# expansion_board_V0.net
KiCad netlist of a schematic drawn in EAGLE
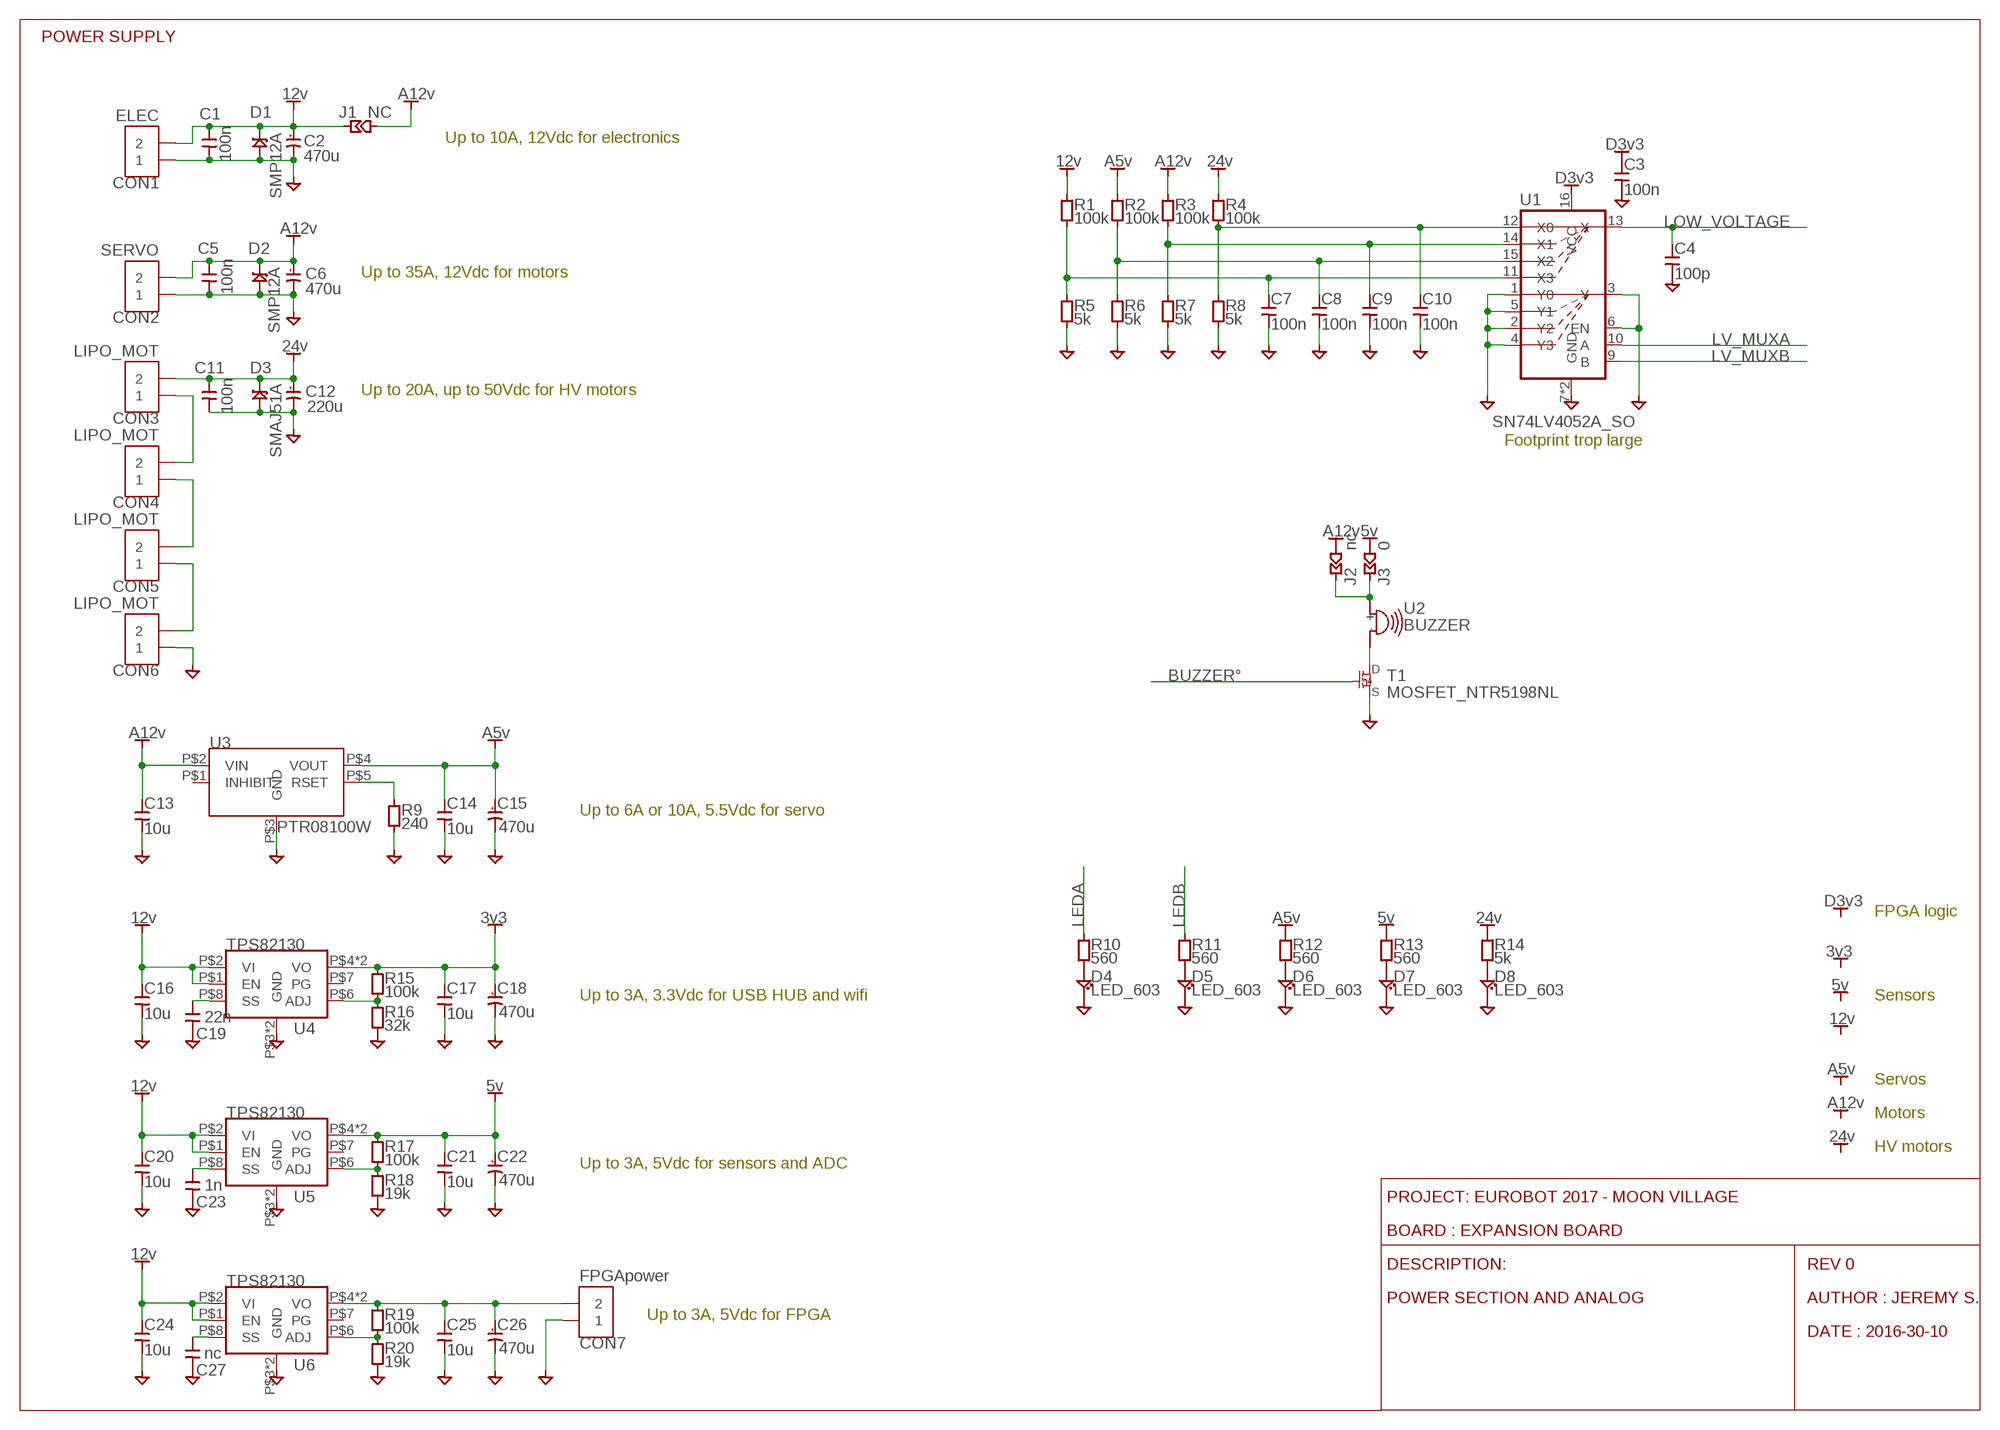
[diagram p0: schematic, sheet 1]
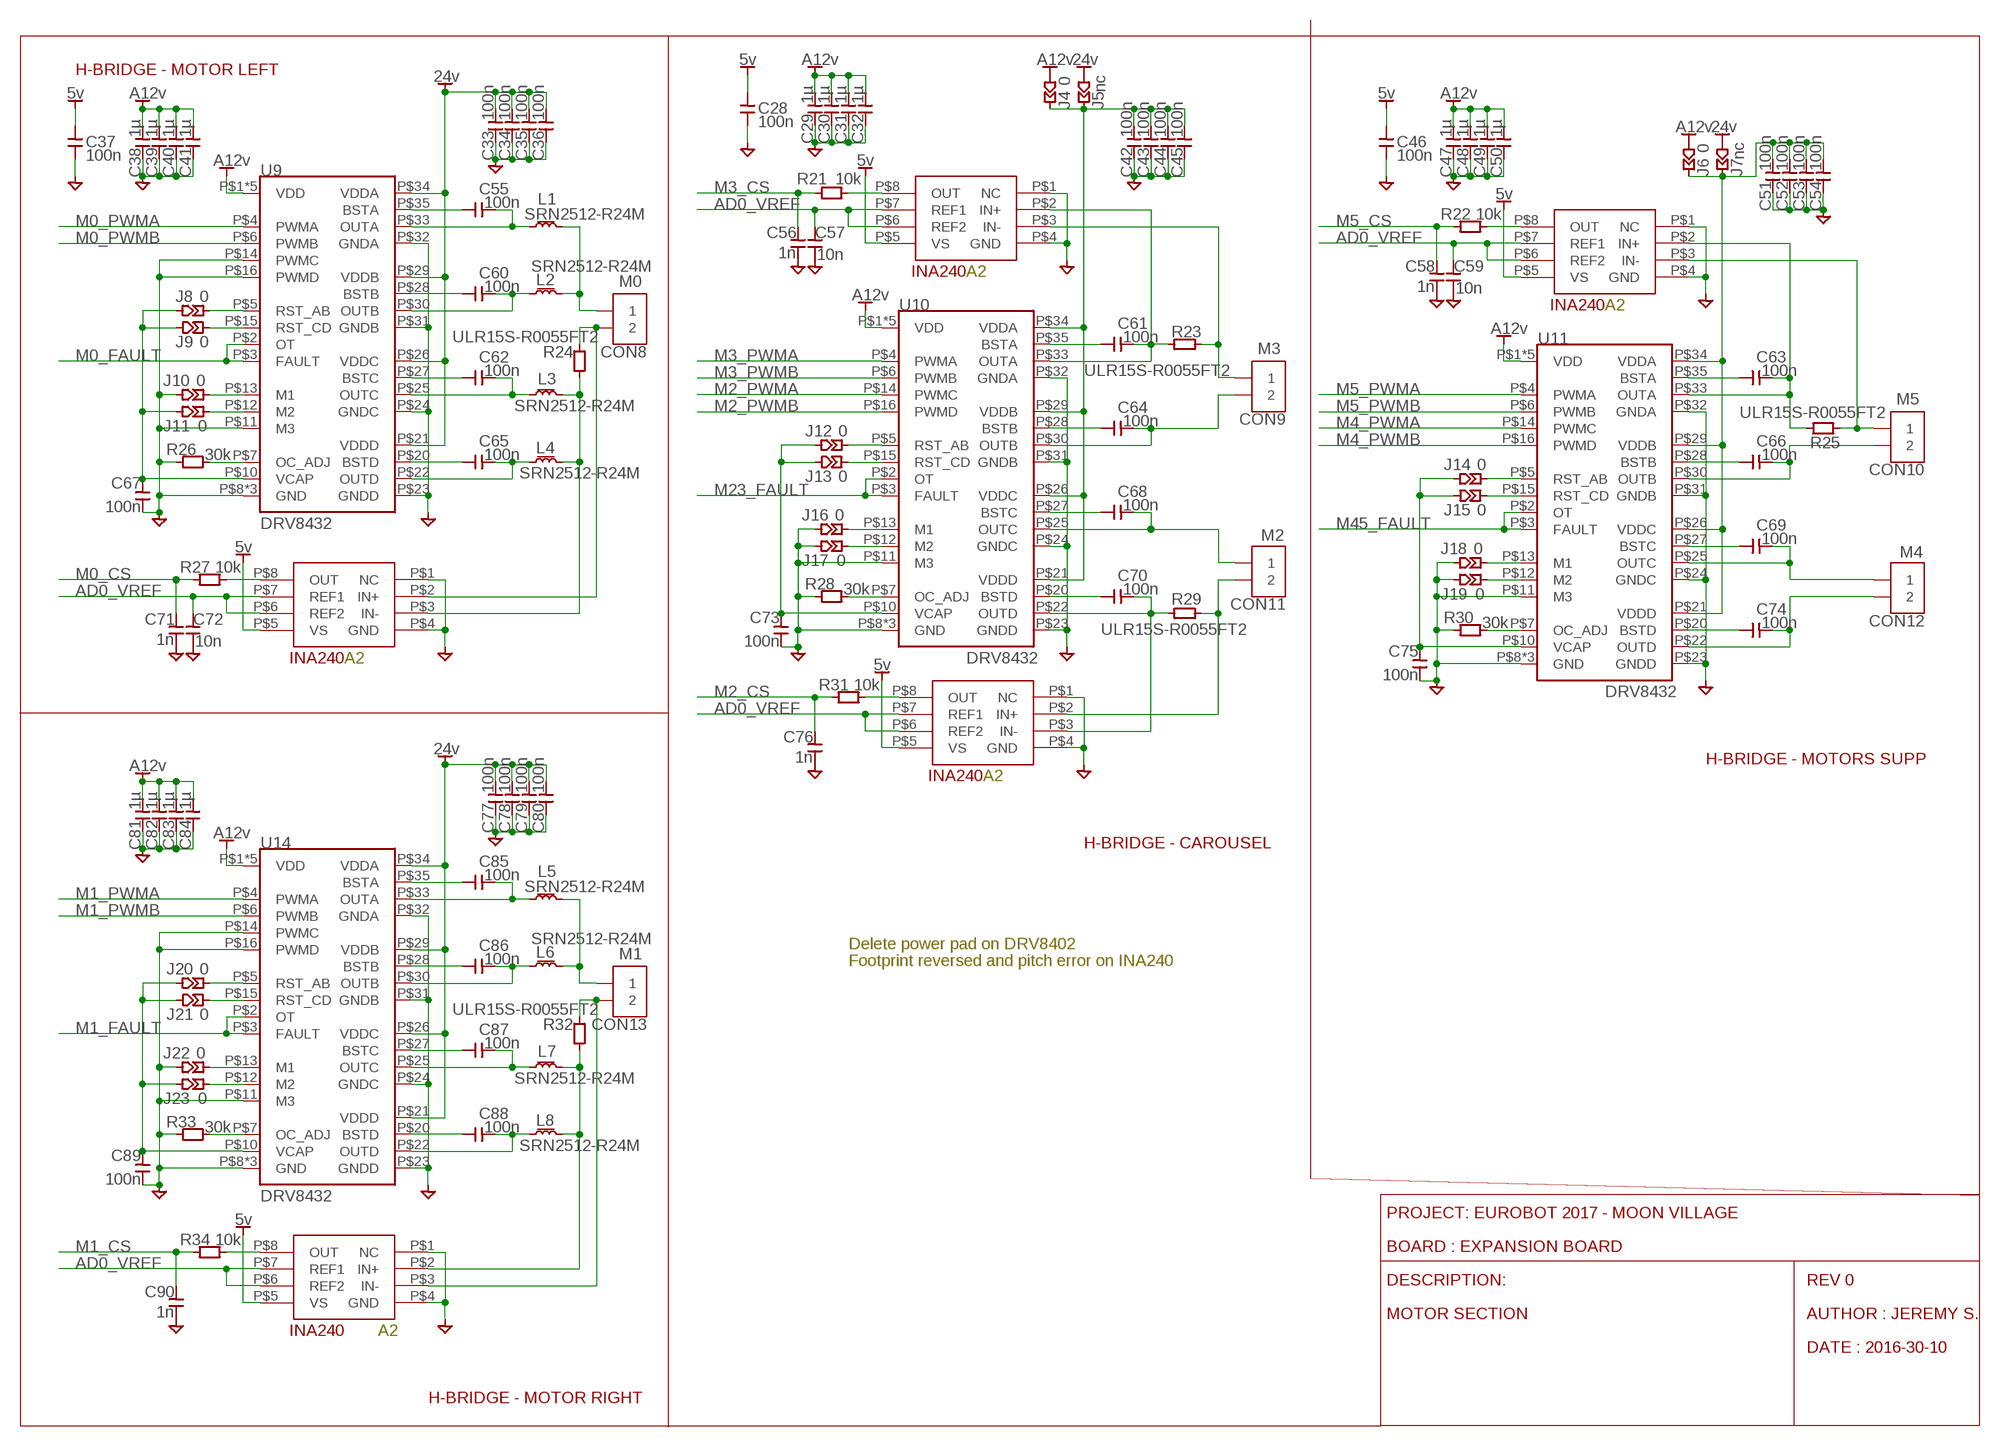
[diagram p1: schematic, sheet 2]
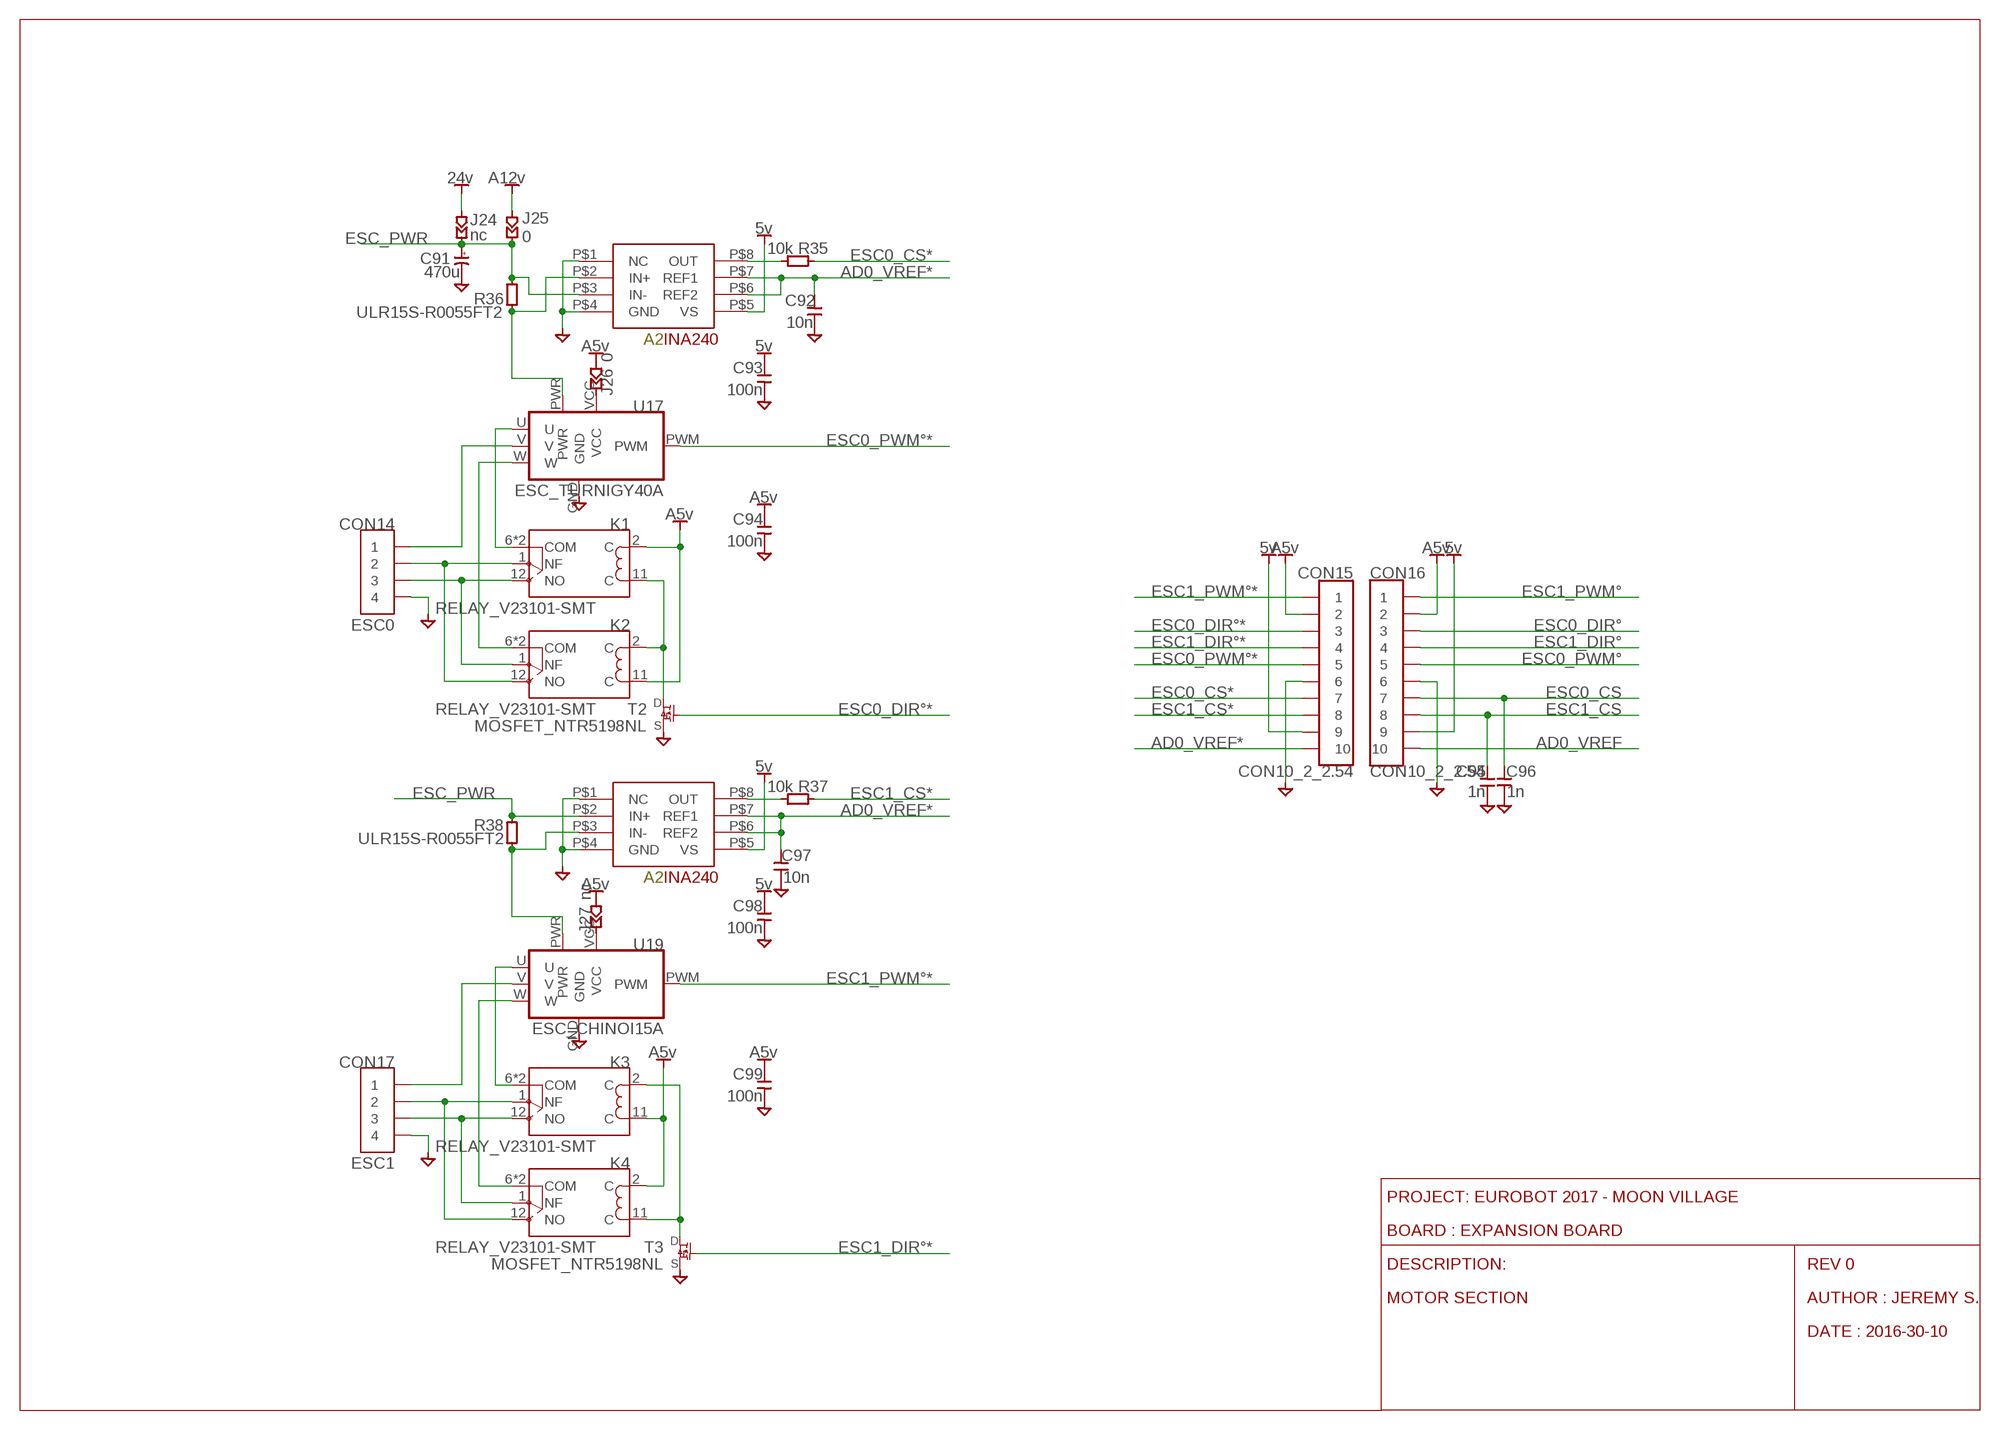
[diagram p2: schematic, sheet 3]
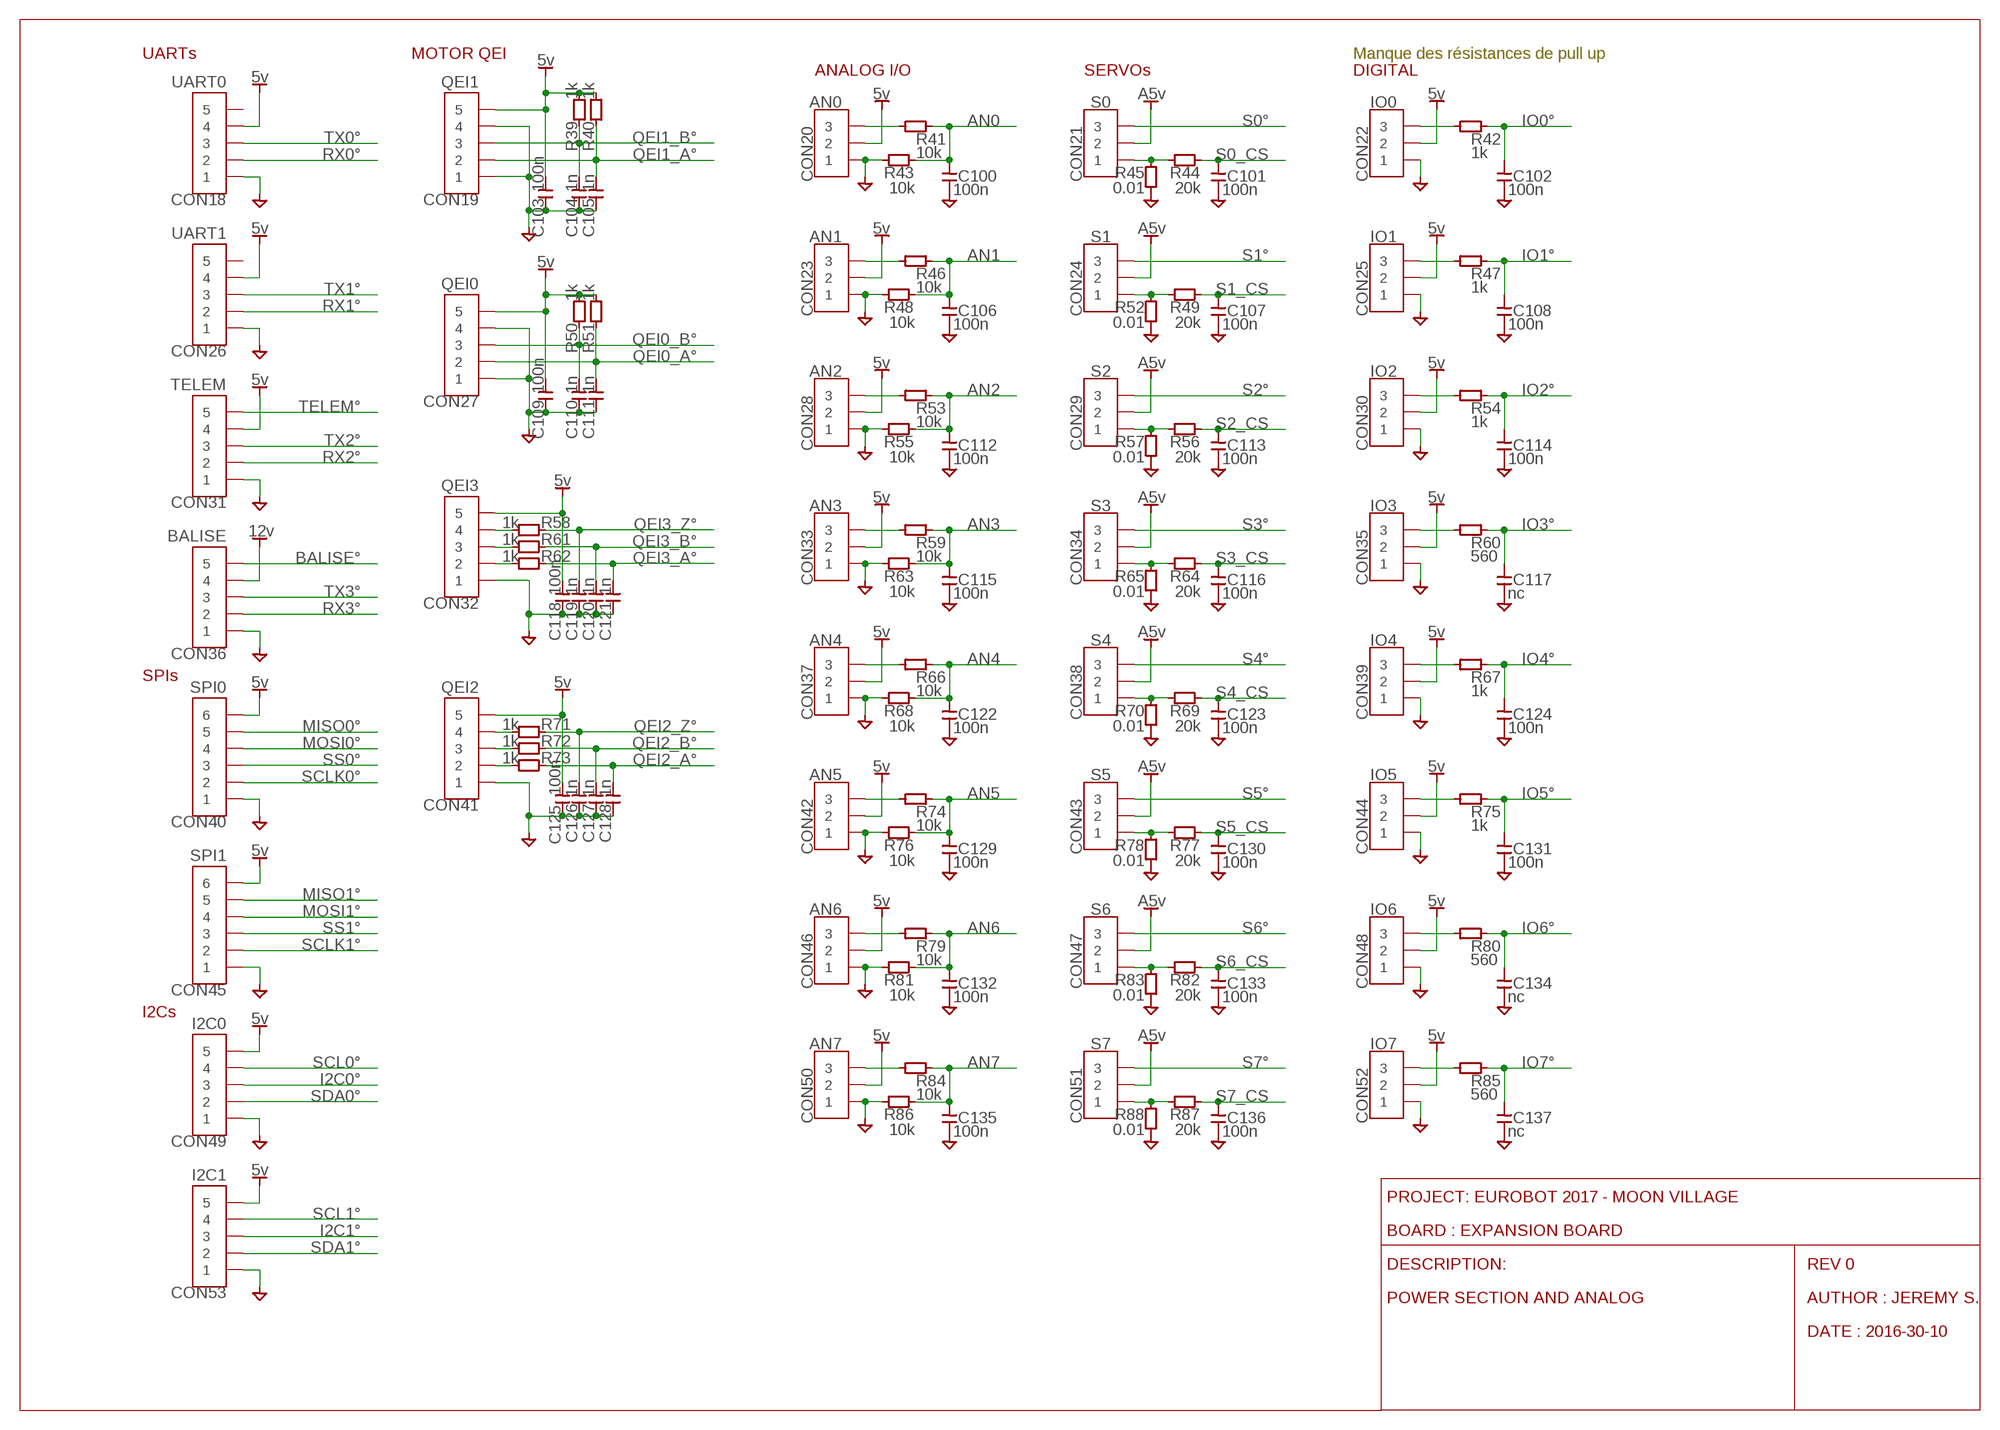
[diagram p3: schematic, sheet 4]
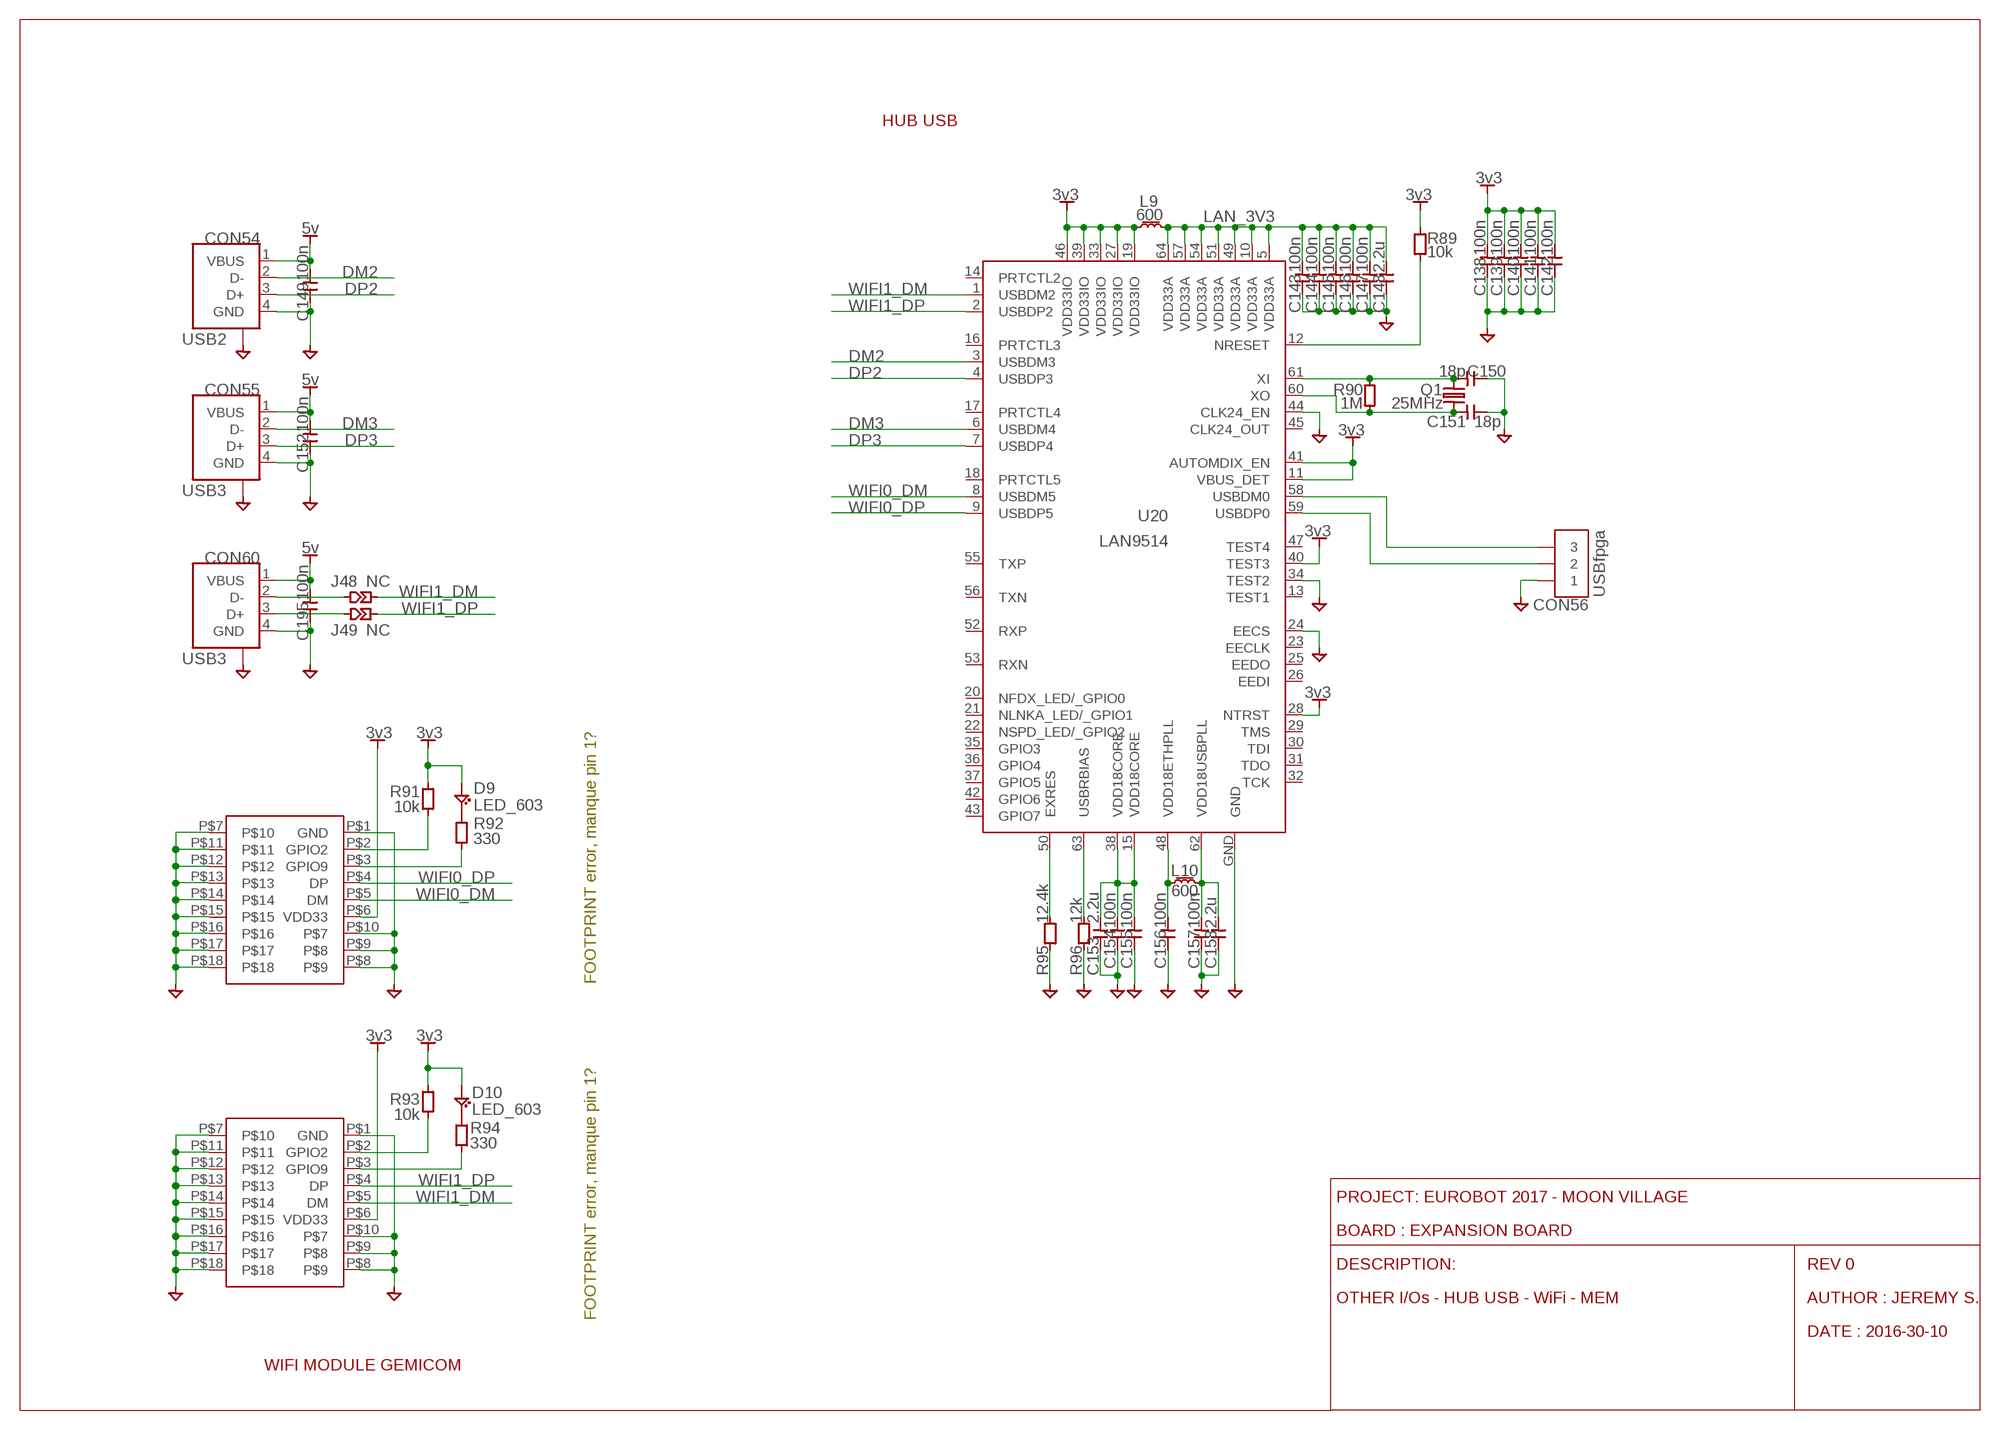
[diagram p4: schematic, sheet 5]
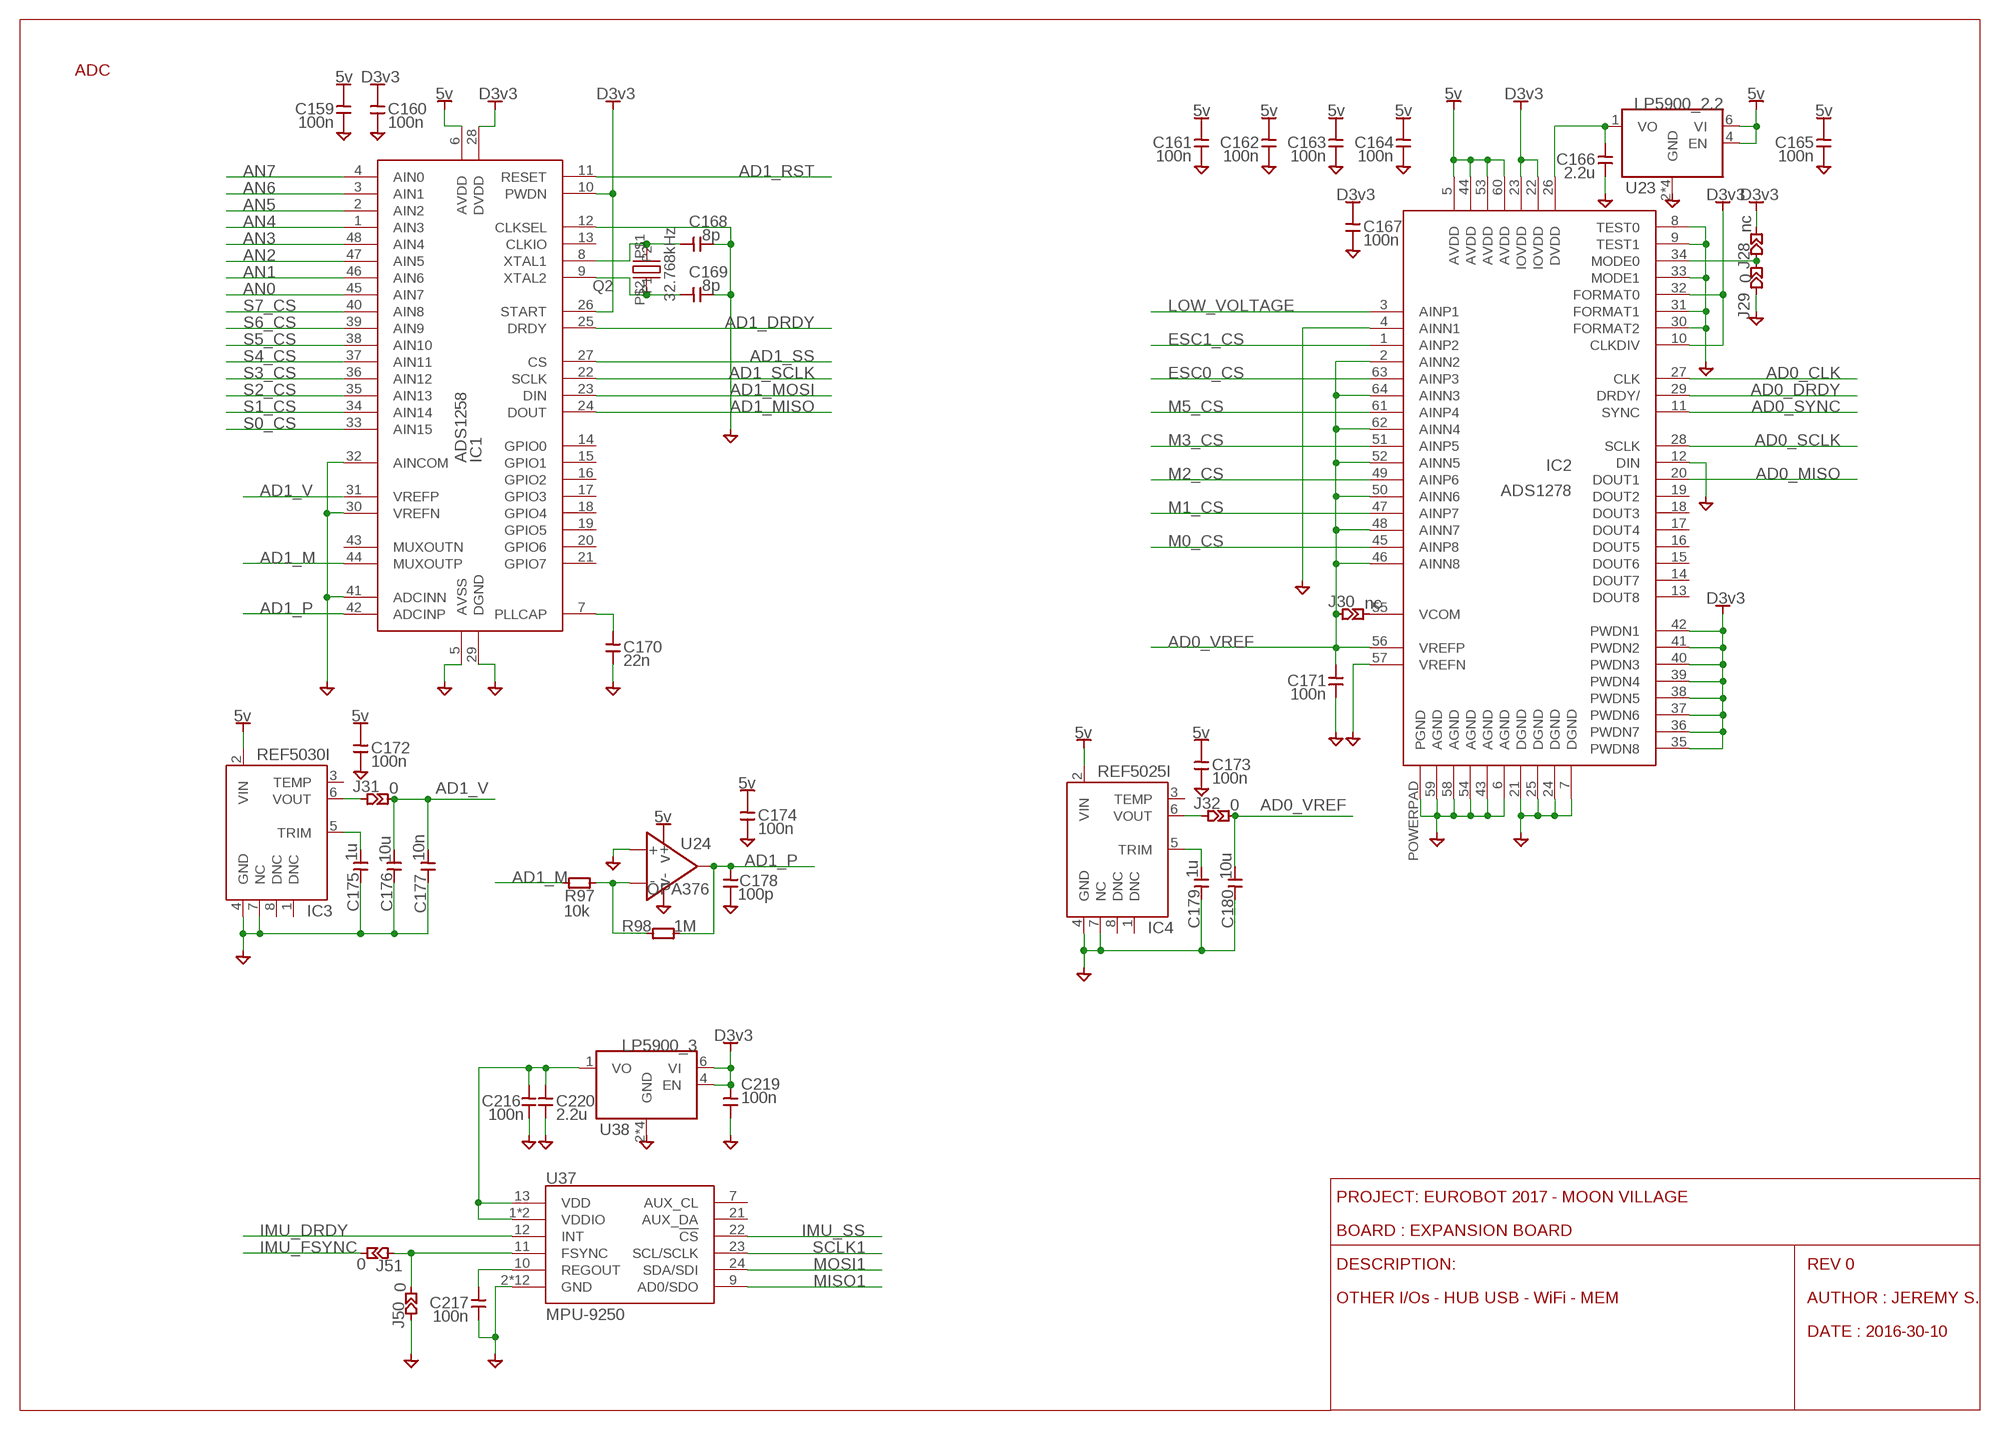
[diagram p5: schematic, sheet 6]
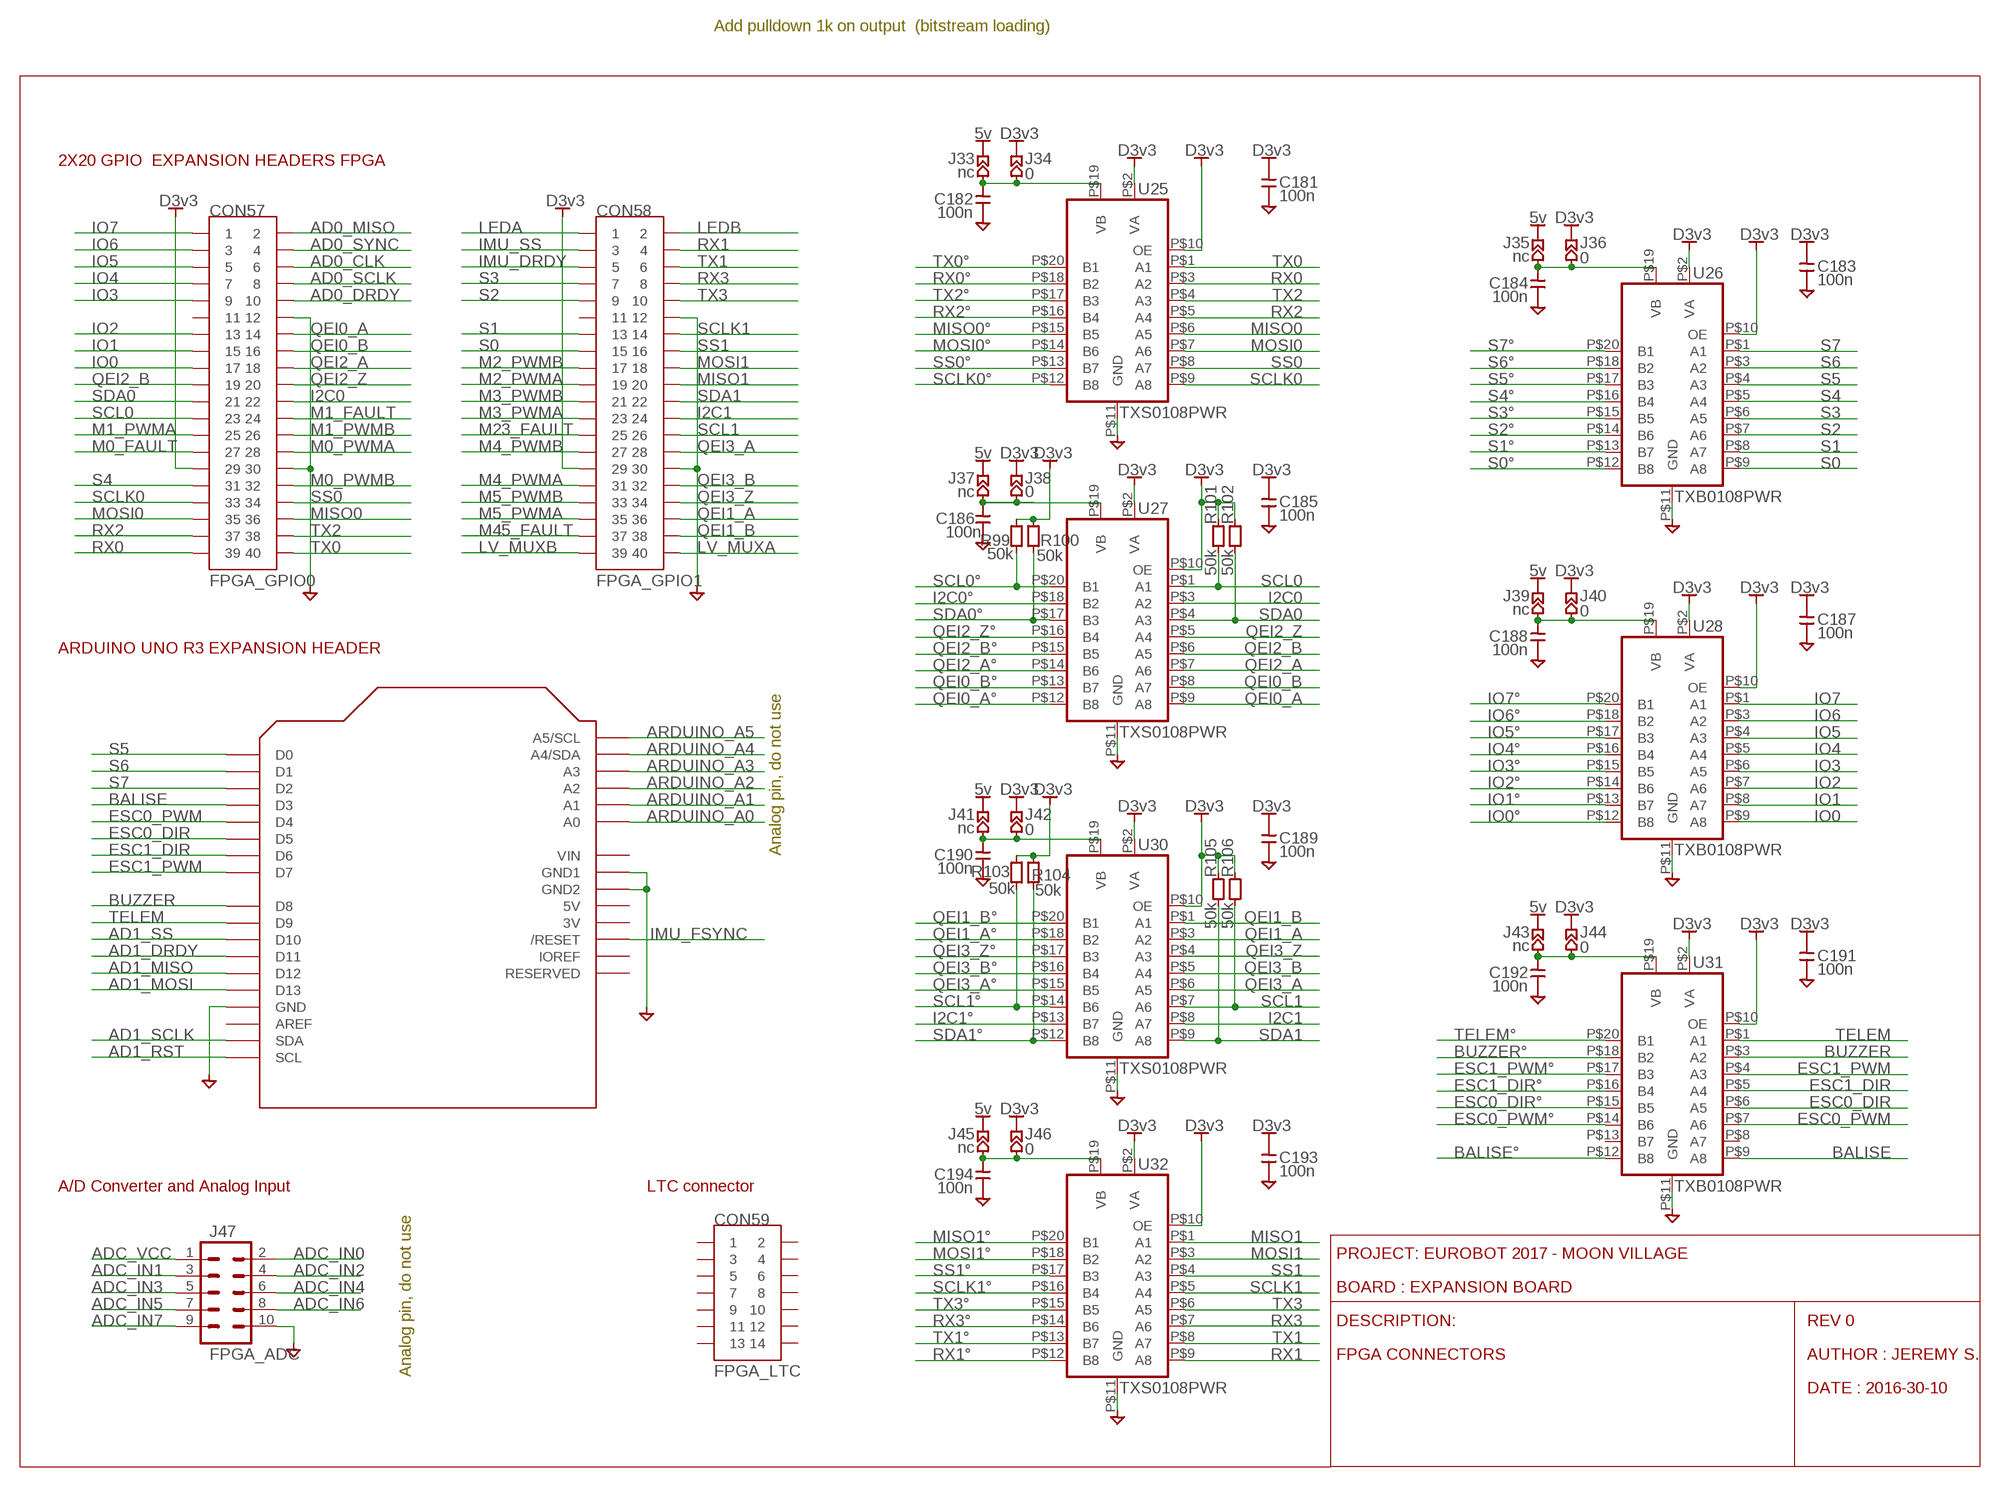
[diagram p6: schematic, sheet 7]
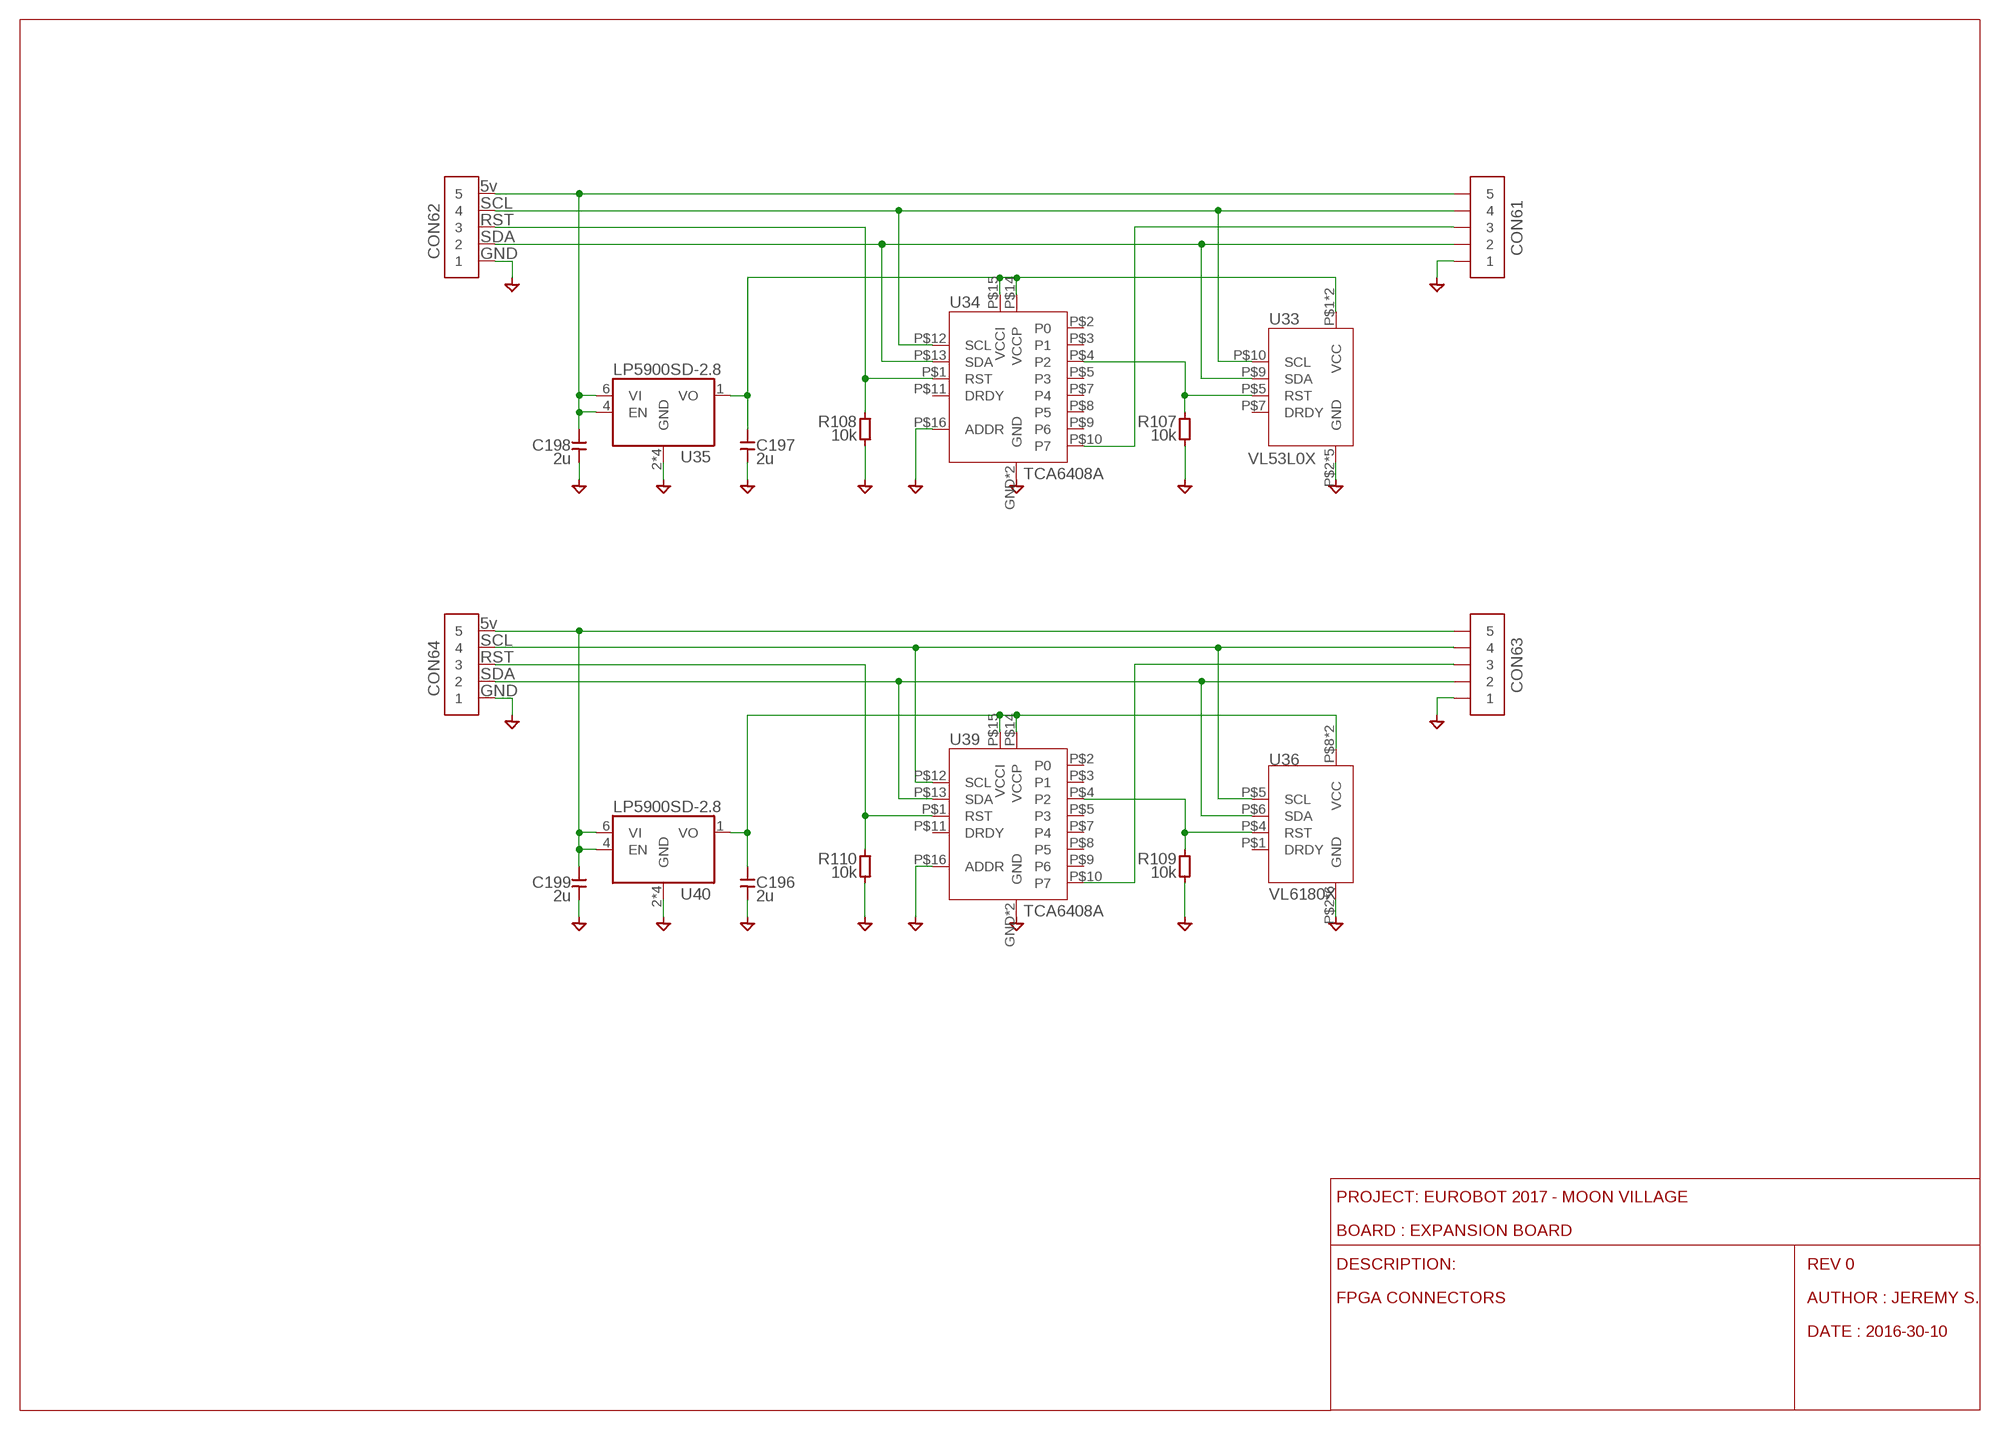
[diagram p7: schematic, sheet 8]

(export (version "E")
  (design (tool "Eeschema 10.0.6"))
  (components
    (comp (ref "C181")
      (value "100n")
      (footprint "eagle-import:CAPC1005X55N")
      (libsource (lib "eagle-import") (part "C_402"))
    )
    (comp (ref "C182")
      (value "100n")
      (footprint "eagle-import:CAPC1005X55N")
      (libsource (lib "eagle-import") (part "C_402"))
    )
    (comp (ref "C183")
      (value "100n")
      (footprint "eagle-import:CAPC1005X55N")
      (libsource (lib "eagle-import") (part "C_402"))
    )
    (comp (ref "C184")
      (value "100n")
      (footprint "eagle-import:CAPC1005X55N")
      (libsource (lib "eagle-import") (part "C_402"))
    )
    (comp (ref "C185")
      (value "100n")
      (footprint "eagle-import:CAPC1005X55N")
      (libsource (lib "eagle-import") (part "C_402"))
    )
    (comp (ref "C186")
      (value "100n")
      (footprint "eagle-import:CAPC1005X55N")
      (libsource (lib "eagle-import") (part "C_402"))
    )
    (comp (ref "C187")
      (value "100n")
      (footprint "eagle-import:CAPC1005X55N")
      (libsource (lib "eagle-import") (part "C_402"))
    )
    (comp (ref "C188")
      (value "100n")
      (footprint "eagle-import:CAPC1005X55N")
      (libsource (lib "eagle-import") (part "C_402"))
    )
    (comp (ref "C189")
      (value "100n")
      (footprint "eagle-import:CAPC1005X55N")
      (libsource (lib "eagle-import") (part "C_402"))
    )
    (comp (ref "C190")
      (value "100n")
      (footprint "eagle-import:CAPC1005X55N")
      (libsource (lib "eagle-import") (part "C_402"))
    )
    (comp (ref "C191")
      (value "100n")
      (footprint "eagle-import:CAPC1005X55N")
      (libsource (lib "eagle-import") (part "C_402"))
    )
    (comp (ref "C192")
      (value "100n")
      (footprint "eagle-import:CAPC1005X55N")
      (libsource (lib "eagle-import") (part "C_402"))
    )
    (comp (ref "C193")
      (value "100n")
      (footprint "eagle-import:CAPC1005X55N")
      (libsource (lib "eagle-import") (part "C_402"))
    )
    (comp (ref "C194")
      (value "100n")
      (footprint "eagle-import:CAPC1005X55N")
      (libsource (lib "eagle-import") (part "C_402"))
    )
    (comp (ref "CON57")
      (value "FPGA_GPIO0")
      (footprint "eagle-import:CON254P5080X600-40N")
      (libsource (lib "eagle-import") (part "CON40_2.54"))
    )
    (comp (ref "CON58")
      (value "FPGA_GPIO1")
      (footprint "eagle-import:CON254P5080X600-40N")
      (libsource (lib "eagle-import") (part "CON40_2.54"))
    )
    (comp (ref "CON59")
      (value "FPGA_LTC")
      (footprint "eagle-import:CON200P1700X400-2X7N")
      (libsource (lib "eagle-import") (part "CON14"))
    )
    (comp (ref "J33")
      (value "nc")
      (footprint "eagle-import:JUMC1005X50N")
      (libsource (lib "eagle-import") (part "JUMP_402"))
    )
    (comp (ref "J34")
      (value "0")
      (footprint "eagle-import:JUMC1005X50N")
      (libsource (lib "eagle-import") (part "JUMP_402"))
    )
    (comp (ref "J35")
      (value "nc")
      (footprint "eagle-import:JUMC1005X50N")
      (libsource (lib "eagle-import") (part "JUMP_402"))
    )
    (comp (ref "J36")
      (value "0")
      (footprint "eagle-import:JUMC1005X50N")
      (libsource (lib "eagle-import") (part "JUMP_402"))
    )
    (comp (ref "J37")
      (value "nc")
      (footprint "eagle-import:JUMC1005X50N")
      (libsource (lib "eagle-import") (part "JUMP_402"))
    )
    (comp (ref "J38")
      (value "0")
      (footprint "eagle-import:JUMC1005X50N")
      (libsource (lib "eagle-import") (part "JUMP_402"))
    )
    (comp (ref "J39")
      (value "nc")
      (footprint "eagle-import:JUMC1005X50N")
      (libsource (lib "eagle-import") (part "JUMP_402"))
    )
    (comp (ref "J40")
      (value "0")
      (footprint "eagle-import:JUMC1005X50N")
      (libsource (lib "eagle-import") (part "JUMP_402"))
    )
    (comp (ref "J41")
      (value "nc")
      (footprint "eagle-import:JUMC1005X50N")
      (libsource (lib "eagle-import") (part "JUMP_402"))
    )
    (comp (ref "J42")
      (value "0")
      (footprint "eagle-import:JUMC1005X50N")
      (libsource (lib "eagle-import") (part "JUMP_402"))
    )
    (comp (ref "J43")
      (value "nc")
      (footprint "eagle-import:JUMC1005X50N")
      (libsource (lib "eagle-import") (part "JUMP_402"))
    )
    (comp (ref "J44")
      (value "0")
      (footprint "eagle-import:JUMC1005X50N")
      (libsource (lib "eagle-import") (part "JUMP_402"))
    )
    (comp (ref "J45")
      (value "nc")
      (footprint "eagle-import:JUMC1005X50N")
      (libsource (lib "eagle-import") (part "JUMP_402"))
    )
    (comp (ref "J46")
      (value "0")
      (footprint "eagle-import:JUMC1005X50N")
      (libsource (lib "eagle-import") (part "JUMP_402"))
    )
    (comp (ref "J47")
      (value "FPGA_ADC")
      (footprint "eagle-import:2X5_NOSILK")
      (libsource (lib "eagle-import") (part "M05X2NO_SILK"))
    )
    (comp (ref "R99")
      (value "50k")
      (footprint "eagle-import:RESC1005X40N")
      (libsource (lib "eagle-import") (part "R_402"))
    )
    (comp (ref "R100")
      (value "50k")
      (footprint "eagle-import:RESC1005X40N")
      (libsource (lib "eagle-import") (part "R_402"))
    )
    (comp (ref "R101")
      (value "50k")
      (footprint "eagle-import:RESC1005X40N")
      (libsource (lib "eagle-import") (part "R_402"))
    )
    (comp (ref "R102")
      (value "50k")
      (footprint "eagle-import:RESC1005X40N")
      (libsource (lib "eagle-import") (part "R_402"))
    )
    (comp (ref "R103")
      (value "50k")
      (footprint "eagle-import:RESC1005X40N")
      (libsource (lib "eagle-import") (part "R_402"))
    )
    (comp (ref "R104")
      (value "50k")
      (footprint "eagle-import:RESC1005X40N")
      (libsource (lib "eagle-import") (part "R_402"))
    )
    (comp (ref "R105")
      (value "50k")
      (footprint "eagle-import:RESC1005X40N")
      (libsource (lib "eagle-import") (part "R_402"))
    )
    (comp (ref "R106")
      (value "50k")
      (footprint "eagle-import:RESC1005X40N")
      (libsource (lib "eagle-import") (part "R_402"))
    )
    (comp (ref "U25")
      (value "TXS0108PWR")
      (footprint "eagle-import:SOP65P640X110-20N")
      (libsource (lib "eagle-import") (part "TX_0108_TSSOP"))
    )
    (comp (ref "U26")
      (value "TXB0108PWR")
      (footprint "eagle-import:SOP65P640X110-20N")
      (libsource (lib "eagle-import") (part "TX_0108_TSSOP"))
    )
    (comp (ref "U27")
      (value "TXS0108PWR")
      (footprint "eagle-import:SOP65P640X110-20N")
      (libsource (lib "eagle-import") (part "TX_0108_TSSOP"))
    )
    (comp (ref "U28")
      (value "TXB0108PWR")
      (footprint "eagle-import:SOP65P640X110-20N")
      (libsource (lib "eagle-import") (part "TX_0108_TSSOP"))
    )
    (comp (ref "U29")
      (value "FPGA_ARDUINO")
      (footprint "eagle-import:ARDUINOR3")
      (libsource (lib "eagle-import") (part "ARDUINOR3-DIMENSION"))
    )
    (comp (ref "U30")
      (value "TXS0108PWR")
      (footprint "eagle-import:SOP65P640X110-20N")
      (libsource (lib "eagle-import") (part "TX_0108_TSSOP"))
    )
    (comp (ref "U31")
      (value "TXB0108PWR")
      (footprint "eagle-import:SOP65P640X110-20N")
      (libsource (lib "eagle-import") (part "TX_0108_TSSOP"))
    )
    (comp (ref "U32")
      (value "TXS0108PWR")
      (footprint "eagle-import:SOP65P640X110-20N")
      (libsource (lib "eagle-import") (part "TX_0108_TSSOP"))
    )
    (comp (ref "C196")
      (value "2u")
      (footprint "eagle-import:CAPC1608X95N")
      (libsource (lib "eagle-import") (part "C_603"))
    )
    (comp (ref "C197")
      (value "2u")
      (footprint "eagle-import:CAPC1608X95N")
      (libsource (lib "eagle-import") (part "C_603"))
    )
    (comp (ref "C198")
      (value "2u")
      (footprint "eagle-import:CAPC1608X95N")
      (libsource (lib "eagle-import") (part "C_603"))
    )
    (comp (ref "C199")
      (value "2u")
      (footprint "eagle-import:CAPC1608X95N")
      (libsource (lib "eagle-import") (part "C_603"))
    )
    (comp (ref "CON61")
      (value "CON5_2.54S")
      (footprint "eagle-import:CON254P1270X400-5S")
      (libsource (lib "eagle-import") (part "CON5_2.54S"))
    )
    (comp (ref "CON62")
      (value "CON5_2.54S")
      (footprint "eagle-import:CON254P1270X400-5S")
      (libsource (lib "eagle-import") (part "CON5_2.54S"))
    )
    (comp (ref "CON63")
      (value "CON5_2.54S")
      (footprint "eagle-import:CON254P1270X400-5S")
      (libsource (lib "eagle-import") (part "CON5_2.54S"))
    )
    (comp (ref "CON64")
      (value "CON5_2.54S")
      (footprint "eagle-import:CON254P1270X400-5S")
      (libsource (lib "eagle-import") (part "CON5_2.54S"))
    )
    (comp (ref "R107")
      (value "10k")
      (footprint "eagle-import:RESC1005X40N")
      (libsource (lib "eagle-import") (part "R_402"))
    )
    (comp (ref "R108")
      (value "10k")
      (footprint "eagle-import:RESC1005X40N")
      (libsource (lib "eagle-import") (part "R_402"))
    )
    (comp (ref "R109")
      (value "10k")
      (footprint "eagle-import:RESC1005X40N")
      (libsource (lib "eagle-import") (part "R_402"))
    )
    (comp (ref "R110")
      (value "10k")
      (footprint "eagle-import:RESC1005X40N")
      (libsource (lib "eagle-import") (part "R_402"))
    )
    (comp (ref "U33")
      (value "VL53L0X")
      (footprint "eagle-import:VL53L0X")
      (libsource (lib "eagle-import") (part "VL53L0X"))
    )
    (comp (ref "U34")
      (value "TCA6408A")
      (footprint "eagle-import:QFN50P300X300X80-17N")
      (libsource (lib "eagle-import") (part "I2C_EXPTCA6408A"))
    )
    (comp (ref "U35")
      (value "LP5900SD-2.8")
      (footprint "eagle-import:SON65P250X220X80-7N")
      (libsource (lib "eagle-import") (part "REG_EN_LP5900"))
    )
    (comp (ref "U36")
      (value "VL6180X")
      (footprint "eagle-import:VL6180X")
      (libsource (lib "eagle-import") (part "VL6180X"))
    )
    (comp (ref "U39")
      (value "TCA6408A")
      (footprint "eagle-import:QFN50P300X300X80-17N")
      (libsource (lib "eagle-import") (part "I2C_EXPTCA6408A"))
    )
    (comp (ref "U40")
      (value "LP5900SD-2.8")
      (footprint "eagle-import:SON65P250X220X80-7N")
      (libsource (lib "eagle-import") (part "REG_EN_LP5900"))
    )
    (comp (ref "C138")
      (value "100n")
      (footprint "eagle-import:CAPC1005X55N")
      (libsource (lib "eagle-import") (part "C_402"))
    )
    (comp (ref "C139")
      (value "100n")
      (footprint "eagle-import:CAPC1005X55N")
      (libsource (lib "eagle-import") (part "C_402"))
    )
    (comp (ref "C140")
      (value "100n")
      (footprint "eagle-import:CAPC1005X55N")
      (libsource (lib "eagle-import") (part "C_402"))
    )
    (comp (ref "C141")
      (value "100n")
      (footprint "eagle-import:CAPC1005X55N")
      (libsource (lib "eagle-import") (part "C_402"))
    )
    (comp (ref "C142")
      (value "100n")
      (footprint "eagle-import:CAPC1005X55N")
      (libsource (lib "eagle-import") (part "C_402"))
    )
    (comp (ref "C143")
      (value "100n")
      (footprint "eagle-import:CAPC1005X55N")
      (libsource (lib "eagle-import") (part "C_402"))
    )
    (comp (ref "C144")
      (value "100n")
      (footprint "eagle-import:CAPC1005X55N")
      (libsource (lib "eagle-import") (part "C_402"))
    )
    (comp (ref "C145")
      (value "100n")
      (footprint "eagle-import:CAPC1005X55N")
      (libsource (lib "eagle-import") (part "C_402"))
    )
    (comp (ref "C146")
      (value "100n")
      (footprint "eagle-import:CAPC1005X55N")
      (libsource (lib "eagle-import") (part "C_402"))
    )
    (comp (ref "C147")
      (value "100n")
      (footprint "eagle-import:CAPC1005X55N")
      (libsource (lib "eagle-import") (part "C_402"))
    )
    (comp (ref "C148")
      (value "2.2u")
      (footprint "eagle-import:CAPC1608X95N")
      (libsource (lib "eagle-import") (part "C_603"))
    )
    (comp (ref "C149")
      (value "100n")
      (footprint "eagle-import:CAPC1005X55N")
      (libsource (lib "eagle-import") (part "C_402"))
    )
    (comp (ref "C150")
      (value "18p")
      (footprint "eagle-import:CAPC1005X55N")
      (libsource (lib "eagle-import") (part "C_402"))
    )
    (comp (ref "C151")
      (value "18p")
      (footprint "eagle-import:CAPC1005X55N")
      (libsource (lib "eagle-import") (part "C_402"))
    )
    (comp (ref "C152")
      (value "100n")
      (footprint "eagle-import:CAPC1005X55N")
      (libsource (lib "eagle-import") (part "C_402"))
    )
    (comp (ref "C153")
      (value "2.2u")
      (footprint "eagle-import:CAPC1608X95N")
      (libsource (lib "eagle-import") (part "C_603"))
    )
    (comp (ref "C154")
      (value "100n")
      (footprint "eagle-import:CAPC1005X55N")
      (libsource (lib "eagle-import") (part "C_402"))
    )
    (comp (ref "C155")
      (value "100n")
      (footprint "eagle-import:CAPC1005X55N")
      (libsource (lib "eagle-import") (part "C_402"))
    )
    (comp (ref "C156")
      (value "100n")
      (footprint "eagle-import:CAPC1005X55N")
      (libsource (lib "eagle-import") (part "C_402"))
    )
    (comp (ref "C157")
      (value "100n")
      (footprint "eagle-import:CAPC1005X55N")
      (libsource (lib "eagle-import") (part "C_402"))
    )
    (comp (ref "C158")
      (value "2.2u")
      (footprint "eagle-import:CAPC1608X95N")
      (libsource (lib "eagle-import") (part "C_603"))
    )
    (comp (ref "C195")
      (value "100n")
      (footprint "eagle-import:CAPC1005X55N")
      (libsource (lib "eagle-import") (part "C_402"))
    )
    (comp (ref "CON54")
      (value "USB2")
      (footprint "eagle-import:USB_A")
      (libsource (lib "eagle-import") (part "USB_A"))
    )
    (comp (ref "CON55")
      (value "USB3")
      (footprint "eagle-import:USB_A")
      (libsource (lib "eagle-import") (part "USB_A"))
    )
    (comp (ref "CON56")
      (value "USBfpga")
      (footprint "eagle-import:CON254P762X400-3N-S")
      (libsource (lib "eagle-import") (part "CON3_2.54S"))
    )
    (comp (ref "CON60")
      (value "USB3")
      (footprint "eagle-import:USB_A")
      (libsource (lib "eagle-import") (part "USB_A"))
    )
    (comp (ref "D9")
      (value "LED_603")
      (footprint "eagle-import:LEDC1608X60N")
      (libsource (lib "eagle-import") (part "LED_603"))
    )
    (comp (ref "D10")
      (value "LED_603")
      (footprint "eagle-import:LEDC1608X60N")
      (libsource (lib "eagle-import") (part "LED_603"))
    )
    (comp (ref "J48")
      (value "NC")
      (footprint "eagle-import:JUMC1005X50N")
      (libsource (lib "eagle-import") (part "JUMP_402"))
    )
    (comp (ref "J49")
      (value "NC")
      (footprint "eagle-import:JUMC1005X50N")
      (libsource (lib "eagle-import") (part "JUMP_402"))
    )
    (comp (ref "L9")
      (value "600")
      (footprint "eagle-import:INDC1608X95N")
      (libsource (lib "eagle-import") (part "INDUCTANCE_603"))
    )
    (comp (ref "L10")
      (value "600")
      (footprint "eagle-import:INDC1608X95N")
      (libsource (lib "eagle-import") (part "INDUCTANCE_603"))
    )
    (comp (ref "Q1")
      (value "25MHz")
      (footprint "eagle-import:XTAL500X320X130N")
      (libsource (lib "eagle-import") (part "QUARTZ2"))
    )
    (comp (ref "R89")
      (value "10k")
      (footprint "eagle-import:RESC1005X40N")
      (libsource (lib "eagle-import") (part "R_402"))
    )
    (comp (ref "R90")
      (value "1M")
      (footprint "eagle-import:RESC1005X40N")
      (libsource (lib "eagle-import") (part "R_402"))
    )
    (comp (ref "R91")
      (value "10k")
      (footprint "eagle-import:RESC1005X40N")
      (libsource (lib "eagle-import") (part "R_402"))
    )
    (comp (ref "R92")
      (value "330")
      (footprint "eagle-import:RESC1005X40N")
      (libsource (lib "eagle-import") (part "R_402"))
    )
    (comp (ref "R93")
      (value "10k")
      (footprint "eagle-import:RESC1005X40N")
      (libsource (lib "eagle-import") (part "R_402"))
    )
    (comp (ref "R94")
      (value "330")
      (footprint "eagle-import:RESC1005X40N")
      (libsource (lib "eagle-import") (part "R_402"))
    )
    (comp (ref "R95")
      (value "12.4k")
      (footprint "eagle-import:RESC1005X40N")
      (libsource (lib "eagle-import") (part "R_402"))
    )
    (comp (ref "R96")
      (value "12k")
      (footprint "eagle-import:RESC1005X40N")
      (libsource (lib "eagle-import") (part "R_402"))
    )
    (comp (ref "U20")
      (value "LAN9514")
      (footprint "eagle-import:QFN50P900X900X100-65N")
      (libsource (lib "eagle-import") (part "LAN9514"))
    )
    (comp (ref "U21")
      (value "LGA22U")
      (footprint "eagle-import:LGA22U")
      (libsource (lib "eagle-import") (part "LGA22U"))
    )
    (comp (ref "U22")
      (value "LGA22U")
      (footprint "eagle-import:LGA22U")
      (libsource (lib "eagle-import") (part "LGA22U"))
    )
    (comp (ref "C100")
      (value "100n")
      (footprint "eagle-import:CAPC1005X55N")
      (libsource (lib "eagle-import") (part "C_402"))
    )
    (comp (ref "C101")
      (value "100n")
      (footprint "eagle-import:CAPC1005X55N")
      (libsource (lib "eagle-import") (part "C_402"))
    )
    (comp (ref "C102")
      (value "100n")
      (footprint "eagle-import:CAPC1005X55N")
      (libsource (lib "eagle-import") (part "C_402"))
    )
    (comp (ref "C103")
      (value "100n")
      (footprint "eagle-import:CAPC1005X55N")
      (libsource (lib "eagle-import") (part "C_402"))
    )
    (comp (ref "C104")
      (value "1n")
      (footprint "eagle-import:CAPC1005X55N")
      (libsource (lib "eagle-import") (part "C_402"))
    )
    (comp (ref "C105")
      (value "1n")
      (footprint "eagle-import:CAPC1005X55N")
      (libsource (lib "eagle-import") (part "C_402"))
    )
    (comp (ref "C106")
      (value "100n")
      (footprint "eagle-import:CAPC1005X55N")
      (libsource (lib "eagle-import") (part "C_402"))
    )
    (comp (ref "C107")
      (value "100n")
      (footprint "eagle-import:CAPC1005X55N")
      (libsource (lib "eagle-import") (part "C_402"))
    )
    (comp (ref "C108")
      (value "100n")
      (footprint "eagle-import:CAPC1005X55N")
      (libsource (lib "eagle-import") (part "C_402"))
    )
    (comp (ref "C109")
      (value "100n")
      (footprint "eagle-import:CAPC1005X55N")
      (libsource (lib "eagle-import") (part "C_402"))
    )
    (comp (ref "C110")
      (value "1n")
      (footprint "eagle-import:CAPC1005X55N")
      (libsource (lib "eagle-import") (part "C_402"))
    )
    (comp (ref "C111")
      (value "1n")
      (footprint "eagle-import:CAPC1005X55N")
      (libsource (lib "eagle-import") (part "C_402"))
    )
    (comp (ref "C112")
      (value "100n")
      (footprint "eagle-import:CAPC1005X55N")
      (libsource (lib "eagle-import") (part "C_402"))
    )
    (comp (ref "C113")
      (value "100n")
      (footprint "eagle-import:CAPC1005X55N")
      (libsource (lib "eagle-import") (part "C_402"))
    )
    (comp (ref "C114")
      (value "100n")
      (footprint "eagle-import:CAPC1005X55N")
      (libsource (lib "eagle-import") (part "C_402"))
    )
    (comp (ref "C115")
      (value "100n")
      (footprint "eagle-import:CAPC1005X55N")
      (libsource (lib "eagle-import") (part "C_402"))
    )
    (comp (ref "C116")
      (value "100n")
      (footprint "eagle-import:CAPC1005X55N")
      (libsource (lib "eagle-import") (part "C_402"))
    )
    (comp (ref "C117")
      (value "nc")
      (footprint "eagle-import:CAPC1005X55N")
      (libsource (lib "eagle-import") (part "C_402"))
    )
    (comp (ref "C118")
      (value "100n")
      (footprint "eagle-import:CAPC1005X55N")
      (libsource (lib "eagle-import") (part "C_402"))
    )
    (comp (ref "C119")
      (value "1n")
      (footprint "eagle-import:CAPC1005X55N")
      (libsource (lib "eagle-import") (part "C_402"))
    )
    (comp (ref "C120")
      (value "1n")
      (footprint "eagle-import:CAPC1005X55N")
      (libsource (lib "eagle-import") (part "C_402"))
    )
    (comp (ref "C121")
      (value "1n")
      (footprint "eagle-import:CAPC1005X55N")
      (libsource (lib "eagle-import") (part "C_402"))
    )
    (comp (ref "C122")
      (value "100n")
      (footprint "eagle-import:CAPC1005X55N")
      (libsource (lib "eagle-import") (part "C_402"))
    )
    (comp (ref "C123")
      (value "100n")
      (footprint "eagle-import:CAPC1005X55N")
      (libsource (lib "eagle-import") (part "C_402"))
    )
    (comp (ref "C124")
      (value "100n")
      (footprint "eagle-import:CAPC1005X55N")
      (libsource (lib "eagle-import") (part "C_402"))
    )
    (comp (ref "C125")
      (value "100n")
      (footprint "eagle-import:CAPC1005X55N")
      (libsource (lib "eagle-import") (part "C_402"))
    )
    (comp (ref "C126")
      (value "1n")
      (footprint "eagle-import:CAPC1005X55N")
      (libsource (lib "eagle-import") (part "C_402"))
    )
    (comp (ref "C127")
      (value "1n")
      (footprint "eagle-import:CAPC1005X55N")
      (libsource (lib "eagle-import") (part "C_402"))
    )
    (comp (ref "C128")
      (value "1n")
      (footprint "eagle-import:CAPC1005X55N")
      (libsource (lib "eagle-import") (part "C_402"))
    )
    (comp (ref "C129")
      (value "100n")
      (footprint "eagle-import:CAPC1005X55N")
      (libsource (lib "eagle-import") (part "C_402"))
    )
    (comp (ref "C130")
      (value "100n")
      (footprint "eagle-import:CAPC1005X55N")
      (libsource (lib "eagle-import") (part "C_402"))
    )
    (comp (ref "C131")
      (value "100n")
      (footprint "eagle-import:CAPC1005X55N")
      (libsource (lib "eagle-import") (part "C_402"))
    )
    (comp (ref "C132")
      (value "100n")
      (footprint "eagle-import:CAPC1005X55N")
      (libsource (lib "eagle-import") (part "C_402"))
    )
    (comp (ref "C133")
      (value "100n")
      (footprint "eagle-import:CAPC1005X55N")
      (libsource (lib "eagle-import") (part "C_402"))
    )
    (comp (ref "C134")
      (value "nc")
      (footprint "eagle-import:CAPC1005X55N")
      (libsource (lib "eagle-import") (part "C_402"))
    )
    (comp (ref "C135")
      (value "100n")
      (footprint "eagle-import:CAPC1005X55N")
      (libsource (lib "eagle-import") (part "C_402"))
    )
    (comp (ref "C136")
      (value "100n")
      (footprint "eagle-import:CAPC1005X55N")
      (libsource (lib "eagle-import") (part "C_402"))
    )
    (comp (ref "C137")
      (value "nc")
      (footprint "eagle-import:CAPC1005X55N")
      (libsource (lib "eagle-import") (part "C_402"))
    )
    (comp (ref "CON18")
      (value "UART0")
      (footprint "eagle-import:CON254P1270X400-5S")
      (libsource (lib "eagle-import") (part "CON5_2.54S"))
    )
    (comp (ref "CON19")
      (value "QEI1")
      (footprint "eagle-import:CON254P1270X400-5S")
      (libsource (lib "eagle-import") (part "CON5_2.54S"))
    )
    (comp (ref "CON20")
      (value "AN0")
      (footprint "eagle-import:CON254P762X400-3SMT")
      (libsource (lib "eagle-import") (part "CON3_SMT"))
    )
    (comp (ref "CON21")
      (value "S0")
      (footprint "eagle-import:CON254P762X400-3SMT")
      (libsource (lib "eagle-import") (part "CON3_SMT"))
    )
    (comp (ref "CON22")
      (value "IO0")
      (footprint "eagle-import:CON254P762X400-3SMT")
      (libsource (lib "eagle-import") (part "CON3_SMT"))
    )
    (comp (ref "CON23")
      (value "AN1")
      (footprint "eagle-import:CON254P762X400-3SMT")
      (libsource (lib "eagle-import") (part "CON3_SMT"))
    )
    (comp (ref "CON24")
      (value "S1")
      (footprint "eagle-import:CON254P762X400-3SMT")
      (libsource (lib "eagle-import") (part "CON3_SMT"))
    )
    (comp (ref "CON25")
      (value "IO1")
      (footprint "eagle-import:CON254P762X400-3SMT")
      (libsource (lib "eagle-import") (part "CON3_SMT"))
    )
    (comp (ref "CON26")
      (value "UART1")
      (footprint "eagle-import:CON254P1270X400-5S")
      (libsource (lib "eagle-import") (part "CON5_2.54S"))
    )
    (comp (ref "CON27")
      (value "QEI0")
      (footprint "eagle-import:CON254P1270X400-5S")
      (libsource (lib "eagle-import") (part "CON5_2.54S"))
    )
    (comp (ref "CON28")
      (value "AN2")
      (footprint "eagle-import:CON254P762X400-3SMT")
      (libsource (lib "eagle-import") (part "CON3_SMT"))
    )
    (comp (ref "CON29")
      (value "S2")
      (footprint "eagle-import:CON254P762X400-3SMT")
      (libsource (lib "eagle-import") (part "CON3_SMT"))
    )
    (comp (ref "CON30")
      (value "IO2")
      (footprint "eagle-import:CON254P762X400-3SMT")
      (libsource (lib "eagle-import") (part "CON3_SMT"))
    )
    (comp (ref "CON31")
      (value "TELEM")
      (footprint "eagle-import:CON254P1270X400-5S")
      (libsource (lib "eagle-import") (part "CON5_2.54S"))
    )
    (comp (ref "CON32")
      (value "QEI3")
      (footprint "eagle-import:CON254P1270X400-5S")
      (libsource (lib "eagle-import") (part "CON5_2.54S"))
    )
    (comp (ref "CON33")
      (value "AN3")
      (footprint "eagle-import:CON254P762X400-3SMT")
      (libsource (lib "eagle-import") (part "CON3_SMT"))
    )
    (comp (ref "CON34")
      (value "S3")
      (footprint "eagle-import:CON254P762X400-3SMT")
      (libsource (lib "eagle-import") (part "CON3_SMT"))
    )
    (comp (ref "CON35")
      (value "IO3")
      (footprint "eagle-import:CON254P762X400-3SMT")
      (libsource (lib "eagle-import") (part "CON3_SMT"))
    )
    (comp (ref "CON36")
      (value "BALISE")
      (footprint "eagle-import:CON254P1270X400-5S")
      (libsource (lib "eagle-import") (part "CON5_2.54S"))
    )
    (comp (ref "CON37")
      (value "AN4")
      (footprint "eagle-import:CON254P762X400-3SMT")
      (libsource (lib "eagle-import") (part "CON3_SMT"))
    )
    (comp (ref "CON38")
      (value "S4")
      (footprint "eagle-import:CON254P762X400-3SMT")
      (libsource (lib "eagle-import") (part "CON3_SMT"))
    )
    (comp (ref "CON39")
      (value "IO4")
      (footprint "eagle-import:CON254P762X400-3SMT")
      (libsource (lib "eagle-import") (part "CON3_SMT"))
    )
    (comp (ref "CON40")
      (value "SPI0")
      (footprint "eagle-import:CON254P1524X400-6N-S")
      (libsource (lib "eagle-import") (part "CON6_2.54S"))
    )
    (comp (ref "CON41")
      (value "QEI2")
      (footprint "eagle-import:CON254P1270X400-5S")
      (libsource (lib "eagle-import") (part "CON5_2.54S"))
    )
    (comp (ref "CON42")
      (value "AN5")
      (footprint "eagle-import:CON254P762X400-3SMT")
      (libsource (lib "eagle-import") (part "CON3_SMT"))
    )
    (comp (ref "CON43")
      (value "S5")
      (footprint "eagle-import:CON254P762X400-3SMT")
      (libsource (lib "eagle-import") (part "CON3_SMT"))
    )
    (comp (ref "CON44")
      (value "IO5")
      (footprint "eagle-import:CON254P762X400-3SMT")
      (libsource (lib "eagle-import") (part "CON3_SMT"))
    )
    (comp (ref "CON45")
      (value "SPI1")
      (footprint "eagle-import:CON254P1524X400-6N-S")
      (libsource (lib "eagle-import") (part "CON6_2.54S"))
    )
    (comp (ref "CON46")
      (value "AN6")
      (footprint "eagle-import:CON254P762X400-3SMT")
      (libsource (lib "eagle-import") (part "CON3_SMT"))
    )
    (comp (ref "CON47")
      (value "S6")
      (footprint "eagle-import:CON254P762X400-3SMT")
      (libsource (lib "eagle-import") (part "CON3_SMT"))
    )
    (comp (ref "CON48")
      (value "IO6")
      (footprint "eagle-import:CON254P762X400-3SMT")
      (libsource (lib "eagle-import") (part "CON3_SMT"))
    )
    (comp (ref "CON49")
      (value "I2C0")
      (footprint "eagle-import:CON254P1270X400-5S")
      (libsource (lib "eagle-import") (part "CON5_2.54S"))
    )
    (comp (ref "CON50")
      (value "AN7")
      (footprint "eagle-import:CON254P762X400-3SMT")
      (libsource (lib "eagle-import") (part "CON3_SMT"))
    )
    (comp (ref "CON51")
      (value "S7")
      (footprint "eagle-import:CON254P762X400-3SMT")
      (libsource (lib "eagle-import") (part "CON3_SMT"))
    )
    (comp (ref "CON52")
      (value "IO7")
      (footprint "eagle-import:CON254P762X400-3SMT")
      (libsource (lib "eagle-import") (part "CON3_SMT"))
    )
    (comp (ref "CON53")
      (value "I2C1")
      (footprint "eagle-import:CON254P1270X400-5S")
      (libsource (lib "eagle-import") (part "CON5_2.54S"))
    )
    (comp (ref "R39")
      (value "1k")
      (footprint "eagle-import:RESC1005X40N")
      (libsource (lib "eagle-import") (part "R_402"))
    )
    (comp (ref "R40")
      (value "1k")
      (footprint "eagle-import:RESC1005X40N")
      (libsource (lib "eagle-import") (part "R_402"))
    )
    (comp (ref "R41")
      (value "10k")
      (footprint "eagle-import:RESC1005X40N")
      (libsource (lib "eagle-import") (part "R_402"))
    )
    (comp (ref "R42")
      (value "1k")
      (footprint "eagle-import:RESC1005X40N")
      (libsource (lib "eagle-import") (part "R_402"))
    )
    (comp (ref "R43")
      (value "10k")
      (footprint "eagle-import:RESC1005X40N")
      (libsource (lib "eagle-import") (part "R_402"))
    )
    (comp (ref "R44")
      (value "20k")
      (footprint "eagle-import:RESC1005X40N")
      (libsource (lib "eagle-import") (part "R_402"))
    )
    (comp (ref "R45")
      (value "0.01")
      (footprint "eagle-import:RESC1608X50AN")
      (libsource (lib "eagle-import") (part "R_603"))
    )
    (comp (ref "R46")
      (value "10k")
      (footprint "eagle-import:RESC1005X40N")
      (libsource (lib "eagle-import") (part "R_402"))
    )
    (comp (ref "R47")
      (value "1k")
      (footprint "eagle-import:RESC1005X40N")
      (libsource (lib "eagle-import") (part "R_402"))
    )
    (comp (ref "R48")
      (value "10k")
      (footprint "eagle-import:RESC1005X40N")
      (libsource (lib "eagle-import") (part "R_402"))
    )
    (comp (ref "R49")
      (value "20k")
      (footprint "eagle-import:RESC1005X40N")
      (libsource (lib "eagle-import") (part "R_402"))
    )
    (comp (ref "R50")
      (value "1k")
      (footprint "eagle-import:RESC1005X40N")
      (libsource (lib "eagle-import") (part "R_402"))
    )
    (comp (ref "R51")
      (value "1k")
      (footprint "eagle-import:RESC1005X40N")
      (libsource (lib "eagle-import") (part "R_402"))
    )
    (comp (ref "R52")
      (value "0.01")
      (footprint "eagle-import:RESC1608X50AN")
      (libsource (lib "eagle-import") (part "R_603"))
    )
    (comp (ref "R53")
      (value "10k")
      (footprint "eagle-import:RESC1005X40N")
      (libsource (lib "eagle-import") (part "R_402"))
    )
    (comp (ref "R54")
      (value "1k")
      (footprint "eagle-import:RESC1005X40N")
      (libsource (lib "eagle-import") (part "R_402"))
    )
    (comp (ref "R55")
      (value "10k")
      (footprint "eagle-import:RESC1005X40N")
      (libsource (lib "eagle-import") (part "R_402"))
    )
    (comp (ref "R56")
      (value "20k")
      (footprint "eagle-import:RESC1005X40N")
      (libsource (lib "eagle-import") (part "R_402"))
    )
    (comp (ref "R57")
      (value "0.01")
      (footprint "eagle-import:RESC1608X50AN")
      (libsource (lib "eagle-import") (part "R_603"))
    )
    (comp (ref "R58")
      (value "1k")
      (footprint "eagle-import:RESC1005X40N")
      (libsource (lib "eagle-import") (part "R_402"))
    )
    (comp (ref "R59")
      (value "10k")
      (footprint "eagle-import:RESC1005X40N")
      (libsource (lib "eagle-import") (part "R_402"))
    )
    (comp (ref "R60")
      (value "560")
      (footprint "eagle-import:RESC1005X40N")
      (libsource (lib "eagle-import") (part "R_402"))
    )
    (comp (ref "R61")
      (value "1k")
      (footprint "eagle-import:RESC1005X40N")
      (libsource (lib "eagle-import") (part "R_402"))
    )
    (comp (ref "R62")
      (value "1k")
      (footprint "eagle-import:RESC1005X40N")
      (libsource (lib "eagle-import") (part "R_402"))
    )
    (comp (ref "R63")
      (value "10k")
      (footprint "eagle-import:RESC1005X40N")
      (libsource (lib "eagle-import") (part "R_402"))
    )
    (comp (ref "R64")
      (value "20k")
      (footprint "eagle-import:RESC1005X40N")
      (libsource (lib "eagle-import") (part "R_402"))
    )
    (comp (ref "R65")
      (value "0.01")
      (footprint "eagle-import:RESC1608X50AN")
      (libsource (lib "eagle-import") (part "R_603"))
    )
    (comp (ref "R66")
      (value "10k")
      (footprint "eagle-import:RESC1005X40N")
      (libsource (lib "eagle-import") (part "R_402"))
    )
    (comp (ref "R67")
      (value "1k")
      (footprint "eagle-import:RESC1005X40N")
      (libsource (lib "eagle-import") (part "R_402"))
    )
    (comp (ref "R68")
      (value "10k")
      (footprint "eagle-import:RESC1005X40N")
      (libsource (lib "eagle-import") (part "R_402"))
    )
    (comp (ref "R69")
      (value "20k")
      (footprint "eagle-import:RESC1005X40N")
      (libsource (lib "eagle-import") (part "R_402"))
    )
    (comp (ref "R70")
      (value "0.01")
      (footprint "eagle-import:RESC1608X50AN")
      (libsource (lib "eagle-import") (part "R_603"))
    )
    (comp (ref "R71")
      (value "1k")
      (footprint "eagle-import:RESC1005X40N")
      (libsource (lib "eagle-import") (part "R_402"))
    )
    (comp (ref "R72")
      (value "1k")
      (footprint "eagle-import:RESC1005X40N")
      (libsource (lib "eagle-import") (part "R_402"))
    )
    (comp (ref "R73")
      (value "1k")
      (footprint "eagle-import:RESC1005X40N")
      (libsource (lib "eagle-import") (part "R_402"))
    )
    (comp (ref "R74")
      (value "10k")
      (footprint "eagle-import:RESC1005X40N")
      (libsource (lib "eagle-import") (part "R_402"))
    )
    (comp (ref "R75")
      (value "1k")
      (footprint "eagle-import:RESC1005X40N")
      (libsource (lib "eagle-import") (part "R_402"))
    )
    (comp (ref "R76")
      (value "10k")
      (footprint "eagle-import:RESC1005X40N")
      (libsource (lib "eagle-import") (part "R_402"))
    )
    (comp (ref "R77")
      (value "20k")
      (footprint "eagle-import:RESC1005X40N")
      (libsource (lib "eagle-import") (part "R_402"))
    )
    (comp (ref "R78")
      (value "0.01")
      (footprint "eagle-import:RESC1608X50AN")
      (libsource (lib "eagle-import") (part "R_603"))
    )
    (comp (ref "R79")
      (value "10k")
      (footprint "eagle-import:RESC1005X40N")
      (libsource (lib "eagle-import") (part "R_402"))
    )
    (comp (ref "R80")
      (value "560")
      (footprint "eagle-import:RESC1005X40N")
      (libsource (lib "eagle-import") (part "R_402"))
    )
    (comp (ref "R81")
      (value "10k")
      (footprint "eagle-import:RESC1005X40N")
      (libsource (lib "eagle-import") (part "R_402"))
    )
    (comp (ref "R82")
      (value "20k")
      (footprint "eagle-import:RESC1005X40N")
      (libsource (lib "eagle-import") (part "R_402"))
    )
    (comp (ref "R83")
      (value "0.01")
      (footprint "eagle-import:RESC1608X50AN")
      (libsource (lib "eagle-import") (part "R_603"))
    )
    (comp (ref "R84")
      (value "10k")
      (footprint "eagle-import:RESC1005X40N")
      (libsource (lib "eagle-import") (part "R_402"))
    )
    (comp (ref "R85")
      (value "560")
      (footprint "eagle-import:RESC1005X40N")
      (libsource (lib "eagle-import") (part "R_402"))
    )
    (comp (ref "R86")
      (value "10k")
      (footprint "eagle-import:RESC1005X40N")
      (libsource (lib "eagle-import") (part "R_402"))
    )
    (comp (ref "R87")
      (value "20k")
      (footprint "eagle-import:RESC1005X40N")
      (libsource (lib "eagle-import") (part "R_402"))
    )
    (comp (ref "R88")
      (value "0.01")
      (footprint "eagle-import:RESC1608X50AN")
      (libsource (lib "eagle-import") (part "R_603"))
    )
    (comp (ref "C1")
      (value "100n")
      (footprint "eagle-import:CAPC1005X55N")
      (libsource (lib "eagle-import") (part "C_402"))
    )
    (comp (ref "C2")
      (value "470u")
      (footprint "eagle-import:CAPAE835X1020N")
      (libsource (lib "eagle-import") (part "CPOL"))
    )
    (comp (ref "C3")
      (value "100n")
      (footprint "eagle-import:CAPC1005X55N")
      (libsource (lib "eagle-import") (part "C_402"))
    )
    (comp (ref "C4")
      (value "100p")
      (footprint "eagle-import:CAPC1005X55N")
      (libsource (lib "eagle-import") (part "C_402"))
    )
    (comp (ref "C5")
      (value "100n")
      (footprint "eagle-import:CAPC1005X55N")
      (libsource (lib "eagle-import") (part "C_402"))
    )
    (comp (ref "C6")
      (value "470u")
      (footprint "eagle-import:CAPAE835X1020N")
      (libsource (lib "eagle-import") (part "CPOL"))
    )
    (comp (ref "C7")
      (value "100n")
      (footprint "eagle-import:CAPC1005X55N")
      (libsource (lib "eagle-import") (part "C_402"))
    )
    (comp (ref "C8")
      (value "100n")
      (footprint "eagle-import:CAPC1005X55N")
      (libsource (lib "eagle-import") (part "C_402"))
    )
    (comp (ref "C9")
      (value "100n")
      (footprint "eagle-import:CAPC1005X55N")
      (libsource (lib "eagle-import") (part "C_402"))
    )
    (comp (ref "C10")
      (value "100n")
      (footprint "eagle-import:CAPC1005X55N")
      (libsource (lib "eagle-import") (part "C_402"))
    )
    (comp (ref "C11")
      (value "100n")
      (footprint "eagle-import:CAPC2013X100N")
      (libsource (lib "eagle-import") (part "C_805"))
    )
    (comp (ref "C12")
      (value "220u")
      (footprint "eagle-import:CAPAE835X1020N")
      (libsource (lib "eagle-import") (part "CPOL"))
    )
    (comp (ref "C13")
      (value "10u")
      (footprint "eagle-import:CAPC2013X100N")
      (libsource (lib "eagle-import") (part "C_805"))
    )
    (comp (ref "C14")
      (value "10u")
      (footprint "eagle-import:CAPC2013X100N")
      (libsource (lib "eagle-import") (part "C_805"))
    )
    (comp (ref "C15")
      (value "470u")
      (footprint "eagle-import:CAPAE835X1020N")
      (libsource (lib "eagle-import") (part "CPOL"))
    )
    (comp (ref "C16")
      (value "10u")
      (footprint "eagle-import:CAPC2013X100N")
      (libsource (lib "eagle-import") (part "C_805"))
    )
    (comp (ref "C17")
      (value "10u")
      (footprint "eagle-import:CAPC2013X100N")
      (libsource (lib "eagle-import") (part "C_805"))
    )
    (comp (ref "C18")
      (value "470u")
      (footprint "eagle-import:CAPAE835X1020N")
      (libsource (lib "eagle-import") (part "CPOL"))
    )
    (comp (ref "C19")
      (value "22n")
      (footprint "eagle-import:CAPC1005X55N")
      (libsource (lib "eagle-import") (part "C_402"))
    )
    (comp (ref "C20")
      (value "10u")
      (footprint "eagle-import:CAPC2013X100N")
      (libsource (lib "eagle-import") (part "C_805"))
    )
    (comp (ref "C21")
      (value "10u")
      (footprint "eagle-import:CAPC2013X100N")
      (libsource (lib "eagle-import") (part "C_805"))
    )
    (comp (ref "C22")
      (value "470u")
      (footprint "eagle-import:CAPAE835X1020N")
      (libsource (lib "eagle-import") (part "CPOL"))
    )
    (comp (ref "C23")
      (value "1n")
      (footprint "eagle-import:CAPC1005X55N")
      (libsource (lib "eagle-import") (part "C_402"))
    )
    (comp (ref "C24")
      (value "10u")
      (footprint "eagle-import:CAPC2013X100N")
      (libsource (lib "eagle-import") (part "C_805"))
    )
    (comp (ref "C25")
      (value "10u")
      (footprint "eagle-import:CAPC2013X100N")
      (libsource (lib "eagle-import") (part "C_805"))
    )
    (comp (ref "C26")
      (value "470u")
      (footprint "eagle-import:CAPAE835X1020N")
      (libsource (lib "eagle-import") (part "CPOL"))
    )
    (comp (ref "C27")
      (value "nc")
      (footprint "eagle-import:CAPC1005X55N")
      (libsource (lib "eagle-import") (part "C_402"))
    )
    (comp (ref "CON1")
      (value "ELEC")
      (footprint "eagle-import:PHOENIX381P900X920-2N")
      (libsource (lib "eagle-import") (part "CON2_3.81"))
    )
    (comp (ref "CON2")
      (value "SERVO")
      (footprint "eagle-import:PHOENIX381P900X920-2N")
      (libsource (lib "eagle-import") (part "CON2_3.81"))
    )
    (comp (ref "CON3")
      (value "LIPO_MOT")
      (footprint "eagle-import:PHOENIX381P900X920-2N")
      (libsource (lib "eagle-import") (part "CON2_3.81"))
    )
    (comp (ref "CON4")
      (value "LIPO_MOT")
      (footprint "eagle-import:PHOENIX381P900X920-2N")
      (libsource (lib "eagle-import") (part "CON2_3.81"))
    )
    (comp (ref "CON5")
      (value "LIPO_MOT")
      (footprint "eagle-import:PHOENIX381P900X920-2N")
      (libsource (lib "eagle-import") (part "CON2_3.81"))
    )
    (comp (ref "CON6")
      (value "LIPO_MOT")
      (footprint "eagle-import:PHOENIX381P900X920-2N")
      (libsource (lib "eagle-import") (part "CON2_3.81"))
    )
    (comp (ref "CON7")
      (value "FPGApower")
      (footprint "eagle-import:PHOENIX381P900X920-2N")
      (libsource (lib "eagle-import") (part "CON2_3.81"))
    )
    (comp (ref "D1")
      (value "SMP12A")
      (footprint "eagle-import:DO220AA")
      (libsource (lib "eagle-import") (part "ZENER"))
    )
    (comp (ref "D2")
      (value "SMP12A")
      (footprint "eagle-import:DO220AA")
      (libsource (lib "eagle-import") (part "ZENER"))
    )
    (comp (ref "D3")
      (value "SMAJ51A")
      (footprint "eagle-import:D0214AC")
      (libsource (lib "eagle-import") (part "ZENERDO214"))
    )
    (comp (ref "D4")
      (value "LED_603")
      (footprint "eagle-import:LEDC1608X60N")
      (libsource (lib "eagle-import") (part "LED_603"))
    )
    (comp (ref "D5")
      (value "LED_603")
      (footprint "eagle-import:LEDC1608X60N")
      (libsource (lib "eagle-import") (part "LED_603"))
    )
    (comp (ref "D6")
      (value "LED_603")
      (footprint "eagle-import:LEDC1608X60N")
      (libsource (lib "eagle-import") (part "LED_603"))
    )
    (comp (ref "D7")
      (value "LED_603")
      (footprint "eagle-import:LEDC1608X60N")
      (libsource (lib "eagle-import") (part "LED_603"))
    )
    (comp (ref "D8")
      (value "LED_603")
      (footprint "eagle-import:LEDC1608X60N")
      (libsource (lib "eagle-import") (part "LED_603"))
    )
    (comp (ref "J1")
      (value "NC")
      (footprint "eagle-import:JUMC1608X50AN")
      (libsource (lib "eagle-import") (part "JUMP_603"))
    )
    (comp (ref "J2")
      (value "nc")
      (footprint "eagle-import:JUMC1005X50N")
      (libsource (lib "eagle-import") (part "JUMP_402"))
    )
    (comp (ref "J3")
      (value "0")
      (footprint "eagle-import:JUMC1005X50N")
      (libsource (lib "eagle-import") (part "JUMP_402"))
    )
    (comp (ref "R1")
      (value "100k")
      (footprint "eagle-import:RESC1005X40N")
      (libsource (lib "eagle-import") (part "R_402"))
    )
    (comp (ref "R2")
      (value "100k")
      (footprint "eagle-import:RESC1005X40N")
      (libsource (lib "eagle-import") (part "R_402"))
    )
    (comp (ref "R3")
      (value "100k")
      (footprint "eagle-import:RESC1005X40N")
      (libsource (lib "eagle-import") (part "R_402"))
    )
    (comp (ref "R4")
      (value "100k")
      (footprint "eagle-import:RESC1005X40N")
      (libsource (lib "eagle-import") (part "R_402"))
    )
    (comp (ref "R5")
      (value "5k")
      (footprint "eagle-import:RESC1005X40N")
      (libsource (lib "eagle-import") (part "R_402"))
    )
    (comp (ref "R6")
      (value "5k")
      (footprint "eagle-import:RESC1005X40N")
      (libsource (lib "eagle-import") (part "R_402"))
    )
    (comp (ref "R7")
      (value "5k")
      (footprint "eagle-import:RESC1005X40N")
      (libsource (lib "eagle-import") (part "R_402"))
    )
    (comp (ref "R8")
      (value "5k")
      (footprint "eagle-import:RESC1005X40N")
      (libsource (lib "eagle-import") (part "R_402"))
    )
    (comp (ref "R9")
      (value "240")
      (footprint "eagle-import:RESC1005X40N")
      (libsource (lib "eagle-import") (part "R_402"))
    )
    (comp (ref "R10")
      (value "560")
      (footprint "eagle-import:RESC1005X40N")
      (libsource (lib "eagle-import") (part "R_402"))
    )
    (comp (ref "R11")
      (value "560")
      (footprint "eagle-import:RESC1005X40N")
      (libsource (lib "eagle-import") (part "R_402"))
    )
    (comp (ref "R12")
      (value "560")
      (footprint "eagle-import:RESC1005X40N")
      (libsource (lib "eagle-import") (part "R_402"))
    )
    (comp (ref "R13")
      (value "560")
      (footprint "eagle-import:RESC1005X40N")
      (libsource (lib "eagle-import") (part "R_402"))
    )
    (comp (ref "R14")
      (value "5k")
      (footprint "eagle-import:RESC1005X40N")
      (libsource (lib "eagle-import") (part "R_402"))
    )
    (comp (ref "R15")
      (value "100k")
      (footprint "eagle-import:RESC1005X40N")
      (libsource (lib "eagle-import") (part "R_402"))
    )
    (comp (ref "R16")
      (value "32k")
      (footprint "eagle-import:RESC1005X40N")
      (libsource (lib "eagle-import") (part "R_402"))
    )
    (comp (ref "R17")
      (value "100k")
      (footprint "eagle-import:RESC1005X40N")
      (libsource (lib "eagle-import") (part "R_402"))
    )
    (comp (ref "R18")
      (value "19k")
      (footprint "eagle-import:RESC1005X40N")
      (libsource (lib "eagle-import") (part "R_402"))
    )
    (comp (ref "R19")
      (value "100k")
      (footprint "eagle-import:RESC1005X40N")
      (libsource (lib "eagle-import") (part "R_402"))
    )
    (comp (ref "R20")
      (value "19k")
      (footprint "eagle-import:RESC1005X40N")
      (libsource (lib "eagle-import") (part "R_402"))
    )
    (comp (ref "T1")
      (value "MOSFET_NTR5198NL")
      (footprint "eagle-import:SOT95P290X130-3N")
      (libsource (lib "eagle-import") (part "MOSFET_NTR5198NL"))
    )
    (comp (ref "U1")
      (value "SN74LV4052A_SO")
      (footprint "eagle-import:SOIC127P780X200-16N")
      (libsource (lib "eagle-import") (part "SN74LV4052A_SO"))
    )
    (comp (ref "U2")
      (value "BUZZER")
      (footprint "eagle-import:BUZZER_CIRCLE")
      (libsource (lib "eagle-import") (part "BUZZER"))
    )
    (comp (ref "U3")
      (value "PTR08100W")
      (footprint "eagle-import:PTR08100W")
      (libsource (lib "eagle-import") (part "PTR08100W"))
    )
    (comp (ref "U4")
      (value "TPS82130")
      (footprint "eagle-import:SON65P310X290X153-9N")
      (libsource (lib "eagle-import") (part "TPS82130"))
    )
    (comp (ref "U5")
      (value "TPS82130")
      (footprint "eagle-import:SON65P310X290X153-9N")
      (libsource (lib "eagle-import") (part "TPS82130"))
    )
    (comp (ref "U6")
      (value "TPS82130")
      (footprint "eagle-import:SON65P310X290X153-9N")
      (libsource (lib "eagle-import") (part "TPS82130"))
    )
    (comp (ref "C91")
      (value "470u")
      (footprint "eagle-import:CAPAE835X1020N")
      (libsource (lib "eagle-import") (part "CPOL"))
    )
    (comp (ref "C92")
      (value "10n")
      (footprint "eagle-import:CAPC1005X55N")
      (libsource (lib "eagle-import") (part "C_402"))
    )
    (comp (ref "C93")
      (value "100n")
      (footprint "eagle-import:CAPC1005X55N")
      (libsource (lib "eagle-import") (part "C_402"))
    )
    (comp (ref "C94")
      (value "100n")
      (footprint "eagle-import:CAPC1005X55N")
      (libsource (lib "eagle-import") (part "C_402"))
    )
    (comp (ref "C95")
      (value "1n")
      (footprint "eagle-import:CAPC1005X55N")
      (libsource (lib "eagle-import") (part "C_402"))
    )
    (comp (ref "C96")
      (value "1n")
      (footprint "eagle-import:CAPC1005X55N")
      (libsource (lib "eagle-import") (part "C_402"))
    )
    (comp (ref "C97")
      (value "10n")
      (footprint "eagle-import:CAPC1005X55N")
      (libsource (lib "eagle-import") (part "C_402"))
    )
    (comp (ref "C98")
      (value "100n")
      (footprint "eagle-import:CAPC1005X55N")
      (libsource (lib "eagle-import") (part "C_402"))
    )
    (comp (ref "C99")
      (value "100n")
      (footprint "eagle-import:CAPC1005X55N")
      (libsource (lib "eagle-import") (part "C_402"))
    )
    (comp (ref "CON14")
      (value "ESC0")
      (footprint "eagle-import:PHOENIX381P1662X920-4N")
      (libsource (lib "eagle-import") (part "CON4_3.81"))
    )
    (comp (ref "CON15")
      (value "CON10_2_2.54")
      (footprint "eagle-import:CON245P2030X890-2X5N")
      (libsource (lib "eagle-import") (part "CON10_2_2.54"))
    )
    (comp (ref "CON16")
      (value "CON10_2_2.54")
      (footprint "eagle-import:CON245P2030X890-2X5N")
      (libsource (lib "eagle-import") (part "CON10_2_2.54"))
    )
    (comp (ref "CON17")
      (value "ESC1")
      (footprint "eagle-import:PHOENIX381P1662X920-4N")
      (libsource (lib "eagle-import") (part "CON4_3.81"))
    )
    (comp (ref "J24")
      (value "nc")
      (footprint "eagle-import:JUMC1608X50AN")
      (libsource (lib "eagle-import") (part "JUMP_603"))
    )
    (comp (ref "J25")
      (value "0")
      (footprint "eagle-import:JUMC1608X50AN")
      (libsource (lib "eagle-import") (part "JUMP_603"))
    )
    (comp (ref "J26")
      (value "0")
      (footprint "eagle-import:JUMC1005X50N")
      (libsource (lib "eagle-import") (part "JUMP_402"))
    )
    (comp (ref "J27")
      (value "nc")
      (footprint "eagle-import:JUMC1005X50N")
      (libsource (lib "eagle-import") (part "JUMP_402"))
    )
    (comp (ref "K1")
      (value "RELAY_V23101-SMT")
      (footprint "eagle-import:V23101-D0103-A201-SMT")
      (libsource (lib "eagle-import") (part "RELAY_V23101-SMT"))
    )
    (comp (ref "K2")
      (value "RELAY_V23101-SMT")
      (footprint "eagle-import:V23101-D0103-A201-SMT")
      (libsource (lib "eagle-import") (part "RELAY_V23101-SMT"))
    )
    (comp (ref "K3")
      (value "RELAY_V23101-SMT")
      (footprint "eagle-import:V23101-D0103-A201-SMT")
      (libsource (lib "eagle-import") (part "RELAY_V23101-SMT"))
    )
    (comp (ref "K4")
      (value "RELAY_V23101-SMT")
      (footprint "eagle-import:V23101-D0103-A201-SMT")
      (libsource (lib "eagle-import") (part "RELAY_V23101-SMT"))
    )
    (comp (ref "R35")
      (value "10k")
      (footprint "eagle-import:RESC1005X40N")
      (libsource (lib "eagle-import") (part "R_402"))
    )
    (comp (ref "R36")
      (value "ULR15S-R0055FT2")
      (footprint "eagle-import:RESC_ULR15S-R0055FT2")
      (libsource (lib "eagle-import") (part "R_ULR15S-R0055FT2"))
    )
    (comp (ref "R37")
      (value "10k")
      (footprint "eagle-import:RESC1005X40N")
      (libsource (lib "eagle-import") (part "R_402"))
    )
    (comp (ref "R38")
      (value "ULR15S-R0055FT2")
      (footprint "eagle-import:RESC_ULR15S-R0055FT2")
      (libsource (lib "eagle-import") (part "R_ULR15S-R0055FT2"))
    )
    (comp (ref "T2")
      (value "MOSFET_NTR5198NL")
      (footprint "eagle-import:SOT95P290X130-3N")
      (libsource (lib "eagle-import") (part "MOSFET_NTR5198NL"))
    )
    (comp (ref "T3")
      (value "MOSFET_NTR5198NL")
      (footprint "eagle-import:SOT95P290X130-3N")
      (libsource (lib "eagle-import") (part "MOSFET_NTR5198NL"))
    )
    (comp (ref "U16")
      (value "INA240-A2")
      (footprint "eagle-import:TSSOP")
      (libsource (lib "eagle-import") (part "INA240-TSSOP"))
    )
    (comp (ref "U17")
      (value "ESC_TURNIGY40A")
      (footprint "eagle-import:ESC_TURNIGY40A")
      (libsource (lib "eagle-import") (part "ESC_TURNIGY40A"))
    )
    (comp (ref "U18")
      (value "INA240-A2")
      (footprint "eagle-import:TSSOP")
      (libsource (lib "eagle-import") (part "INA240-TSSOP"))
    )
    (comp (ref "U19")
      (value "ESC_CHINOI15A")
      (footprint "eagle-import:ESC_CHINOI15A")
      (libsource (lib "eagle-import") (part "ESC_CHINOI15A"))
    )
    (comp (ref "C159")
      (value "100n")
      (footprint "eagle-import:CAPC1005X55N")
      (libsource (lib "eagle-import") (part "C_402"))
    )
    (comp (ref "C160")
      (value "100n")
      (footprint "eagle-import:CAPC1005X55N")
      (libsource (lib "eagle-import") (part "C_402"))
    )
    (comp (ref "C161")
      (value "100n")
      (footprint "eagle-import:CAPC1005X55N")
      (libsource (lib "eagle-import") (part "C_402"))
    )
    (comp (ref "C162")
      (value "100n")
      (footprint "eagle-import:CAPC1005X55N")
      (libsource (lib "eagle-import") (part "C_402"))
    )
    (comp (ref "C163")
      (value "100n")
      (footprint "eagle-import:CAPC1005X55N")
      (libsource (lib "eagle-import") (part "C_402"))
    )
    (comp (ref "C164")
      (value "100n")
      (footprint "eagle-import:CAPC1005X55N")
      (libsource (lib "eagle-import") (part "C_402"))
    )
    (comp (ref "C165")
      (value "100n")
      (footprint "eagle-import:CAPC1005X55N")
      (libsource (lib "eagle-import") (part "C_402"))
    )
    (comp (ref "C166")
      (value "2.2u")
      (footprint "eagle-import:CAPC1608X95N")
      (libsource (lib "eagle-import") (part "C_603"))
    )
    (comp (ref "C167")
      (value "100n")
      (footprint "eagle-import:CAPC1005X55N")
      (libsource (lib "eagle-import") (part "C_402"))
    )
    (comp (ref "C168")
      (value "8p")
      (footprint "eagle-import:CAPC1005X55N")
      (libsource (lib "eagle-import") (part "C_402"))
    )
    (comp (ref "C169")
      (value "8p")
      (footprint "eagle-import:CAPC1005X55N")
      (libsource (lib "eagle-import") (part "C_402"))
    )
    (comp (ref "C170")
      (value "22n")
      (footprint "eagle-import:CAPC1005X55N")
      (libsource (lib "eagle-import") (part "C_402"))
    )
    (comp (ref "C171")
      (value "100n")
      (footprint "eagle-import:CAPC1005X55N")
      (libsource (lib "eagle-import") (part "C_402"))
    )
    (comp (ref "C172")
      (value "100n")
      (footprint "eagle-import:CAPC1005X55N")
      (libsource (lib "eagle-import") (part "C_402"))
    )
    (comp (ref "C173")
      (value "100n")
      (footprint "eagle-import:CAPC1005X55N")
      (libsource (lib "eagle-import") (part "C_402"))
    )
    (comp (ref "C174")
      (value "100n")
      (footprint "eagle-import:CAPC1005X55N")
      (libsource (lib "eagle-import") (part "C_402"))
    )
    (comp (ref "C175")
      (value "1u")
      (footprint "eagle-import:CAPC1608X95N")
      (libsource (lib "eagle-import") (part "C_603"))
    )
    (comp (ref "C176")
      (value "10u")
      (footprint "eagle-import:CAPC2013X100N")
      (libsource (lib "eagle-import") (part "C_805"))
    )
    (comp (ref "C177")
      (value "10n")
      (footprint "eagle-import:CAPC1005X55N")
      (libsource (lib "eagle-import") (part "C_402"))
    )
    (comp (ref "C178")
      (value "100p")
      (footprint "eagle-import:CAPC1005X55N")
      (libsource (lib "eagle-import") (part "C_402"))
    )
    (comp (ref "C179")
      (value "1u")
      (footprint "eagle-import:CAPC1608X95N")
      (libsource (lib "eagle-import") (part "C_603"))
    )
    (comp (ref "C180")
      (value "10u")
      (footprint "eagle-import:CAPC2013X100N")
      (libsource (lib "eagle-import") (part "C_805"))
    )
    (comp (ref "C216")
      (value "100n")
      (footprint "eagle-import:CAPC1005X55N")
      (libsource (lib "eagle-import") (part "C_402"))
    )
    (comp (ref "C217")
      (value "100n")
      (footprint "eagle-import:CAPC1005X55N")
      (libsource (lib "eagle-import") (part "C_402"))
    )
    (comp (ref "C219")
      (value "100n")
      (footprint "eagle-import:CAPC1005X55N")
      (libsource (lib "eagle-import") (part "C_402"))
    )
    (comp (ref "C220")
      (value "2.2u")
      (footprint "eagle-import:CAPC1608X95N")
      (libsource (lib "eagle-import") (part "C_603"))
    )
    (comp (ref "IC1")
      (value "ADS1258")
      (footprint "eagle-import:QFN48")
      (libsource (lib "eagle-import") (part "ADS1258"))
    )
    (comp (ref "IC2")
      (value "ADS1278")
      (footprint "eagle-import:TQFP64_POWERPAD")
      (libsource (lib "eagle-import") (part "ADS1278{dblquote}"))
    )
    (comp (ref "IC3")
      (value "REF5030I")
      (footprint "eagle-import:MSOP8_0.65")
      (libsource (lib "eagle-import") (part "REF5025I"))
    )
    (comp (ref "IC4")
      (value "REF5025I")
      (footprint "eagle-import:MSOP8_0.65")
      (libsource (lib "eagle-import") (part "REF5025I"))
    )
    (comp (ref "J28")
      (value "nc")
      (footprint "eagle-import:JUMC1005X50N")
      (libsource (lib "eagle-import") (part "JUMP_402"))
    )
    (comp (ref "J29")
      (value "0")
      (footprint "eagle-import:JUMC1005X50N")
      (libsource (lib "eagle-import") (part "JUMP_402"))
    )
    (comp (ref "J30")
      (value "nc")
      (footprint "eagle-import:JUMC1005X50N")
      (libsource (lib "eagle-import") (part "JUMP_402"))
    )
    (comp (ref "J31")
      (value "0")
      (footprint "eagle-import:JUMC1005X50N")
      (libsource (lib "eagle-import") (part "JUMP_402"))
    )
    (comp (ref "J32")
      (value "0")
      (footprint "eagle-import:JUMC1005X50N")
      (libsource (lib "eagle-import") (part "JUMP_402"))
    )
    (comp (ref "J50")
      (value "0")
      (footprint "eagle-import:JUMC1005X50N")
      (libsource (lib "eagle-import") (part "JUMP_402"))
    )
    (comp (ref "J51")
      (value "0")
      (footprint "eagle-import:JUMC1005X50N")
      (libsource (lib "eagle-import") (part "JUMP_402"))
    )
    (comp (ref "Q2")
      (value "32.768kHz")
      (footprint "eagle-import:1206")
      (libsource (lib "eagle-import") (part "QUARTZ_1206"))
    )
    (comp (ref "R97")
      (value "10k")
      (footprint "eagle-import:RESC1005X40N")
      (libsource (lib "eagle-import") (part "R_402"))
    )
    (comp (ref "R98")
      (value "1M")
      (footprint "eagle-import:RESC1005X40N")
      (libsource (lib "eagle-import") (part "R_402"))
    )
    (comp (ref "U23")
      (value "LP5900_2.2")
      (footprint "eagle-import:SON65P250X220X80-7N")
      (libsource (lib "eagle-import") (part "REG_EN_LP5900"))
    )
    (comp (ref "U24")
      (value "OPA376")
      (footprint "eagle-import:SC70-5N")
      (libsource (lib "eagle-import") (part "OPA376"))
    )
    (comp (ref "U37")
      (value "MPU-9250")
      (footprint "eagle-import:QFN24-3X3")
      (libsource (lib "eagle-import") (part "MPU-9250"))
    )
    (comp (ref "U38")
      (value "LP5900_3")
      (footprint "eagle-import:SON65P250X220X80-7N")
      (libsource (lib "eagle-import") (part "REG_EN_LP5900"))
    )
    (comp (ref "C28")
      (value "100n")
      (footprint "eagle-import:CAPC1005X55N")
      (libsource (lib "eagle-import") (part "C_402"))
    )
    (comp (ref "C29")
      (value "1µ")
      (footprint "eagle-import:CAPC1608X95N")
      (libsource (lib "eagle-import") (part "C_603"))
    )
    (comp (ref "C30")
      (value "1µ")
      (footprint "eagle-import:CAPC1608X95N")
      (libsource (lib "eagle-import") (part "C_603"))
    )
    (comp (ref "C31")
      (value "1µ")
      (footprint "eagle-import:CAPC1608X95N")
      (libsource (lib "eagle-import") (part "C_603"))
    )
    (comp (ref "C32")
      (value "1µ")
      (footprint "eagle-import:CAPC1608X95N")
      (libsource (lib "eagle-import") (part "C_603"))
    )
    (comp (ref "C33")
      (value "100n")
      (footprint "eagle-import:CAPC1608X95N")
      (libsource (lib "eagle-import") (part "C_603"))
    )
    (comp (ref "C34")
      (value "100n")
      (footprint "eagle-import:CAPC1608X95N")
      (libsource (lib "eagle-import") (part "C_603"))
    )
    (comp (ref "C35")
      (value "100n")
      (footprint "eagle-import:CAPC1608X95N")
      (libsource (lib "eagle-import") (part "C_603"))
    )
    (comp (ref "C36")
      (value "100n")
      (footprint "eagle-import:CAPC1608X95N")
      (libsource (lib "eagle-import") (part "C_603"))
    )
    (comp (ref "C37")
      (value "100n")
      (footprint "eagle-import:CAPC1005X55N")
      (libsource (lib "eagle-import") (part "C_402"))
    )
    (comp (ref "C38")
      (value "1µ")
      (footprint "eagle-import:CAPC1608X95N")
      (libsource (lib "eagle-import") (part "C_603"))
    )
    (comp (ref "C39")
      (value "1µ")
      (footprint "eagle-import:CAPC1608X95N")
      (libsource (lib "eagle-import") (part "C_603"))
    )
    (comp (ref "C40")
      (value "1µ")
      (footprint "eagle-import:CAPC1608X95N")
      (libsource (lib "eagle-import") (part "C_603"))
    )
    (comp (ref "C41")
      (value "1µ")
      (footprint "eagle-import:CAPC1608X95N")
      (libsource (lib "eagle-import") (part "C_603"))
    )
    (comp (ref "C42")
      (value "100n")
      (footprint "eagle-import:CAPC1608X95N")
      (libsource (lib "eagle-import") (part "C_603"))
    )
    (comp (ref "C43")
      (value "100n")
      (footprint "eagle-import:CAPC1608X95N")
      (libsource (lib "eagle-import") (part "C_603"))
    )
    (comp (ref "C44")
      (value "100n")
      (footprint "eagle-import:CAPC1608X95N")
      (libsource (lib "eagle-import") (part "C_603"))
    )
    (comp (ref "C45")
      (value "100n")
      (footprint "eagle-import:CAPC1608X95N")
      (libsource (lib "eagle-import") (part "C_603"))
    )
    (comp (ref "C46")
      (value "100n")
      (footprint "eagle-import:CAPC1005X55N")
      (libsource (lib "eagle-import") (part "C_402"))
    )
    (comp (ref "C47")
      (value "1µ")
      (footprint "eagle-import:CAPC1608X95N")
      (libsource (lib "eagle-import") (part "C_603"))
    )
    (comp (ref "C48")
      (value "1µ")
      (footprint "eagle-import:CAPC1608X95N")
      (libsource (lib "eagle-import") (part "C_603"))
    )
    (comp (ref "C49")
      (value "1µ")
      (footprint "eagle-import:CAPC1608X95N")
      (libsource (lib "eagle-import") (part "C_603"))
    )
    (comp (ref "C50")
      (value "1µ")
      (footprint "eagle-import:CAPC1608X95N")
      (libsource (lib "eagle-import") (part "C_603"))
    )
    (comp (ref "C51")
      (value "100n")
      (footprint "eagle-import:CAPC1608X95N")
      (libsource (lib "eagle-import") (part "C_603"))
    )
    (comp (ref "C52")
      (value "100n")
      (footprint "eagle-import:CAPC1608X95N")
      (libsource (lib "eagle-import") (part "C_603"))
    )
    (comp (ref "C53")
      (value "100n")
      (footprint "eagle-import:CAPC1608X95N")
      (libsource (lib "eagle-import") (part "C_603"))
    )
    (comp (ref "C54")
      (value "100n")
      (footprint "eagle-import:CAPC1608X95N")
      (libsource (lib "eagle-import") (part "C_603"))
    )
    (comp (ref "C55")
      (value "100n")
      (footprint "eagle-import:CAPC1608X95N")
      (libsource (lib "eagle-import") (part "C_603"))
    )
    (comp (ref "C56")
      (value "1n")
      (footprint "eagle-import:CAPC1005X55N")
      (libsource (lib "eagle-import") (part "C_402"))
    )
    (comp (ref "C57")
      (value "10n")
      (footprint "eagle-import:CAPC1005X55N")
      (libsource (lib "eagle-import") (part "C_402"))
    )
    (comp (ref "C58")
      (value "1n")
      (footprint "eagle-import:CAPC1005X55N")
      (libsource (lib "eagle-import") (part "C_402"))
    )
    (comp (ref "C59")
      (value "10n")
      (footprint "eagle-import:CAPC1005X55N")
      (libsource (lib "eagle-import") (part "C_402"))
    )
    (comp (ref "C60")
      (value "100n")
      (footprint "eagle-import:CAPC1608X95N")
      (libsource (lib "eagle-import") (part "C_603"))
    )
    (comp (ref "C61")
      (value "100n")
      (footprint "eagle-import:CAPC1608X95N")
      (libsource (lib "eagle-import") (part "C_603"))
    )
    (comp (ref "C62")
      (value "100n")
      (footprint "eagle-import:CAPC1608X95N")
      (libsource (lib "eagle-import") (part "C_603"))
    )
    (comp (ref "C63")
      (value "100n")
      (footprint "eagle-import:CAPC1608X95N")
      (libsource (lib "eagle-import") (part "C_603"))
    )
    (comp (ref "C64")
      (value "100n")
      (footprint "eagle-import:CAPC1608X95N")
      (libsource (lib "eagle-import") (part "C_603"))
    )
    (comp (ref "C65")
      (value "100n")
      (footprint "eagle-import:CAPC1608X95N")
      (libsource (lib "eagle-import") (part "C_603"))
    )
    (comp (ref "C66")
      (value "100n")
      (footprint "eagle-import:CAPC1608X95N")
      (libsource (lib "eagle-import") (part "C_603"))
    )
    (comp (ref "C67")
      (value "100n")
      (footprint "eagle-import:CAPC1005X55N")
      (libsource (lib "eagle-import") (part "C_402"))
    )
    (comp (ref "C68")
      (value "100n")
      (footprint "eagle-import:CAPC1608X95N")
      (libsource (lib "eagle-import") (part "C_603"))
    )
    (comp (ref "C69")
      (value "100n")
      (footprint "eagle-import:CAPC1608X95N")
      (libsource (lib "eagle-import") (part "C_603"))
    )
    (comp (ref "C70")
      (value "100n")
      (footprint "eagle-import:CAPC1608X95N")
      (libsource (lib "eagle-import") (part "C_603"))
    )
    (comp (ref "C71")
      (value "1n")
      (footprint "eagle-import:CAPC1005X55N")
      (libsource (lib "eagle-import") (part "C_402"))
    )
    (comp (ref "C72")
      (value "10n")
      (footprint "eagle-import:CAPC1005X55N")
      (libsource (lib "eagle-import") (part "C_402"))
    )
    (comp (ref "C73")
      (value "100n")
      (footprint "eagle-import:CAPC1005X55N")
      (libsource (lib "eagle-import") (part "C_402"))
    )
    (comp (ref "C74")
      (value "100n")
      (footprint "eagle-import:CAPC1608X95N")
      (libsource (lib "eagle-import") (part "C_603"))
    )
    (comp (ref "C75")
      (value "100n")
      (footprint "eagle-import:CAPC1005X55N")
      (libsource (lib "eagle-import") (part "C_402"))
    )
    (comp (ref "C76")
      (value "1n")
      (footprint "eagle-import:CAPC1005X55N")
      (libsource (lib "eagle-import") (part "C_402"))
    )
    (comp (ref "C77")
      (value "100n")
      (footprint "eagle-import:CAPC1608X95N")
      (libsource (lib "eagle-import") (part "C_603"))
    )
    (comp (ref "C78")
      (value "100n")
      (footprint "eagle-import:CAPC1608X95N")
      (libsource (lib "eagle-import") (part "C_603"))
    )
    (comp (ref "C79")
      (value "100n")
      (footprint "eagle-import:CAPC1608X95N")
      (libsource (lib "eagle-import") (part "C_603"))
    )
    (comp (ref "C80")
      (value "100n")
      (footprint "eagle-import:CAPC1608X95N")
      (libsource (lib "eagle-import") (part "C_603"))
    )
    (comp (ref "C81")
      (value "1µ")
      (footprint "eagle-import:CAPC1608X95N")
      (libsource (lib "eagle-import") (part "C_603"))
    )
    (comp (ref "C82")
      (value "1µ")
      (footprint "eagle-import:CAPC1608X95N")
      (libsource (lib "eagle-import") (part "C_603"))
    )
    (comp (ref "C83")
      (value "1µ")
      (footprint "eagle-import:CAPC1608X95N")
      (libsource (lib "eagle-import") (part "C_603"))
    )
    (comp (ref "C84")
      (value "1µ")
      (footprint "eagle-import:CAPC1608X95N")
      (libsource (lib "eagle-import") (part "C_603"))
    )
    (comp (ref "C85")
      (value "100n")
      (footprint "eagle-import:CAPC1608X95N")
      (libsource (lib "eagle-import") (part "C_603"))
    )
    (comp (ref "C86")
      (value "100n")
      (footprint "eagle-import:CAPC1608X95N")
      (libsource (lib "eagle-import") (part "C_603"))
    )
    (comp (ref "C87")
      (value "100n")
      (footprint "eagle-import:CAPC1608X95N")
      (libsource (lib "eagle-import") (part "C_603"))
    )
    (comp (ref "C88")
      (value "100n")
      (footprint "eagle-import:CAPC1608X95N")
      (libsource (lib "eagle-import") (part "C_603"))
    )
    (comp (ref "C89")
      (value "100n")
      (footprint "eagle-import:CAPC1005X55N")
      (libsource (lib "eagle-import") (part "C_402"))
    )
    (comp (ref "C90")
      (value "1n")
      (footprint "eagle-import:CAPC1005X55N")
      (libsource (lib "eagle-import") (part "C_402"))
    )
    (comp (ref "CON8")
      (value "M0")
      (footprint "eagle-import:PHOENIX381P900X920-2N")
      (libsource (lib "eagle-import") (part "CON2_3.81"))
    )
    (comp (ref "CON9")
      (value "M3")
      (footprint "eagle-import:PHOENIX381P900X920-2N")
      (libsource (lib "eagle-import") (part "CON2_3.81"))
    )
    (comp (ref "CON10")
      (value "M5")
      (footprint "eagle-import:PHOENIX381P900X920-2N")
      (libsource (lib "eagle-import") (part "CON2_3.81"))
    )
    (comp (ref "CON11")
      (value "M2")
      (footprint "eagle-import:PHOENIX381P900X920-2N")
      (libsource (lib "eagle-import") (part "CON2_3.81"))
    )
    (comp (ref "CON12")
      (value "M4")
      (footprint "eagle-import:PHOENIX381P900X920-2N")
      (libsource (lib "eagle-import") (part "CON2_3.81"))
    )
    (comp (ref "CON13")
      (value "M1")
      (footprint "eagle-import:PHOENIX381P900X920-2N")
      (libsource (lib "eagle-import") (part "CON2_3.81"))
    )
    (comp (ref "J4")
      (value "0")
      (footprint "eagle-import:JUMC1608X50AN")
      (libsource (lib "eagle-import") (part "JUMP_603"))
    )
    (comp (ref "J5")
      (value "nc")
      (footprint "eagle-import:JUMC1608X50AN")
      (libsource (lib "eagle-import") (part "JUMP_603"))
    )
    (comp (ref "J6")
      (value "0")
      (footprint "eagle-import:JUMC1608X50AN")
      (libsource (lib "eagle-import") (part "JUMP_603"))
    )
    (comp (ref "J7")
      (value "nc")
      (footprint "eagle-import:JUMC1608X50AN")
      (libsource (lib "eagle-import") (part "JUMP_603"))
    )
    (comp (ref "J8")
      (value "0")
      (footprint "eagle-import:JUMC1005X50N")
      (libsource (lib "eagle-import") (part "JUMP_402"))
    )
    (comp (ref "J9")
      (value "0")
      (footprint "eagle-import:JUMC1005X50N")
      (libsource (lib "eagle-import") (part "JUMP_402"))
    )
    (comp (ref "J10")
      (value "0")
      (footprint "eagle-import:JUMC1005X50N")
      (libsource (lib "eagle-import") (part "JUMP_402"))
    )
    (comp (ref "J11")
      (value "0")
      (footprint "eagle-import:JUMC1005X50N")
      (libsource (lib "eagle-import") (part "JUMP_402"))
    )
    (comp (ref "J12")
      (value "0")
      (footprint "eagle-import:JUMC1005X50N")
      (libsource (lib "eagle-import") (part "JUMP_402"))
    )
    (comp (ref "J13")
      (value "0")
      (footprint "eagle-import:JUMC1005X50N")
      (libsource (lib "eagle-import") (part "JUMP_402"))
    )
    (comp (ref "J14")
      (value "0")
      (footprint "eagle-import:JUMC1005X50N")
      (libsource (lib "eagle-import") (part "JUMP_402"))
    )
    (comp (ref "J15")
      (value "0")
      (footprint "eagle-import:JUMC1005X50N")
      (libsource (lib "eagle-import") (part "JUMP_402"))
    )
    (comp (ref "J16")
      (value "0")
      (footprint "eagle-import:JUMC1005X50N")
      (libsource (lib "eagle-import") (part "JUMP_402"))
    )
    (comp (ref "J17")
      (value "0")
      (footprint "eagle-import:JUMC1005X50N")
      (libsource (lib "eagle-import") (part "JUMP_402"))
    )
    (comp (ref "J18")
      (value "0")
      (footprint "eagle-import:JUMC1005X50N")
      (libsource (lib "eagle-import") (part "JUMP_402"))
    )
    (comp (ref "J19")
      (value "0")
      (footprint "eagle-import:JUMC1005X50N")
      (libsource (lib "eagle-import") (part "JUMP_402"))
    )
    (comp (ref "J20")
      (value "0")
      (footprint "eagle-import:JUMC1005X50N")
      (libsource (lib "eagle-import") (part "JUMP_402"))
    )
    (comp (ref "J21")
      (value "0")
      (footprint "eagle-import:JUMC1005X50N")
      (libsource (lib "eagle-import") (part "JUMP_402"))
    )
    (comp (ref "J22")
      (value "0")
      (footprint "eagle-import:JUMC1005X50N")
      (libsource (lib "eagle-import") (part "JUMP_402"))
    )
    (comp (ref "J23")
      (value "0")
      (footprint "eagle-import:JUMC1005X50N")
      (libsource (lib "eagle-import") (part "JUMP_402"))
    )
    (comp (ref "L1")
      (value "SRN2512-R24M")
      (footprint "eagle-import:INDC2520X120N")
      (libsource (lib "eagle-import") (part "INDUCTANCE_2520"))
    )
    (comp (ref "L2")
      (value "SRN2512-R24M")
      (footprint "eagle-import:INDC2520X120N")
      (libsource (lib "eagle-import") (part "INDUCTANCE_2520"))
    )
    (comp (ref "L3")
      (value "SRN2512-R24M")
      (footprint "eagle-import:INDC2520X120N")
      (libsource (lib "eagle-import") (part "INDUCTANCE_2520"))
    )
    (comp (ref "L4")
      (value "SRN2512-R24M")
      (footprint "eagle-import:INDC2520X120N")
      (libsource (lib "eagle-import") (part "INDUCTANCE_2520"))
    )
    (comp (ref "L5")
      (value "SRN2512-R24M")
      (footprint "eagle-import:INDC2520X120N")
      (libsource (lib "eagle-import") (part "INDUCTANCE_2520"))
    )
    (comp (ref "L6")
      (value "SRN2512-R24M")
      (footprint "eagle-import:INDC2520X120N")
      (libsource (lib "eagle-import") (part "INDUCTANCE_2520"))
    )
    (comp (ref "L7")
      (value "SRN2512-R24M")
      (footprint "eagle-import:INDC2520X120N")
      (libsource (lib "eagle-import") (part "INDUCTANCE_2520"))
    )
    (comp (ref "L8")
      (value "SRN2512-R24M")
      (footprint "eagle-import:INDC2520X120N")
      (libsource (lib "eagle-import") (part "INDUCTANCE_2520"))
    )
    (comp (ref "R21")
      (value "10k")
      (footprint "eagle-import:RESC1005X40N")
      (libsource (lib "eagle-import") (part "R_402"))
    )
    (comp (ref "R22")
      (value "10k")
      (footprint "eagle-import:RESC1005X40N")
      (libsource (lib "eagle-import") (part "R_402"))
    )
    (comp (ref "R23")
      (value "ULR15S-R0055FT2")
      (footprint "eagle-import:RESC_ULR15S-R0055FT2")
      (libsource (lib "eagle-import") (part "R_ULR15S-R0055FT2"))
    )
    (comp (ref "R24")
      (value "ULR15S-R0055FT2")
      (footprint "eagle-import:RESC_ULR15S-R0055FT2")
      (libsource (lib "eagle-import") (part "R_ULR15S-R0055FT2"))
    )
    (comp (ref "R25")
      (value "ULR15S-R0055FT2")
      (footprint "eagle-import:RESC_ULR15S-R0055FT2")
      (libsource (lib "eagle-import") (part "R_ULR15S-R0055FT2"))
    )
    (comp (ref "R26")
      (value "30k")
      (footprint "eagle-import:RESC1005X40N")
      (libsource (lib "eagle-import") (part "R_402"))
    )
    (comp (ref "R27")
      (value "10k")
      (footprint "eagle-import:RESC1005X40N")
      (libsource (lib "eagle-import") (part "R_402"))
    )
    (comp (ref "R28")
      (value "30k")
      (footprint "eagle-import:RESC1005X40N")
      (libsource (lib "eagle-import") (part "R_402"))
    )
    (comp (ref "R29")
      (value "ULR15S-R0055FT2")
      (footprint "eagle-import:RESC_ULR15S-R0055FT2")
      (libsource (lib "eagle-import") (part "R_ULR15S-R0055FT2"))
    )
    (comp (ref "R30")
      (value "30k")
      (footprint "eagle-import:RESC1005X40N")
      (libsource (lib "eagle-import") (part "R_402"))
    )
    (comp (ref "R31")
      (value "10k")
      (footprint "eagle-import:RESC1005X40N")
      (libsource (lib "eagle-import") (part "R_402"))
    )
    (comp (ref "R32")
      (value "ULR15S-R0055FT2")
      (footprint "eagle-import:RESC_ULR15S-R0055FT2")
      (libsource (lib "eagle-import") (part "R_ULR15S-R0055FT2"))
    )
    (comp (ref "R33")
      (value "30k")
      (footprint "eagle-import:RESC1005X40N")
      (libsource (lib "eagle-import") (part "R_402"))
    )
    (comp (ref "R34")
      (value "10k")
      (footprint "eagle-import:RESC1005X40N")
      (libsource (lib "eagle-import") (part "R_402"))
    )
    (comp (ref "U7")
      (value "INA240-A2")
      (footprint "eagle-import:TSSOP")
      (libsource (lib "eagle-import") (part "INA240-TSSOP"))
    )
    (comp (ref "U8")
      (value "INA240-A2")
      (footprint "eagle-import:TSSOP")
      (libsource (lib "eagle-import") (part "INA240-TSSOP"))
    )
    (comp (ref "U9")
      (value "DRV8432")
      (footprint "eagle-import:R-PDSO-G36")
      (libsource (lib "eagle-import") (part "DRV84X2_DRV8432"))
    )
    (comp (ref "U10")
      (value "DRV8432")
      (footprint "eagle-import:R-PDSO-G36")
      (libsource (lib "eagle-import") (part "DRV84X2_DRV8432"))
    )
    (comp (ref "U11")
      (value "DRV8432")
      (footprint "eagle-import:R-PDSO-G36")
      (libsource (lib "eagle-import") (part "DRV84X2_DRV8432"))
    )
    (comp (ref "U12")
      (value "INA240-A2")
      (footprint "eagle-import:TSSOP")
      (libsource (lib "eagle-import") (part "INA240-TSSOP"))
    )
    (comp (ref "U13")
      (value "INA240-A2")
      (footprint "eagle-import:TSSOP")
      (libsource (lib "eagle-import") (part "INA240-TSSOP"))
    )
    (comp (ref "U14")
      (value "DRV8432")
      (footprint "eagle-import:R-PDSO-G36")
      (libsource (lib "eagle-import") (part "DRV84X2_DRV8432"))
    )
    (comp (ref "U15")
      (value "INA240-A2")
      (footprint "eagle-import:TSSOP")
      (libsource (lib "eagle-import") (part "INA240-TSSOP"))
    )
  )
  (nets
    (net (code "1") (name "3V3") (class "Default")
      (node (ref "C138") (pin "2") (pinfunction "P$2_2") (pintype "bidirectional"))
      (node (ref "C139") (pin "2") (pinfunction "P$2_2") (pintype "bidirectional"))
      (node (ref "C140") (pin "2") (pinfunction "P$2_2") (pintype "bidirectional"))
      (node (ref "C141") (pin "2") (pinfunction "P$2_2") (pintype "bidirectional"))
      (node (ref "C142") (pin "2") (pinfunction "P$2_2") (pintype "bidirectional"))
      (node (ref "C17") (pin "P$1") (pinfunction "P$1_P$1") (pintype "bidirectional"))
      (node (ref "C18") (pin "+") (pinfunction "+_+") (pintype "bidirectional"))
      (node (ref "D10") (pin "A") (pinfunction "A_A") (pintype "bidirectional"))
      (node (ref "D9") (pin "A") (pinfunction "A_A") (pintype "bidirectional"))
      (node (ref "L9") (pin "1") (pinfunction "1_1") (pintype "bidirectional"))
      (node (ref "R15") (pin "1") (pinfunction "P$1_1") (pintype "bidirectional"))
      (node (ref "R89") (pin "2") (pinfunction "P$2_2") (pintype "bidirectional"))
      (node (ref "R91") (pin "2") (pinfunction "P$2_2") (pintype "bidirectional"))
      (node (ref "R93") (pin "2") (pinfunction "P$2_2") (pintype "bidirectional"))
      (node (ref "U20") (pin "11") (pinfunction "VBUS_DET_11") (pintype "bidirectional"))
      (node (ref "U20") (pin "19") (pinfunction "VDD33IO_19") (pintype "bidirectional"))
      (node (ref "U20") (pin "27") (pinfunction "VDD33IO_27") (pintype "bidirectional"))
      (node (ref "U20") (pin "28") (pinfunction "NTRST_28") (pintype "bidirectional"))
      (node (ref "U20") (pin "33") (pinfunction "VDD33IO_33") (pintype "bidirectional"))
      (node (ref "U20") (pin "39") (pinfunction "VDD33IO_39") (pintype "bidirectional"))
      (node (ref "U20") (pin "40") (pinfunction "TEST3_40") (pintype "bidirectional"))
      (node (ref "U20") (pin "41") (pinfunction "AUTOMDIX_EN_41") (pintype "bidirectional"))
      (node (ref "U20") (pin "46") (pinfunction "VDD33IO_46") (pintype "bidirectional"))
      (node (ref "U21") (pin "P$6") (pinfunction "VDD33_P$6") (pintype "bidirectional"))
      (node (ref "U22") (pin "P$6") (pinfunction "VDD33_P$6") (pintype "bidirectional"))
      (node (ref "U4") (pin "P$4") (pinfunction "VO_P$4") (pintype "bidirectional"))
      (node (ref "U4") (pin "P$5") (pinfunction "VO_P$5") (pintype "bidirectional"))
    )
    (net (code "2") (name "5V") (class "Default")
      (node (ref "C103") (pin "2") (pinfunction "P$2_2") (pintype "bidirectional"))
      (node (ref "C109") (pin "2") (pinfunction "P$2_2") (pintype "bidirectional"))
      (node (ref "C118") (pin "2") (pinfunction "P$2_2") (pintype "bidirectional"))
      (node (ref "C125") (pin "2") (pinfunction "P$2_2") (pintype "bidirectional"))
      (node (ref "C149") (pin "2") (pinfunction "P$2_2") (pintype "bidirectional"))
      (node (ref "C152") (pin "2") (pinfunction "P$2_2") (pintype "bidirectional"))
      (node (ref "C159") (pin "2") (pinfunction "P$2_2") (pintype "bidirectional"))
      (node (ref "C161") (pin "2") (pinfunction "P$2_2") (pintype "bidirectional"))
      (node (ref "C162") (pin "2") (pinfunction "P$2_2") (pintype "bidirectional"))
      (node (ref "C163") (pin "2") (pinfunction "P$2_2") (pintype "bidirectional"))
      (node (ref "C164") (pin "2") (pinfunction "P$2_2") (pintype "bidirectional"))
      (node (ref "C165") (pin "2") (pinfunction "P$2_2") (pintype "bidirectional"))
      (node (ref "C172") (pin "2") (pinfunction "P$2_2") (pintype "bidirectional"))
      (node (ref "C173") (pin "2") (pinfunction "P$2_2") (pintype "bidirectional"))
      (node (ref "C174") (pin "2") (pinfunction "P$2_2") (pintype "bidirectional"))
      (node (ref "C195") (pin "2") (pinfunction "P$2_2") (pintype "bidirectional"))
      (node (ref "C21") (pin "P$1") (pinfunction "P$1_P$1") (pintype "bidirectional"))
      (node (ref "C22") (pin "+") (pinfunction "+_+") (pintype "bidirectional"))
      (node (ref "C28") (pin "2") (pinfunction "P$2_2") (pintype "bidirectional"))
      (node (ref "C37") (pin "2") (pinfunction "P$2_2") (pintype "bidirectional"))
      (node (ref "C46") (pin "2") (pinfunction "P$2_2") (pintype "bidirectional"))
      (node (ref "C93") (pin "1") (pinfunction "P$1_1") (pintype "bidirectional"))
      (node (ref "C98") (pin "1") (pinfunction "P$1_1") (pintype "bidirectional"))
      (node (ref "CON15") (pin "P$9") (pinfunction "9_P$9") (pintype "bidirectional"))
      (node (ref "CON16") (pin "P$9") (pinfunction "9_P$9") (pintype "bidirectional"))
      (node (ref "CON18") (pin "4") (pinfunction "4_4") (pintype "bidirectional"))
      (node (ref "CON19") (pin "5") (pinfunction "5_5") (pintype "bidirectional"))
      (node (ref "CON20") (pin "2") (pinfunction "2_2") (pintype "bidirectional"))
      (node (ref "CON22") (pin "2") (pinfunction "2_2") (pintype "bidirectional"))
      (node (ref "CON23") (pin "2") (pinfunction "2_2") (pintype "bidirectional"))
      (node (ref "CON25") (pin "2") (pinfunction "2_2") (pintype "bidirectional"))
      (node (ref "CON26") (pin "4") (pinfunction "4_4") (pintype "bidirectional"))
      (node (ref "CON27") (pin "5") (pinfunction "5_5") (pintype "bidirectional"))
      (node (ref "CON28") (pin "2") (pinfunction "2_2") (pintype "bidirectional"))
      (node (ref "CON30") (pin "2") (pinfunction "2_2") (pintype "bidirectional"))
      (node (ref "CON31") (pin "4") (pinfunction "4_4") (pintype "bidirectional"))
      (node (ref "CON32") (pin "5") (pinfunction "5_5") (pintype "bidirectional"))
      (node (ref "CON33") (pin "2") (pinfunction "2_2") (pintype "bidirectional"))
      (node (ref "CON35") (pin "2") (pinfunction "2_2") (pintype "bidirectional"))
      (node (ref "CON37") (pin "2") (pinfunction "2_2") (pintype "bidirectional"))
      (node (ref "CON39") (pin "2") (pinfunction "2_2") (pintype "bidirectional"))
      (node (ref "CON40") (pin "6") (pinfunction "6_6") (pintype "bidirectional"))
      (node (ref "CON41") (pin "5") (pinfunction "5_5") (pintype "bidirectional"))
      (node (ref "CON42") (pin "2") (pinfunction "2_2") (pintype "bidirectional"))
      (node (ref "CON44") (pin "2") (pinfunction "2_2") (pintype "bidirectional"))
      (node (ref "CON45") (pin "6") (pinfunction "6_6") (pintype "bidirectional"))
      (node (ref "CON46") (pin "2") (pinfunction "2_2") (pintype "bidirectional"))
      (node (ref "CON48") (pin "2") (pinfunction "2_2") (pintype "bidirectional"))
      (node (ref "CON49") (pin "5") (pinfunction "5_5") (pintype "bidirectional"))
      (node (ref "CON50") (pin "2") (pinfunction "2_2") (pintype "bidirectional"))
      (node (ref "CON52") (pin "2") (pinfunction "2_2") (pintype "bidirectional"))
      (node (ref "CON53") (pin "5") (pinfunction "5_5") (pintype "bidirectional"))
      (node (ref "CON54") (pin "1") (pinfunction "VBUS_1") (pintype "bidirectional"))
      (node (ref "CON55") (pin "1") (pinfunction "VBUS_1") (pintype "bidirectional"))
      (node (ref "CON60") (pin "1") (pinfunction "VBUS_1") (pintype "bidirectional"))
      (node (ref "IC1") (pin "6") (pinfunction "AVDD_6") (pintype "passive"))
      (node (ref "IC2") (pin "44") (pinfunction "AVDD_44") (pintype "passive"))
      (node (ref "IC2") (pin "5") (pinfunction "AVDD_5") (pintype "passive"))
      (node (ref "IC2") (pin "53") (pinfunction "AVDD_53") (pintype "passive"))
      (node (ref "IC2") (pin "60") (pinfunction "AVDD_60") (pintype "passive"))
      (node (ref "IC3") (pin "2") (pinfunction "VIN_2") (pintype "passive"))
      (node (ref "IC4") (pin "2") (pinfunction "VIN_2") (pintype "passive"))
      (node (ref "J3") (pin "P$1") (pinfunction "1_P$1") (pintype "bidirectional"))
      (node (ref "J33") (pin "P$2") (pinfunction "2_P$2") (pintype "bidirectional"))
      (node (ref "J35") (pin "P$2") (pinfunction "2_P$2") (pintype "bidirectional"))
      (node (ref "J37") (pin "P$2") (pinfunction "2_P$2") (pintype "bidirectional"))
      (node (ref "J39") (pin "P$2") (pinfunction "2_P$2") (pintype "bidirectional"))
      (node (ref "J41") (pin "P$2") (pinfunction "2_P$2") (pintype "bidirectional"))
      (node (ref "J43") (pin "P$2") (pinfunction "2_P$2") (pintype "bidirectional"))
      (node (ref "J45") (pin "P$2") (pinfunction "2_P$2") (pintype "bidirectional"))
      (node (ref "R13") (pin "1") (pinfunction "P$1_1") (pintype "bidirectional"))
      (node (ref "R17") (pin "1") (pinfunction "P$1_1") (pintype "bidirectional"))
      (node (ref "R39") (pin "2") (pinfunction "P$2_2") (pintype "bidirectional"))
      (node (ref "R40") (pin "2") (pinfunction "P$2_2") (pintype "bidirectional"))
      (node (ref "R50") (pin "2") (pinfunction "P$2_2") (pintype "bidirectional"))
      (node (ref "R51") (pin "2") (pinfunction "P$2_2") (pintype "bidirectional"))
      (node (ref "U12") (pin "P$5") (pinfunction "VS_P$5") (pintype "bidirectional"))
      (node (ref "U13") (pin "P$5") (pinfunction "VS_P$5") (pintype "bidirectional"))
      (node (ref "U15") (pin "P$5") (pinfunction "VS_P$5") (pintype "bidirectional"))
      (node (ref "U16") (pin "P$5") (pinfunction "VS_P$5") (pintype "bidirectional"))
      (node (ref "U18") (pin "P$5") (pinfunction "VS_P$5") (pintype "bidirectional"))
      (node (ref "U23") (pin "4") (pinfunction "EN_4") (pintype "bidirectional"))
      (node (ref "U23") (pin "6") (pinfunction "VI_6") (pintype "bidirectional"))
      (node (ref "U24") (pin "P$5") (pinfunction "VCC_P$5") (pintype "bidirectional"))
      (node (ref "U5") (pin "P$4") (pinfunction "VO_P$4") (pintype "bidirectional"))
      (node (ref "U5") (pin "P$5") (pinfunction "VO_P$5") (pintype "bidirectional"))
      (node (ref "U7") (pin "P$5") (pinfunction "VS_P$5") (pintype "bidirectional"))
      (node (ref "U8") (pin "P$5") (pinfunction "VS_P$5") (pintype "bidirectional"))
    )
    (net (code "3") (name "12V") (class "Default")
      (node (ref "C1") (pin "1") (pinfunction "P$1_1") (pintype "bidirectional"))
      (node (ref "C16") (pin "P$1") (pinfunction "P$1_P$1") (pintype "bidirectional"))
      (node (ref "C2") (pin "+") (pinfunction "+_+") (pintype "bidirectional"))
      (node (ref "C20") (pin "P$1") (pinfunction "P$1_P$1") (pintype "bidirectional"))
      (node (ref "C24") (pin "P$1") (pinfunction "P$1_P$1") (pintype "bidirectional"))
      (node (ref "CON1") (pin "P$2") (pinfunction "2_P$2") (pintype "bidirectional"))
      (node (ref "CON36") (pin "4") (pinfunction "4_4") (pintype "bidirectional"))
      (node (ref "D1") (pin "C") (pinfunction "C_C") (pintype "bidirectional"))
      (node (ref "J1") (pin "P$2") (pinfunction "2_P$2") (pintype "bidirectional"))
      (node (ref "R1") (pin "1") (pinfunction "P$1_1") (pintype "bidirectional"))
      (node (ref "U4") (pin "P$1") (pinfunction "EN_P$1") (pintype "bidirectional"))
      (node (ref "U4") (pin "P$2") (pinfunction "VI_P$2") (pintype "bidirectional"))
      (node (ref "U5") (pin "P$1") (pinfunction "EN_P$1") (pintype "bidirectional"))
      (node (ref "U5") (pin "P$2") (pinfunction "VI_P$2") (pintype "bidirectional"))
      (node (ref "U6") (pin "P$1") (pinfunction "EN_P$1") (pintype "bidirectional"))
      (node (ref "U6") (pin "P$2") (pinfunction "VI_P$2") (pintype "bidirectional"))
    )
    (net (code "4") (name "24V") (class "Default")
      (node (ref "C11") (pin "P$1") (pinfunction "P$1_P$1") (pintype "bidirectional"))
      (node (ref "C12") (pin "+") (pinfunction "+_+") (pintype "bidirectional"))
      (node (ref "C33") (pin "P$2") (pinfunction "P$2_P$2") (pintype "bidirectional"))
      (node (ref "C34") (pin "P$2") (pinfunction "P$2_P$2") (pintype "bidirectional"))
      (node (ref "C35") (pin "P$2") (pinfunction "P$2_P$2") (pintype "bidirectional"))
      (node (ref "C36") (pin "P$2") (pinfunction "P$2_P$2") (pintype "bidirectional"))
      (node (ref "C77") (pin "P$2") (pinfunction "P$2_P$2") (pintype "bidirectional"))
      (node (ref "C78") (pin "P$2") (pinfunction "P$2_P$2") (pintype "bidirectional"))
      (node (ref "C79") (pin "P$2") (pinfunction "P$2_P$2") (pintype "bidirectional"))
      (node (ref "C80") (pin "P$2") (pinfunction "P$2_P$2") (pintype "bidirectional"))
      (node (ref "CON3") (pin "P$2") (pinfunction "2_P$2") (pintype "bidirectional"))
      (node (ref "D3") (pin "C") (pinfunction "C_C") (pintype "bidirectional"))
      (node (ref "J24") (pin "P$1") (pinfunction "1_P$1") (pintype "bidirectional"))
      (node (ref "J5") (pin "P$1") (pinfunction "1_P$1") (pintype "bidirectional"))
      (node (ref "J7") (pin "P$1") (pinfunction "1_P$1") (pintype "bidirectional"))
      (node (ref "R14") (pin "1") (pinfunction "P$1_1") (pintype "bidirectional"))
      (node (ref "R4") (pin "1") (pinfunction "P$1_1") (pintype "bidirectional"))
      (node (ref "U14") (pin "P$21") (pinfunction "VDDD_P$21") (pintype "bidirectional"))
      (node (ref "U14") (pin "P$26") (pinfunction "VDDC_P$26") (pintype "bidirectional"))
      (node (ref "U14") (pin "P$29") (pinfunction "VDDB_P$29") (pintype "bidirectional"))
      (node (ref "U14") (pin "P$34") (pinfunction "VDDA_P$34") (pintype "bidirectional"))
      (node (ref "U9") (pin "P$21") (pinfunction "VDDD_P$21") (pintype "bidirectional"))
      (node (ref "U9") (pin "P$26") (pinfunction "VDDC_P$26") (pintype "bidirectional"))
      (node (ref "U9") (pin "P$29") (pinfunction "VDDB_P$29") (pintype "bidirectional"))
      (node (ref "U9") (pin "P$34") (pinfunction "VDDA_P$34") (pintype "bidirectional"))
    )
    (net (code "5") (name "A5V") (class "Default")
      (node (ref "C14") (pin "P$1") (pinfunction "P$1_P$1") (pintype "bidirectional"))
      (node (ref "C15") (pin "+") (pinfunction "+_+") (pintype "bidirectional"))
      (node (ref "C94") (pin "1") (pinfunction "P$1_1") (pintype "bidirectional"))
      (node (ref "C99") (pin "1") (pinfunction "P$1_1") (pintype "bidirectional"))
      (node (ref "CON15") (pin "P$2") (pinfunction "2_P$2") (pintype "bidirectional"))
      (node (ref "CON16") (pin "P$2") (pinfunction "2_P$2") (pintype "bidirectional"))
      (node (ref "CON21") (pin "2") (pinfunction "2_2") (pintype "bidirectional"))
      (node (ref "CON24") (pin "2") (pinfunction "2_2") (pintype "bidirectional"))
      (node (ref "CON29") (pin "2") (pinfunction "2_2") (pintype "bidirectional"))
      (node (ref "CON34") (pin "2") (pinfunction "2_2") (pintype "bidirectional"))
      (node (ref "CON38") (pin "2") (pinfunction "2_2") (pintype "bidirectional"))
      (node (ref "CON43") (pin "2") (pinfunction "2_2") (pintype "bidirectional"))
      (node (ref "CON47") (pin "2") (pinfunction "2_2") (pintype "bidirectional"))
      (node (ref "CON51") (pin "2") (pinfunction "2_2") (pintype "bidirectional"))
      (node (ref "J26") (pin "P$1") (pinfunction "1_P$1") (pintype "bidirectional"))
      (node (ref "J27") (pin "P$1") (pinfunction "1_P$1") (pintype "bidirectional"))
      (node (ref "K1") (pin "2") (pinfunction "C_2") (pintype "bidirectional"))
      (node (ref "K2") (pin "11") (pinfunction "C_11") (pintype "bidirectional"))
      (node (ref "K3") (pin "11") (pinfunction "C_11") (pintype "bidirectional"))
      (node (ref "K4") (pin "2") (pinfunction "C_2") (pintype "bidirectional"))
      (node (ref "R12") (pin "1") (pinfunction "P$1_1") (pintype "bidirectional"))
      (node (ref "R2") (pin "1") (pinfunction "P$1_1") (pintype "bidirectional"))
      (node (ref "U3") (pin "P$4") (pinfunction "VOUT_P$4") (pintype "bidirectional"))
    )
    (net (code "6") (name "A12V") (class "Default")
      (node (ref "C13") (pin "P$1") (pinfunction "P$1_P$1") (pintype "bidirectional"))
      (node (ref "C29") (pin "P$2") (pinfunction "P$2_P$2") (pintype "bidirectional"))
      (node (ref "C30") (pin "P$2") (pinfunction "P$2_P$2") (pintype "bidirectional"))
      (node (ref "C31") (pin "P$2") (pinfunction "P$2_P$2") (pintype "bidirectional"))
      (node (ref "C32") (pin "P$2") (pinfunction "P$2_P$2") (pintype "bidirectional"))
      (node (ref "C38") (pin "P$2") (pinfunction "P$2_P$2") (pintype "bidirectional"))
      (node (ref "C39") (pin "P$2") (pinfunction "P$2_P$2") (pintype "bidirectional"))
      (node (ref "C40") (pin "P$2") (pinfunction "P$2_P$2") (pintype "bidirectional"))
      (node (ref "C41") (pin "P$2") (pinfunction "P$2_P$2") (pintype "bidirectional"))
      (node (ref "C47") (pin "P$2") (pinfunction "P$2_P$2") (pintype "bidirectional"))
      (node (ref "C48") (pin "P$2") (pinfunction "P$2_P$2") (pintype "bidirectional"))
      (node (ref "C49") (pin "P$2") (pinfunction "P$2_P$2") (pintype "bidirectional"))
      (node (ref "C5") (pin "1") (pinfunction "P$1_1") (pintype "bidirectional"))
      (node (ref "C50") (pin "P$2") (pinfunction "P$2_P$2") (pintype "bidirectional"))
      (node (ref "C6") (pin "+") (pinfunction "+_+") (pintype "bidirectional"))
      (node (ref "C81") (pin "P$2") (pinfunction "P$2_P$2") (pintype "bidirectional"))
      (node (ref "C82") (pin "P$2") (pinfunction "P$2_P$2") (pintype "bidirectional"))
      (node (ref "C83") (pin "P$2") (pinfunction "P$2_P$2") (pintype "bidirectional"))
      (node (ref "C84") (pin "P$2") (pinfunction "P$2_P$2") (pintype "bidirectional"))
      (node (ref "CON2") (pin "P$2") (pinfunction "2_P$2") (pintype "bidirectional"))
      (node (ref "D2") (pin "C") (pinfunction "C_C") (pintype "bidirectional"))
      (node (ref "J1") (pin "P$1") (pinfunction "1_P$1") (pintype "bidirectional"))
      (node (ref "J2") (pin "P$1") (pinfunction "1_P$1") (pintype "bidirectional"))
      (node (ref "J25") (pin "P$1") (pinfunction "1_P$1") (pintype "bidirectional"))
      (node (ref "J4") (pin "P$1") (pinfunction "1_P$1") (pintype "bidirectional"))
      (node (ref "J6") (pin "P$1") (pinfunction "1_P$1") (pintype "bidirectional"))
      (node (ref "R3") (pin "1") (pinfunction "P$1_1") (pintype "bidirectional"))
      (node (ref "U10") (pin "P$1") (pinfunction "VDD_P$1") (pintype "bidirectional"))
      (node (ref "U10") (pin "P$17") (pinfunction "VDD_P$17") (pintype "bidirectional"))
      (node (ref "U10") (pin "P$18") (pinfunction "VDD_P$18") (pintype "bidirectional"))
      (node (ref "U10") (pin "P$19") (pinfunction "VDD_P$19") (pintype "bidirectional"))
      (node (ref "U10") (pin "P$36") (pinfunction "VDD_P$36") (pintype "bidirectional"))
      (node (ref "U11") (pin "P$1") (pinfunction "VDD_P$1") (pintype "bidirectional"))
      (node (ref "U11") (pin "P$17") (pinfunction "VDD_P$17") (pintype "bidirectional"))
      (node (ref "U11") (pin "P$18") (pinfunction "VDD_P$18") (pintype "bidirectional"))
      (node (ref "U11") (pin "P$19") (pinfunction "VDD_P$19") (pintype "bidirectional"))
      (node (ref "U11") (pin "P$36") (pinfunction "VDD_P$36") (pintype "bidirectional"))
      (node (ref "U14") (pin "P$1") (pinfunction "VDD_P$1") (pintype "bidirectional"))
      (node (ref "U14") (pin "P$17") (pinfunction "VDD_P$17") (pintype "bidirectional"))
      (node (ref "U14") (pin "P$18") (pinfunction "VDD_P$18") (pintype "bidirectional"))
      (node (ref "U14") (pin "P$19") (pinfunction "VDD_P$19") (pintype "bidirectional"))
      (node (ref "U14") (pin "P$36") (pinfunction "VDD_P$36") (pintype "bidirectional"))
      (node (ref "U3") (pin "P$2") (pinfunction "VIN_P$2") (pintype "bidirectional"))
      (node (ref "U9") (pin "P$1") (pinfunction "VDD_P$1") (pintype "bidirectional"))
      (node (ref "U9") (pin "P$17") (pinfunction "VDD_P$17") (pintype "bidirectional"))
      (node (ref "U9") (pin "P$18") (pinfunction "VDD_P$18") (pintype "bidirectional"))
      (node (ref "U9") (pin "P$19") (pinfunction "VDD_P$19") (pintype "bidirectional"))
      (node (ref "U9") (pin "P$36") (pinfunction "VDD_P$36") (pintype "bidirectional"))
    )
    (net (code "7") (name "AD0_CLK") (class "Default")
      (node (ref "CON57") (pin "6") (pinfunction "6_6") (pintype "bidirectional"))
      (node (ref "IC2") (pin "27") (pinfunction "CLK_27") (pintype "passive"))
    )
    (net (code "8") (name "AD0_DRDY") (class "Default")
      (node (ref "CON57") (pin "10") (pinfunction "10_10") (pintype "bidirectional"))
      (node (ref "IC2") (pin "29") (pinfunction "DRDY/_29") (pintype "passive"))
    )
    (net (code "9") (name "AD0_MISO") (class "Default")
      (node (ref "CON57") (pin "2") (pinfunction "2_2") (pintype "bidirectional"))
      (node (ref "IC2") (pin "20") (pinfunction "DOUT1_20") (pintype "passive"))
    )
    (net (code "10") (name "AD0_SCLK") (class "Default")
      (node (ref "CON57") (pin "8") (pinfunction "8_8") (pintype "bidirectional"))
      (node (ref "IC2") (pin "28") (pinfunction "SCLK_28") (pintype "passive"))
    )
    (net (code "11") (name "AD0_SYNC") (class "Default")
      (node (ref "CON57") (pin "4") (pinfunction "4_4") (pintype "bidirectional"))
      (node (ref "IC2") (pin "11") (pinfunction "SYNC_11") (pintype "passive"))
    )
    (net (code "12") (name "AD0_VREF") (class "Default")
      (node (ref "C171") (pin "2") (pinfunction "P$2_2") (pintype "bidirectional"))
      (node (ref "C180") (pin "P$1") (pinfunction "P$1_P$1") (pintype "bidirectional"))
      (node (ref "C57") (pin "2") (pinfunction "P$2_2") (pintype "bidirectional"))
      (node (ref "C59") (pin "2") (pinfunction "P$2_2") (pintype "bidirectional"))
      (node (ref "C72") (pin "2") (pinfunction "P$2_2") (pintype "bidirectional"))
      (node (ref "CON16") (pin "P$10") (pinfunction "10_P$10") (pintype "bidirectional"))
      (node (ref "IC2") (pin "2") (pinfunction "AINN2_2") (pintype "passive"))
      (node (ref "IC2") (pin "46") (pinfunction "AINN8_46") (pintype "passive"))
      (node (ref "IC2") (pin "48") (pinfunction "AINN7_48") (pintype "passive"))
      (node (ref "IC2") (pin "50") (pinfunction "AINN6_50") (pintype "passive"))
      (node (ref "IC2") (pin "52") (pinfunction "AINN5_52") (pintype "passive"))
      (node (ref "IC2") (pin "56") (pinfunction "VREFP_56") (pintype "passive"))
      (node (ref "IC2") (pin "62") (pinfunction "AINN4_62") (pintype "passive"))
      (node (ref "IC2") (pin "64") (pinfunction "AINN3_64") (pintype "passive"))
      (node (ref "J30") (pin "P$1") (pinfunction "1_P$1") (pintype "bidirectional"))
      (node (ref "J32") (pin "P$2") (pinfunction "2_P$2") (pintype "bidirectional"))
      (node (ref "U12") (pin "P$6") (pinfunction "REF2_P$6") (pintype "bidirectional"))
      (node (ref "U12") (pin "P$7") (pinfunction "REF1_P$7") (pintype "bidirectional"))
      (node (ref "U13") (pin "P$6") (pinfunction "REF2_P$6") (pintype "bidirectional"))
      (node (ref "U13") (pin "P$7") (pinfunction "REF1_P$7") (pintype "bidirectional"))
      (node (ref "U15") (pin "P$6") (pinfunction "REF2_P$6") (pintype "bidirectional"))
      (node (ref "U15") (pin "P$7") (pinfunction "REF1_P$7") (pintype "bidirectional"))
      (node (ref "U7") (pin "P$6") (pinfunction "REF2_P$6") (pintype "bidirectional"))
      (node (ref "U7") (pin "P$7") (pinfunction "REF1_P$7") (pintype "bidirectional"))
      (node (ref "U8") (pin "P$6") (pinfunction "REF2_P$6") (pintype "bidirectional"))
      (node (ref "U8") (pin "P$7") (pinfunction "REF1_P$7") (pintype "bidirectional"))
    )
    (net (code "13") (name "AD0_VREF*") (class "Default")
      (node (ref "C92") (pin "2") (pinfunction "P$2_2") (pintype "bidirectional"))
      (node (ref "C97") (pin "2") (pinfunction "P$2_2") (pintype "bidirectional"))
      (node (ref "CON15") (pin "P$10") (pinfunction "10_P$10") (pintype "bidirectional"))
      (node (ref "U16") (pin "P$6") (pinfunction "REF2_P$6") (pintype "bidirectional"))
      (node (ref "U16") (pin "P$7") (pinfunction "REF1_P$7") (pintype "bidirectional"))
      (node (ref "U18") (pin "P$6") (pinfunction "REF2_P$6") (pintype "bidirectional"))
      (node (ref "U18") (pin "P$7") (pinfunction "REF1_P$7") (pintype "bidirectional"))
    )
    (net (code "14") (name "AD1_DRDY") (class "Default")
      (node (ref "IC1") (pin "25") (pinfunction "DRDY_25") (pintype "passive"))
      (node (ref "U29") (pin "D11") (pinfunction "D11_D11") (pintype "bidirectional"))
    )
    (net (code "15") (name "AD1_M") (class "Default")
      (node (ref "IC1") (pin "44") (pinfunction "MUXOUTP_44") (pintype "passive"))
      (node (ref "R97") (pin "1") (pinfunction "P$1_1") (pintype "bidirectional"))
    )
    (net (code "16") (name "AD1_MISO") (class "Default")
      (node (ref "IC1") (pin "24") (pinfunction "DOUT_24") (pintype "passive"))
      (node (ref "U29") (pin "D12") (pinfunction "D12_D12") (pintype "bidirectional"))
    )
    (net (code "17") (name "AD1_MOSI") (class "Default")
      (node (ref "IC1") (pin "23") (pinfunction "DIN_23") (pintype "passive"))
      (node (ref "U29") (pin "D13") (pinfunction "D13_D13") (pintype "bidirectional"))
    )
    (net (code "18") (name "AD1_P") (class "Default")
      (node (ref "C178") (pin "2") (pinfunction "P$2_2") (pintype "bidirectional"))
      (node (ref "IC1") (pin "42") (pinfunction "ADCINP_42") (pintype "passive"))
      (node (ref "R98") (pin "2") (pinfunction "P$2_2") (pintype "bidirectional"))
      (node (ref "U24") (pin "P$4") (pinfunction "OUT_P$4") (pintype "bidirectional"))
    )
    (net (code "19") (name "AD1_RST") (class "Default")
      (node (ref "IC1") (pin "11") (pinfunction "RESET_11") (pintype "passive"))
      (node (ref "U29") (pin "SCL") (pinfunction "SCL_SCL") (pintype "bidirectional"))
    )
    (net (code "20") (name "AD1_SCLK") (class "Default")
      (node (ref "IC1") (pin "22") (pinfunction "SCLK_22") (pintype "passive"))
      (node (ref "U29") (pin "SDA") (pinfunction "SDA_SDA") (pintype "bidirectional"))
    )
    (net (code "21") (name "AD1_SS") (class "Default")
      (node (ref "IC1") (pin "27") (pinfunction "CS_27") (pintype "passive"))
      (node (ref "U29") (pin "D10") (pinfunction "D10_D10") (pintype "bidirectional"))
    )
    (net (code "22") (name "AD1_V") (class "Default")
      (node (ref "C176") (pin "P$1") (pinfunction "P$1_P$1") (pintype "bidirectional"))
      (node (ref "C177") (pin "2") (pinfunction "P$2_2") (pintype "bidirectional"))
      (node (ref "IC1") (pin "31") (pinfunction "VREFP_31") (pintype "passive"))
      (node (ref "J31") (pin "P$2") (pinfunction "2_P$2") (pintype "bidirectional"))
    )
    (net (code "23") (name "ADC_IN0") (class "Default")
      (node (ref "J47") (pin "2") (pinfunction "2_2") (pintype "passive"))
    )
    (net (code "24") (name "ADC_IN1") (class "Default")
      (node (ref "J47") (pin "3") (pinfunction "3_3") (pintype "passive"))
    )
    (net (code "25") (name "ADC_IN2") (class "Default")
      (node (ref "J47") (pin "4") (pinfunction "4_4") (pintype "passive"))
    )
    (net (code "26") (name "ADC_IN3") (class "Default")
      (node (ref "J47") (pin "5") (pinfunction "5_5") (pintype "passive"))
    )
    (net (code "27") (name "ADC_IN4") (class "Default")
      (node (ref "J47") (pin "6") (pinfunction "6_6") (pintype "passive"))
    )
    (net (code "28") (name "ADC_IN5") (class "Default")
      (node (ref "J47") (pin "7") (pinfunction "7_7") (pintype "passive"))
    )
    (net (code "29") (name "ADC_IN6") (class "Default")
      (node (ref "J47") (pin "8") (pinfunction "8_8") (pintype "passive"))
    )
    (net (code "30") (name "ADC_IN7") (class "Default")
      (node (ref "J47") (pin "9") (pinfunction "9_9") (pintype "passive"))
    )
    (net (code "31") (name "ADC_VCC") (class "Default")
      (node (ref "J47") (pin "1") (pinfunction "1_1") (pintype "passive"))
    )
    (net (code "32") (name "AN0") (class "Default")
      (node (ref "C100") (pin "2") (pinfunction "P$2_2") (pintype "bidirectional"))
      (node (ref "IC1") (pin "45") (pinfunction "AIN7_45") (pintype "passive"))
      (node (ref "R41") (pin "2") (pinfunction "P$2_2") (pintype "bidirectional"))
      (node (ref "R43") (pin "1") (pinfunction "P$1_1") (pintype "bidirectional"))
    )
    (net (code "33") (name "AN1") (class "Default")
      (node (ref "C106") (pin "2") (pinfunction "P$2_2") (pintype "bidirectional"))
      (node (ref "IC1") (pin "46") (pinfunction "AIN6_46") (pintype "passive"))
      (node (ref "R46") (pin "2") (pinfunction "P$2_2") (pintype "bidirectional"))
      (node (ref "R48") (pin "1") (pinfunction "P$1_1") (pintype "bidirectional"))
    )
    (net (code "34") (name "AN2") (class "Default")
      (node (ref "C112") (pin "2") (pinfunction "P$2_2") (pintype "bidirectional"))
      (node (ref "IC1") (pin "47") (pinfunction "AIN5_47") (pintype "passive"))
      (node (ref "R53") (pin "2") (pinfunction "P$2_2") (pintype "bidirectional"))
      (node (ref "R55") (pin "1") (pinfunction "P$1_1") (pintype "bidirectional"))
    )
    (net (code "35") (name "AN3") (class "Default")
      (node (ref "C115") (pin "2") (pinfunction "P$2_2") (pintype "bidirectional"))
      (node (ref "IC1") (pin "48") (pinfunction "AIN4_48") (pintype "passive"))
      (node (ref "R59") (pin "2") (pinfunction "P$2_2") (pintype "bidirectional"))
      (node (ref "R63") (pin "1") (pinfunction "P$1_1") (pintype "bidirectional"))
    )
    (net (code "36") (name "AN4") (class "Default")
      (node (ref "C122") (pin "2") (pinfunction "P$2_2") (pintype "bidirectional"))
      (node (ref "IC1") (pin "1") (pinfunction "AIN3_1") (pintype "passive"))
      (node (ref "R66") (pin "2") (pinfunction "P$2_2") (pintype "bidirectional"))
      (node (ref "R68") (pin "1") (pinfunction "P$1_1") (pintype "bidirectional"))
    )
    (net (code "37") (name "AN5") (class "Default")
      (node (ref "C129") (pin "2") (pinfunction "P$2_2") (pintype "bidirectional"))
      (node (ref "IC1") (pin "2") (pinfunction "AIN2_2") (pintype "passive"))
      (node (ref "R74") (pin "2") (pinfunction "P$2_2") (pintype "bidirectional"))
      (node (ref "R76") (pin "1") (pinfunction "P$1_1") (pintype "bidirectional"))
    )
    (net (code "38") (name "AN6") (class "Default")
      (node (ref "C132") (pin "2") (pinfunction "P$2_2") (pintype "bidirectional"))
      (node (ref "IC1") (pin "3") (pinfunction "AIN1_3") (pintype "passive"))
      (node (ref "R79") (pin "2") (pinfunction "P$2_2") (pintype "bidirectional"))
      (node (ref "R81") (pin "1") (pinfunction "P$1_1") (pintype "bidirectional"))
    )
    (net (code "39") (name "AN7") (class "Default")
      (node (ref "C135") (pin "2") (pinfunction "P$2_2") (pintype "bidirectional"))
      (node (ref "IC1") (pin "4") (pinfunction "AIN0_4") (pintype "passive"))
      (node (ref "R84") (pin "2") (pinfunction "P$2_2") (pintype "bidirectional"))
      (node (ref "R86") (pin "1") (pinfunction "P$1_1") (pintype "bidirectional"))
    )
    (net (code "40") (name "ARDUINO_A0") (class "Default")
      (node (ref "U29") (pin "A0") (pinfunction "A0_A0") (pintype "bidirectional"))
    )
    (net (code "41") (name "ARDUINO_A1") (class "Default")
      (node (ref "U29") (pin "A1") (pinfunction "A1_A1") (pintype "bidirectional"))
    )
    (net (code "42") (name "ARDUINO_A2") (class "Default")
      (node (ref "U29") (pin "A2") (pinfunction "A2_A2") (pintype "bidirectional"))
    )
    (net (code "43") (name "ARDUINO_A3") (class "Default")
      (node (ref "U29") (pin "A3") (pinfunction "A3_A3") (pintype "bidirectional"))
    )
    (net (code "44") (name "ARDUINO_A4") (class "Default")
      (node (ref "U29") (pin "A4") (pinfunction "A4/SDA_A4") (pintype "bidirectional"))
    )
    (net (code "45") (name "ARDUINO_A5") (class "Default")
      (node (ref "U29") (pin "A5") (pinfunction "A5/SCL_A5") (pintype "bidirectional"))
    )
    (net (code "46") (name "BALISE") (class "Default")
      (node (ref "U29") (pin "D3") (pinfunction "D3_D3") (pintype "bidirectional"))
      (node (ref "U31") (pin "P$9") (pinfunction "A8_P$9") (pintype "bidirectional"))
    )
    (net (code "47") (name "BALISE°") (class "Default")
      (node (ref "CON36") (pin "5") (pinfunction "5_5") (pintype "bidirectional"))
      (node (ref "U31") (pin "P$12") (pinfunction "B8_P$12") (pintype "bidirectional"))
    )
    (net (code "48") (name "BUZZER") (class "Default")
      (node (ref "U29") (pin "D8") (pinfunction "D8_D8") (pintype "bidirectional"))
      (node (ref "U31") (pin "P$3") (pinfunction "A2_P$3") (pintype "bidirectional"))
    )
    (net (code "49") (name "BUZZER°") (class "Default")
      (node (ref "T1") (pin "P$1") (pinfunction "G_P$1") (pintype "bidirectional"))
      (node (ref "U31") (pin "P$18") (pinfunction "B2_P$18") (pintype "bidirectional"))
    )
    (net (code "50") (name "D3V3") (class "Default")
      (node (ref "C160") (pin "2") (pinfunction "P$2_2") (pintype "bidirectional"))
      (node (ref "C167") (pin "2") (pinfunction "P$2_2") (pintype "bidirectional"))
      (node (ref "C181") (pin "2") (pinfunction "P$2_2") (pintype "bidirectional"))
      (node (ref "C183") (pin "2") (pinfunction "P$2_2") (pintype "bidirectional"))
      (node (ref "C185") (pin "2") (pinfunction "P$2_2") (pintype "bidirectional"))
      (node (ref "C187") (pin "2") (pinfunction "P$2_2") (pintype "bidirectional"))
      (node (ref "C189") (pin "2") (pinfunction "P$2_2") (pintype "bidirectional"))
      (node (ref "C191") (pin "2") (pinfunction "P$2_2") (pintype "bidirectional"))
      (node (ref "C193") (pin "2") (pinfunction "P$2_2") (pintype "bidirectional"))
      (node (ref "C219") (pin "2") (pinfunction "P$2_2") (pintype "bidirectional"))
      (node (ref "C3") (pin "1") (pinfunction "P$1_1") (pintype "bidirectional"))
      (node (ref "CON57") (pin "29") (pinfunction "29_29") (pintype "bidirectional"))
      (node (ref "CON58") (pin "29") (pinfunction "29_29") (pintype "bidirectional"))
      (node (ref "IC1") (pin "10") (pinfunction "PWDN_10") (pintype "passive"))
      (node (ref "IC1") (pin "26") (pinfunction "START_26") (pintype "passive"))
      (node (ref "IC1") (pin "28") (pinfunction "DVDD_28") (pintype "passive"))
      (node (ref "IC2") (pin "10") (pinfunction "CLKDIV_10") (pintype "passive"))
      (node (ref "IC2") (pin "22") (pinfunction "IOVDD_22") (pintype "passive"))
      (node (ref "IC2") (pin "23") (pinfunction "IOVDD_23") (pintype "passive"))
      (node (ref "IC2") (pin "32") (pinfunction "FORMAT0_32") (pintype "passive"))
      (node (ref "IC2") (pin "35") (pinfunction "PWDN8_35") (pintype "passive"))
      (node (ref "IC2") (pin "36") (pinfunction "PWDN7_36") (pintype "passive"))
      (node (ref "IC2") (pin "37") (pinfunction "PWDN6_37") (pintype "passive"))
      (node (ref "IC2") (pin "38") (pinfunction "PWDN5_38") (pintype "passive"))
      (node (ref "IC2") (pin "39") (pinfunction "PWDN4_39") (pintype "passive"))
      (node (ref "IC2") (pin "40") (pinfunction "PWDN3_40") (pintype "passive"))
      (node (ref "IC2") (pin "41") (pinfunction "PWDN2_41") (pintype "passive"))
      (node (ref "IC2") (pin "42") (pinfunction "PWDN1_42") (pintype "passive"))
      (node (ref "J28") (pin "P$2") (pinfunction "2_P$2") (pintype "bidirectional"))
      (node (ref "J34") (pin "P$2") (pinfunction "2_P$2") (pintype "bidirectional"))
      (node (ref "J36") (pin "P$2") (pinfunction "2_P$2") (pintype "bidirectional"))
      (node (ref "J38") (pin "P$2") (pinfunction "2_P$2") (pintype "bidirectional"))
      (node (ref "J40") (pin "P$2") (pinfunction "2_P$2") (pintype "bidirectional"))
      (node (ref "J42") (pin "P$2") (pinfunction "2_P$2") (pintype "bidirectional"))
      (node (ref "J44") (pin "P$2") (pinfunction "2_P$2") (pintype "bidirectional"))
      (node (ref "J46") (pin "P$2") (pinfunction "2_P$2") (pintype "bidirectional"))
      (node (ref "R100") (pin "2") (pinfunction "P$2_2") (pintype "bidirectional"))
      (node (ref "R101") (pin "2") (pinfunction "P$2_2") (pintype "bidirectional"))
      (node (ref "R102") (pin "2") (pinfunction "P$2_2") (pintype "bidirectional"))
      (node (ref "R103") (pin "2") (pinfunction "P$2_2") (pintype "bidirectional"))
      (node (ref "R104") (pin "2") (pinfunction "P$2_2") (pintype "bidirectional"))
      (node (ref "R105") (pin "2") (pinfunction "P$2_2") (pintype "bidirectional"))
      (node (ref "R106") (pin "2") (pinfunction "P$2_2") (pintype "bidirectional"))
      (node (ref "R99") (pin "2") (pinfunction "P$2_2") (pintype "bidirectional"))
      (node (ref "U1") (pin "16") (pinfunction "VCC_16") (pintype "bidirectional"))
      (node (ref "U25") (pin "P$10") (pinfunction "OE_P$10") (pintype "bidirectional"))
      (node (ref "U25") (pin "P$2") (pinfunction "VA_P$2") (pintype "bidirectional"))
      (node (ref "U26") (pin "P$10") (pinfunction "OE_P$10") (pintype "bidirectional"))
      (node (ref "U26") (pin "P$2") (pinfunction "VA_P$2") (pintype "bidirectional"))
      (node (ref "U27") (pin "P$10") (pinfunction "OE_P$10") (pintype "bidirectional"))
      (node (ref "U27") (pin "P$2") (pinfunction "VA_P$2") (pintype "bidirectional"))
      (node (ref "U28") (pin "P$10") (pinfunction "OE_P$10") (pintype "bidirectional"))
      (node (ref "U28") (pin "P$2") (pinfunction "VA_P$2") (pintype "bidirectional"))
      (node (ref "U30") (pin "P$10") (pinfunction "OE_P$10") (pintype "bidirectional"))
      (node (ref "U30") (pin "P$2") (pinfunction "VA_P$2") (pintype "bidirectional"))
      (node (ref "U31") (pin "P$10") (pinfunction "OE_P$10") (pintype "bidirectional"))
      (node (ref "U31") (pin "P$2") (pinfunction "VA_P$2") (pintype "bidirectional"))
      (node (ref "U32") (pin "P$10") (pinfunction "OE_P$10") (pintype "bidirectional"))
      (node (ref "U32") (pin "P$2") (pinfunction "VA_P$2") (pintype "bidirectional"))
      (node (ref "U38") (pin "4") (pinfunction "EN_4") (pintype "bidirectional"))
      (node (ref "U38") (pin "6") (pinfunction "VI_6") (pintype "bidirectional"))
    )
    (net (code "51") (name "DM2") (class "Default")
      (node (ref "CON54") (pin "2") (pinfunction "D-_2") (pintype "bidirectional"))
      (node (ref "U20") (pin "3") (pinfunction "USBDM3_3") (pintype "bidirectional"))
    )
    (net (code "52") (name "DM3") (class "Default")
      (node (ref "CON55") (pin "2") (pinfunction "D-_2") (pintype "bidirectional"))
      (node (ref "U20") (pin "6") (pinfunction "USBDM4_6") (pintype "bidirectional"))
    )
    (net (code "53") (name "DP2") (class "Default")
      (node (ref "CON54") (pin "3") (pinfunction "D+_3") (pintype "bidirectional"))
      (node (ref "U20") (pin "4") (pinfunction "USBDP3_4") (pintype "bidirectional"))
    )
    (net (code "54") (name "DP3") (class "Default")
      (node (ref "CON55") (pin "3") (pinfunction "D+_3") (pintype "bidirectional"))
      (node (ref "U20") (pin "7") (pinfunction "USBDP4_7") (pintype "bidirectional"))
    )
    (net (code "55") (name "ESC0_CS") (class "Default")
      (node (ref "C96") (pin "2") (pinfunction "P$2_2") (pintype "bidirectional"))
      (node (ref "CON16") (pin "P$7") (pinfunction "7_P$7") (pintype "bidirectional"))
      (node (ref "IC2") (pin "63") (pinfunction "AINP3_63") (pintype "passive"))
    )
    (net (code "56") (name "ESC0_CS*") (class "Default")
      (node (ref "CON15") (pin "P$7") (pinfunction "7_P$7") (pintype "bidirectional"))
      (node (ref "R35") (pin "2") (pinfunction "P$2_2") (pintype "bidirectional"))
    )
    (net (code "57") (name "ESC0_DIR") (class "Default")
      (node (ref "U29") (pin "D5") (pinfunction "D5_D5") (pintype "bidirectional"))
      (node (ref "U31") (pin "P$6") (pinfunction "A5_P$6") (pintype "bidirectional"))
    )
    (net (code "58") (name "ESC0_DIR°") (class "Default")
      (node (ref "CON16") (pin "P$3") (pinfunction "3_P$3") (pintype "bidirectional"))
      (node (ref "U31") (pin "P$15") (pinfunction "B5_P$15") (pintype "bidirectional"))
    )
    (net (code "59") (name "ESC0_DIR°*") (class "Default")
      (node (ref "CON15") (pin "P$3") (pinfunction "3_P$3") (pintype "bidirectional"))
      (node (ref "T2") (pin "P$1") (pinfunction "G_P$1") (pintype "bidirectional"))
    )
    (net (code "60") (name "ESC0_PWM") (class "Default")
      (node (ref "U29") (pin "D4") (pinfunction "D4_D4") (pintype "bidirectional"))
      (node (ref "U31") (pin "P$7") (pinfunction "A6_P$7") (pintype "bidirectional"))
    )
    (net (code "61") (name "ESC0_PWM°") (class "Default")
      (node (ref "CON16") (pin "P$5") (pinfunction "5_P$5") (pintype "bidirectional"))
      (node (ref "U31") (pin "P$14") (pinfunction "B6_P$14") (pintype "bidirectional"))
    )
    (net (code "62") (name "ESC0_PWM°*") (class "Default")
      (node (ref "CON15") (pin "P$5") (pinfunction "5_P$5") (pintype "bidirectional"))
      (node (ref "U17") (pin "PWM") (pinfunction "PWM_PWM") (pintype "bidirectional"))
    )
    (net (code "63") (name "ESC1_CS") (class "Default")
      (node (ref "C95") (pin "2") (pinfunction "P$2_2") (pintype "bidirectional"))
      (node (ref "CON16") (pin "P$8") (pinfunction "8_P$8") (pintype "bidirectional"))
      (node (ref "IC2") (pin "1") (pinfunction "AINP2_1") (pintype "passive"))
    )
    (net (code "64") (name "ESC1_CS*") (class "Default")
      (node (ref "CON15") (pin "P$8") (pinfunction "8_P$8") (pintype "bidirectional"))
      (node (ref "R37") (pin "2") (pinfunction "P$2_2") (pintype "bidirectional"))
    )
    (net (code "65") (name "ESC1_DIR") (class "Default")
      (node (ref "U29") (pin "D6") (pinfunction "D6_D6") (pintype "bidirectional"))
      (node (ref "U31") (pin "P$5") (pinfunction "A4_P$5") (pintype "bidirectional"))
    )
    (net (code "66") (name "ESC1_DIR°") (class "Default")
      (node (ref "CON16") (pin "P$4") (pinfunction "4_P$4") (pintype "bidirectional"))
      (node (ref "U31") (pin "P$16") (pinfunction "B4_P$16") (pintype "bidirectional"))
    )
    (net (code "67") (name "ESC1_DIR°*") (class "Default")
      (node (ref "CON15") (pin "P$4") (pinfunction "4_P$4") (pintype "bidirectional"))
      (node (ref "T3") (pin "P$1") (pinfunction "G_P$1") (pintype "bidirectional"))
    )
    (net (code "68") (name "ESC1_PWM") (class "Default")
      (node (ref "U29") (pin "D7") (pinfunction "D7_D7") (pintype "bidirectional"))
      (node (ref "U31") (pin "P$4") (pinfunction "A3_P$4") (pintype "bidirectional"))
    )
    (net (code "69") (name "ESC1_PWM°") (class "Default")
      (node (ref "CON16") (pin "P$1") (pinfunction "1_P$1") (pintype "bidirectional"))
      (node (ref "U31") (pin "P$17") (pinfunction "B3_P$17") (pintype "bidirectional"))
    )
    (net (code "70") (name "ESC1_PWM°*") (class "Default")
      (node (ref "CON15") (pin "P$1") (pinfunction "1_P$1") (pintype "bidirectional"))
      (node (ref "U19") (pin "PWM") (pinfunction "PWM_PWM") (pintype "bidirectional"))
    )
    (net (code "71") (name "ESC_PWR") (class "Default")
      (node (ref "C91") (pin "+") (pinfunction "+_+") (pintype "bidirectional"))
      (node (ref "J24") (pin "P$2") (pinfunction "2_P$2") (pintype "bidirectional"))
      (node (ref "J25") (pin "P$2") (pinfunction "2_P$2") (pintype "bidirectional"))
      (node (ref "R36") (pin "P$2") (pinfunction "P$2_P$2") (pintype "bidirectional"))
      (node (ref "R38") (pin "P$2") (pinfunction "P$2_P$2") (pintype "bidirectional"))
      (node (ref "U16") (pin "P$3") (pinfunction "IN-_P$3") (pintype "bidirectional"))
      (node (ref "U18") (pin "P$2") (pinfunction "IN+_P$2") (pintype "bidirectional"))
    )
    (net (code "72") (name "GND") (class "Default")
      (node (ref "C1") (pin "2") (pinfunction "P$2_2") (pintype "bidirectional"))
      (node (ref "C10") (pin "2") (pinfunction "P$2_2") (pintype "bidirectional"))
      (node (ref "C100") (pin "1") (pinfunction "P$1_1") (pintype "bidirectional"))
      (node (ref "C101") (pin "1") (pinfunction "P$1_1") (pintype "bidirectional"))
      (node (ref "C102") (pin "1") (pinfunction "P$1_1") (pintype "bidirectional"))
      (node (ref "C103") (pin "1") (pinfunction "P$1_1") (pintype "bidirectional"))
      (node (ref "C104") (pin "1") (pinfunction "P$1_1") (pintype "bidirectional"))
      (node (ref "C105") (pin "1") (pinfunction "P$1_1") (pintype "bidirectional"))
      (node (ref "C106") (pin "1") (pinfunction "P$1_1") (pintype "bidirectional"))
      (node (ref "C107") (pin "1") (pinfunction "P$1_1") (pintype "bidirectional"))
      (node (ref "C108") (pin "1") (pinfunction "P$1_1") (pintype "bidirectional"))
      (node (ref "C109") (pin "1") (pinfunction "P$1_1") (pintype "bidirectional"))
      (node (ref "C11") (pin "P$2") (pinfunction "P$2_P$2") (pintype "bidirectional"))
      (node (ref "C110") (pin "1") (pinfunction "P$1_1") (pintype "bidirectional"))
      (node (ref "C111") (pin "1") (pinfunction "P$1_1") (pintype "bidirectional"))
      (node (ref "C112") (pin "1") (pinfunction "P$1_1") (pintype "bidirectional"))
      (node (ref "C113") (pin "1") (pinfunction "P$1_1") (pintype "bidirectional"))
      (node (ref "C114") (pin "1") (pinfunction "P$1_1") (pintype "bidirectional"))
      (node (ref "C115") (pin "1") (pinfunction "P$1_1") (pintype "bidirectional"))
      (node (ref "C116") (pin "1") (pinfunction "P$1_1") (pintype "bidirectional"))
      (node (ref "C117") (pin "1") (pinfunction "P$1_1") (pintype "bidirectional"))
      (node (ref "C118") (pin "1") (pinfunction "P$1_1") (pintype "bidirectional"))
      (node (ref "C119") (pin "1") (pinfunction "P$1_1") (pintype "bidirectional"))
      (node (ref "C12") (pin "-") (pinfunction "-_-") (pintype "bidirectional"))
      (node (ref "C120") (pin "1") (pinfunction "P$1_1") (pintype "bidirectional"))
      (node (ref "C121") (pin "1") (pinfunction "P$1_1") (pintype "bidirectional"))
      (node (ref "C122") (pin "1") (pinfunction "P$1_1") (pintype "bidirectional"))
      (node (ref "C123") (pin "1") (pinfunction "P$1_1") (pintype "bidirectional"))
      (node (ref "C124") (pin "1") (pinfunction "P$1_1") (pintype "bidirectional"))
      (node (ref "C125") (pin "1") (pinfunction "P$1_1") (pintype "bidirectional"))
      (node (ref "C126") (pin "1") (pinfunction "P$1_1") (pintype "bidirectional"))
      (node (ref "C127") (pin "1") (pinfunction "P$1_1") (pintype "bidirectional"))
      (node (ref "C128") (pin "1") (pinfunction "P$1_1") (pintype "bidirectional"))
      (node (ref "C129") (pin "1") (pinfunction "P$1_1") (pintype "bidirectional"))
      (node (ref "C13") (pin "P$2") (pinfunction "P$2_P$2") (pintype "bidirectional"))
      (node (ref "C130") (pin "1") (pinfunction "P$1_1") (pintype "bidirectional"))
      (node (ref "C131") (pin "1") (pinfunction "P$1_1") (pintype "bidirectional"))
      (node (ref "C132") (pin "1") (pinfunction "P$1_1") (pintype "bidirectional"))
      (node (ref "C133") (pin "1") (pinfunction "P$1_1") (pintype "bidirectional"))
      (node (ref "C134") (pin "1") (pinfunction "P$1_1") (pintype "bidirectional"))
      (node (ref "C135") (pin "1") (pinfunction "P$1_1") (pintype "bidirectional"))
      (node (ref "C136") (pin "1") (pinfunction "P$1_1") (pintype "bidirectional"))
      (node (ref "C137") (pin "1") (pinfunction "P$1_1") (pintype "bidirectional"))
      (node (ref "C138") (pin "1") (pinfunction "P$1_1") (pintype "bidirectional"))
      (node (ref "C139") (pin "1") (pinfunction "P$1_1") (pintype "bidirectional"))
      (node (ref "C14") (pin "P$2") (pinfunction "P$2_P$2") (pintype "bidirectional"))
      (node (ref "C140") (pin "1") (pinfunction "P$1_1") (pintype "bidirectional"))
      (node (ref "C141") (pin "1") (pinfunction "P$1_1") (pintype "bidirectional"))
      (node (ref "C142") (pin "1") (pinfunction "P$1_1") (pintype "bidirectional"))
      (node (ref "C143") (pin "1") (pinfunction "P$1_1") (pintype "bidirectional"))
      (node (ref "C144") (pin "1") (pinfunction "P$1_1") (pintype "bidirectional"))
      (node (ref "C145") (pin "1") (pinfunction "P$1_1") (pintype "bidirectional"))
      (node (ref "C146") (pin "1") (pinfunction "P$1_1") (pintype "bidirectional"))
      (node (ref "C147") (pin "1") (pinfunction "P$1_1") (pintype "bidirectional"))
      (node (ref "C148") (pin "P$1") (pinfunction "P$1_P$1") (pintype "bidirectional"))
      (node (ref "C149") (pin "1") (pinfunction "P$1_1") (pintype "bidirectional"))
      (node (ref "C15") (pin "-") (pinfunction "-_-") (pintype "bidirectional"))
      (node (ref "C150") (pin "1") (pinfunction "P$1_1") (pintype "bidirectional"))
      (node (ref "C151") (pin "1") (pinfunction "P$1_1") (pintype "bidirectional"))
      (node (ref "C152") (pin "1") (pinfunction "P$1_1") (pintype "bidirectional"))
      (node (ref "C153") (pin "P$1") (pinfunction "P$1_P$1") (pintype "bidirectional"))
      (node (ref "C154") (pin "1") (pinfunction "P$1_1") (pintype "bidirectional"))
      (node (ref "C155") (pin "1") (pinfunction "P$1_1") (pintype "bidirectional"))
      (node (ref "C156") (pin "1") (pinfunction "P$1_1") (pintype "bidirectional"))
      (node (ref "C157") (pin "1") (pinfunction "P$1_1") (pintype "bidirectional"))
      (node (ref "C158") (pin "P$1") (pinfunction "P$1_P$1") (pintype "bidirectional"))
      (node (ref "C159") (pin "1") (pinfunction "P$1_1") (pintype "bidirectional"))
      (node (ref "C16") (pin "P$2") (pinfunction "P$2_P$2") (pintype "bidirectional"))
      (node (ref "C160") (pin "1") (pinfunction "P$1_1") (pintype "bidirectional"))
      (node (ref "C161") (pin "1") (pinfunction "P$1_1") (pintype "bidirectional"))
      (node (ref "C162") (pin "1") (pinfunction "P$1_1") (pintype "bidirectional"))
      (node (ref "C163") (pin "1") (pinfunction "P$1_1") (pintype "bidirectional"))
      (node (ref "C164") (pin "1") (pinfunction "P$1_1") (pintype "bidirectional"))
      (node (ref "C165") (pin "1") (pinfunction "P$1_1") (pintype "bidirectional"))
      (node (ref "C166") (pin "P$1") (pinfunction "P$1_P$1") (pintype "bidirectional"))
      (node (ref "C167") (pin "1") (pinfunction "P$1_1") (pintype "bidirectional"))
      (node (ref "C168") (pin "1") (pinfunction "P$1_1") (pintype "bidirectional"))
      (node (ref "C169") (pin "1") (pinfunction "P$1_1") (pintype "bidirectional"))
      (node (ref "C17") (pin "P$2") (pinfunction "P$2_P$2") (pintype "bidirectional"))
      (node (ref "C170") (pin "1") (pinfunction "P$1_1") (pintype "bidirectional"))
      (node (ref "C171") (pin "1") (pinfunction "P$1_1") (pintype "bidirectional"))
      (node (ref "C172") (pin "1") (pinfunction "P$1_1") (pintype "bidirectional"))
      (node (ref "C173") (pin "1") (pinfunction "P$1_1") (pintype "bidirectional"))
      (node (ref "C174") (pin "1") (pinfunction "P$1_1") (pintype "bidirectional"))
      (node (ref "C175") (pin "P$2") (pinfunction "P$2_P$2") (pintype "bidirectional"))
      (node (ref "C176") (pin "P$2") (pinfunction "P$2_P$2") (pintype "bidirectional"))
      (node (ref "C177") (pin "1") (pinfunction "P$1_1") (pintype "bidirectional"))
      (node (ref "C178") (pin "1") (pinfunction "P$1_1") (pintype "bidirectional"))
      (node (ref "C179") (pin "P$2") (pinfunction "P$2_P$2") (pintype "bidirectional"))
      (node (ref "C18") (pin "-") (pinfunction "-_-") (pintype "bidirectional"))
      (node (ref "C180") (pin "P$2") (pinfunction "P$2_P$2") (pintype "bidirectional"))
      (node (ref "C181") (pin "1") (pinfunction "P$1_1") (pintype "bidirectional"))
      (node (ref "C182") (pin "1") (pinfunction "P$1_1") (pintype "bidirectional"))
      (node (ref "C183") (pin "1") (pinfunction "P$1_1") (pintype "bidirectional"))
      (node (ref "C184") (pin "1") (pinfunction "P$1_1") (pintype "bidirectional"))
      (node (ref "C185") (pin "1") (pinfunction "P$1_1") (pintype "bidirectional"))
      (node (ref "C186") (pin "1") (pinfunction "P$1_1") (pintype "bidirectional"))
      (node (ref "C187") (pin "1") (pinfunction "P$1_1") (pintype "bidirectional"))
      (node (ref "C188") (pin "1") (pinfunction "P$1_1") (pintype "bidirectional"))
      (node (ref "C189") (pin "1") (pinfunction "P$1_1") (pintype "bidirectional"))
      (node (ref "C19") (pin "2") (pinfunction "P$2_2") (pintype "bidirectional"))
      (node (ref "C190") (pin "1") (pinfunction "P$1_1") (pintype "bidirectional"))
      (node (ref "C191") (pin "1") (pinfunction "P$1_1") (pintype "bidirectional"))
      (node (ref "C192") (pin "1") (pinfunction "P$1_1") (pintype "bidirectional"))
      (node (ref "C193") (pin "1") (pinfunction "P$1_1") (pintype "bidirectional"))
      (node (ref "C194") (pin "1") (pinfunction "P$1_1") (pintype "bidirectional"))
      (node (ref "C195") (pin "1") (pinfunction "P$1_1") (pintype "bidirectional"))
      (node (ref "C196") (pin "P$2") (pinfunction "P$2_P$2") (pintype "bidirectional"))
      (node (ref "C197") (pin "P$2") (pinfunction "P$2_P$2") (pintype "bidirectional"))
      (node (ref "C198") (pin "P$2") (pinfunction "P$2_P$2") (pintype "bidirectional"))
      (node (ref "C199") (pin "P$2") (pinfunction "P$2_P$2") (pintype "bidirectional"))
      (node (ref "C2") (pin "-") (pinfunction "-_-") (pintype "bidirectional"))
      (node (ref "C20") (pin "P$2") (pinfunction "P$2_P$2") (pintype "bidirectional"))
      (node (ref "C21") (pin "P$2") (pinfunction "P$2_P$2") (pintype "bidirectional"))
      (node (ref "C216") (pin "1") (pinfunction "P$1_1") (pintype "bidirectional"))
      (node (ref "C217") (pin "1") (pinfunction "P$1_1") (pintype "bidirectional"))
      (node (ref "C219") (pin "1") (pinfunction "P$1_1") (pintype "bidirectional"))
      (node (ref "C22") (pin "-") (pinfunction "-_-") (pintype "bidirectional"))
      (node (ref "C220") (pin "P$1") (pinfunction "P$1_P$1") (pintype "bidirectional"))
      (node (ref "C23") (pin "2") (pinfunction "P$2_2") (pintype "bidirectional"))
      (node (ref "C24") (pin "P$2") (pinfunction "P$2_P$2") (pintype "bidirectional"))
      (node (ref "C25") (pin "P$2") (pinfunction "P$2_P$2") (pintype "bidirectional"))
      (node (ref "C26") (pin "-") (pinfunction "-_-") (pintype "bidirectional"))
      (node (ref "C27") (pin "2") (pinfunction "P$2_2") (pintype "bidirectional"))
      (node (ref "C28") (pin "1") (pinfunction "P$1_1") (pintype "bidirectional"))
      (node (ref "C29") (pin "P$1") (pinfunction "P$1_P$1") (pintype "bidirectional"))
      (node (ref "C3") (pin "2") (pinfunction "P$2_2") (pintype "bidirectional"))
      (node (ref "C30") (pin "P$1") (pinfunction "P$1_P$1") (pintype "bidirectional"))
      (node (ref "C31") (pin "P$1") (pinfunction "P$1_P$1") (pintype "bidirectional"))
      (node (ref "C32") (pin "P$1") (pinfunction "P$1_P$1") (pintype "bidirectional"))
      (node (ref "C33") (pin "P$1") (pinfunction "P$1_P$1") (pintype "bidirectional"))
      (node (ref "C34") (pin "P$1") (pinfunction "P$1_P$1") (pintype "bidirectional"))
      (node (ref "C35") (pin "P$1") (pinfunction "P$1_P$1") (pintype "bidirectional"))
      (node (ref "C36") (pin "P$1") (pinfunction "P$1_P$1") (pintype "bidirectional"))
      (node (ref "C37") (pin "1") (pinfunction "P$1_1") (pintype "bidirectional"))
      (node (ref "C38") (pin "P$1") (pinfunction "P$1_P$1") (pintype "bidirectional"))
      (node (ref "C39") (pin "P$1") (pinfunction "P$1_P$1") (pintype "bidirectional"))
      (node (ref "C4") (pin "2") (pinfunction "P$2_2") (pintype "bidirectional"))
      (node (ref "C40") (pin "P$1") (pinfunction "P$1_P$1") (pintype "bidirectional"))
      (node (ref "C41") (pin "P$1") (pinfunction "P$1_P$1") (pintype "bidirectional"))
      (node (ref "C42") (pin "P$1") (pinfunction "P$1_P$1") (pintype "bidirectional"))
      (node (ref "C43") (pin "P$1") (pinfunction "P$1_P$1") (pintype "bidirectional"))
      (node (ref "C44") (pin "P$1") (pinfunction "P$1_P$1") (pintype "bidirectional"))
      (node (ref "C45") (pin "P$1") (pinfunction "P$1_P$1") (pintype "bidirectional"))
      (node (ref "C46") (pin "1") (pinfunction "P$1_1") (pintype "bidirectional"))
      (node (ref "C47") (pin "P$1") (pinfunction "P$1_P$1") (pintype "bidirectional"))
      (node (ref "C48") (pin "P$1") (pinfunction "P$1_P$1") (pintype "bidirectional"))
      (node (ref "C49") (pin "P$1") (pinfunction "P$1_P$1") (pintype "bidirectional"))
      (node (ref "C5") (pin "2") (pinfunction "P$2_2") (pintype "bidirectional"))
      (node (ref "C50") (pin "P$1") (pinfunction "P$1_P$1") (pintype "bidirectional"))
      (node (ref "C51") (pin "P$1") (pinfunction "P$1_P$1") (pintype "bidirectional"))
      (node (ref "C52") (pin "P$1") (pinfunction "P$1_P$1") (pintype "bidirectional"))
      (node (ref "C53") (pin "P$1") (pinfunction "P$1_P$1") (pintype "bidirectional"))
      (node (ref "C54") (pin "P$1") (pinfunction "P$1_P$1") (pintype "bidirectional"))
      (node (ref "C56") (pin "1") (pinfunction "P$1_1") (pintype "bidirectional"))
      (node (ref "C57") (pin "1") (pinfunction "P$1_1") (pintype "bidirectional"))
      (node (ref "C58") (pin "1") (pinfunction "P$1_1") (pintype "bidirectional"))
      (node (ref "C59") (pin "1") (pinfunction "P$1_1") (pintype "bidirectional"))
      (node (ref "C6") (pin "-") (pinfunction "-_-") (pintype "bidirectional"))
      (node (ref "C67") (pin "1") (pinfunction "P$1_1") (pintype "bidirectional"))
      (node (ref "C7") (pin "2") (pinfunction "P$2_2") (pintype "bidirectional"))
      (node (ref "C71") (pin "1") (pinfunction "P$1_1") (pintype "bidirectional"))
      (node (ref "C72") (pin "1") (pinfunction "P$1_1") (pintype "bidirectional"))
      (node (ref "C73") (pin "1") (pinfunction "P$1_1") (pintype "bidirectional"))
      (node (ref "C75") (pin "1") (pinfunction "P$1_1") (pintype "bidirectional"))
      (node (ref "C76") (pin "1") (pinfunction "P$1_1") (pintype "bidirectional"))
      (node (ref "C77") (pin "P$1") (pinfunction "P$1_P$1") (pintype "bidirectional"))
      (node (ref "C78") (pin "P$1") (pinfunction "P$1_P$1") (pintype "bidirectional"))
      (node (ref "C79") (pin "P$1") (pinfunction "P$1_P$1") (pintype "bidirectional"))
      (node (ref "C8") (pin "2") (pinfunction "P$2_2") (pintype "bidirectional"))
      (node (ref "C80") (pin "P$1") (pinfunction "P$1_P$1") (pintype "bidirectional"))
      (node (ref "C81") (pin "P$1") (pinfunction "P$1_P$1") (pintype "bidirectional"))
      (node (ref "C82") (pin "P$1") (pinfunction "P$1_P$1") (pintype "bidirectional"))
      (node (ref "C83") (pin "P$1") (pinfunction "P$1_P$1") (pintype "bidirectional"))
      (node (ref "C84") (pin "P$1") (pinfunction "P$1_P$1") (pintype "bidirectional"))
      (node (ref "C89") (pin "1") (pinfunction "P$1_1") (pintype "bidirectional"))
      (node (ref "C9") (pin "2") (pinfunction "P$2_2") (pintype "bidirectional"))
      (node (ref "C90") (pin "1") (pinfunction "P$1_1") (pintype "bidirectional"))
      (node (ref "C91") (pin "-") (pinfunction "-_-") (pintype "bidirectional"))
      (node (ref "C92") (pin "1") (pinfunction "P$1_1") (pintype "bidirectional"))
      (node (ref "C93") (pin "2") (pinfunction "P$2_2") (pintype "bidirectional"))
      (node (ref "C94") (pin "2") (pinfunction "P$2_2") (pintype "bidirectional"))
      (node (ref "C95") (pin "1") (pinfunction "P$1_1") (pintype "bidirectional"))
      (node (ref "C96") (pin "1") (pinfunction "P$1_1") (pintype "bidirectional"))
      (node (ref "C97") (pin "1") (pinfunction "P$1_1") (pintype "bidirectional"))
      (node (ref "C98") (pin "2") (pinfunction "P$2_2") (pintype "bidirectional"))
      (node (ref "C99") (pin "2") (pinfunction "P$2_2") (pintype "bidirectional"))
      (node (ref "CON1") (pin "P$1") (pinfunction "1_P$1") (pintype "bidirectional"))
      (node (ref "CON14") (pin "P$4") (pinfunction "4_P$4") (pintype "bidirectional"))
      (node (ref "CON15") (pin "P$6") (pinfunction "6_P$6") (pintype "bidirectional"))
      (node (ref "CON16") (pin "P$6") (pinfunction "6_P$6") (pintype "bidirectional"))
      (node (ref "CON17") (pin "P$4") (pinfunction "4_P$4") (pintype "bidirectional"))
      (node (ref "CON18") (pin "1") (pinfunction "1_1") (pintype "bidirectional"))
      (node (ref "CON19") (pin "1") (pinfunction "1_1") (pintype "bidirectional"))
      (node (ref "CON19") (pin "4") (pinfunction "4_4") (pintype "bidirectional"))
      (node (ref "CON2") (pin "P$1") (pinfunction "1_P$1") (pintype "bidirectional"))
      (node (ref "CON20") (pin "1") (pinfunction "1_1") (pintype "bidirectional"))
      (node (ref "CON22") (pin "1") (pinfunction "1_1") (pintype "bidirectional"))
      (node (ref "CON23") (pin "1") (pinfunction "1_1") (pintype "bidirectional"))
      (node (ref "CON25") (pin "1") (pinfunction "1_1") (pintype "bidirectional"))
      (node (ref "CON26") (pin "1") (pinfunction "1_1") (pintype "bidirectional"))
      (node (ref "CON27") (pin "1") (pinfunction "1_1") (pintype "bidirectional"))
      (node (ref "CON27") (pin "4") (pinfunction "4_4") (pintype "bidirectional"))
      (node (ref "CON28") (pin "1") (pinfunction "1_1") (pintype "bidirectional"))
      (node (ref "CON30") (pin "1") (pinfunction "1_1") (pintype "bidirectional"))
      (node (ref "CON31") (pin "1") (pinfunction "1_1") (pintype "bidirectional"))
      (node (ref "CON32") (pin "1") (pinfunction "1_1") (pintype "bidirectional"))
      (node (ref "CON33") (pin "1") (pinfunction "1_1") (pintype "bidirectional"))
      (node (ref "CON35") (pin "1") (pinfunction "1_1") (pintype "bidirectional"))
      (node (ref "CON36") (pin "1") (pinfunction "1_1") (pintype "bidirectional"))
      (node (ref "CON37") (pin "1") (pinfunction "1_1") (pintype "bidirectional"))
      (node (ref "CON39") (pin "1") (pinfunction "1_1") (pintype "bidirectional"))
      (node (ref "CON40") (pin "1") (pinfunction "1_1") (pintype "bidirectional"))
      (node (ref "CON41") (pin "1") (pinfunction "1_1") (pintype "bidirectional"))
      (node (ref "CON42") (pin "1") (pinfunction "1_1") (pintype "bidirectional"))
      (node (ref "CON44") (pin "1") (pinfunction "1_1") (pintype "bidirectional"))
      (node (ref "CON45") (pin "1") (pinfunction "1_1") (pintype "bidirectional"))
      (node (ref "CON46") (pin "1") (pinfunction "1_1") (pintype "bidirectional"))
      (node (ref "CON48") (pin "1") (pinfunction "1_1") (pintype "bidirectional"))
      (node (ref "CON49") (pin "1") (pinfunction "1_1") (pintype "bidirectional"))
      (node (ref "CON50") (pin "1") (pinfunction "1_1") (pintype "bidirectional"))
      (node (ref "CON52") (pin "1") (pinfunction "1_1") (pintype "bidirectional"))
      (node (ref "CON53") (pin "1") (pinfunction "1_1") (pintype "bidirectional"))
      (node (ref "CON54") (pin "4") (pinfunction "GND_4") (pintype "bidirectional"))
      (node (ref "CON54") (pin "GND1") (pinfunction "GND_GND1") (pintype "bidirectional"))
      (node (ref "CON54") (pin "GND2") (pinfunction "GND_GND2") (pintype "bidirectional"))
      (node (ref "CON55") (pin "4") (pinfunction "GND_4") (pintype "bidirectional"))
      (node (ref "CON55") (pin "GND1") (pinfunction "GND_GND1") (pintype "bidirectional"))
      (node (ref "CON55") (pin "GND2") (pinfunction "GND_GND2") (pintype "bidirectional"))
      (node (ref "CON56") (pin "1") (pinfunction "1_1") (pintype "bidirectional"))
      (node (ref "CON57") (pin "12") (pinfunction "12_12") (pintype "bidirectional"))
      (node (ref "CON57") (pin "30") (pinfunction "30_30") (pintype "bidirectional"))
      (node (ref "CON58") (pin "12") (pinfunction "12_12") (pintype "bidirectional"))
      (node (ref "CON58") (pin "30") (pinfunction "30_30") (pintype "bidirectional"))
      (node (ref "CON6") (pin "P$1") (pinfunction "1_P$1") (pintype "bidirectional"))
      (node (ref "CON60") (pin "4") (pinfunction "GND_4") (pintype "bidirectional"))
      (node (ref "CON60") (pin "GND1") (pinfunction "GND_GND1") (pintype "bidirectional"))
      (node (ref "CON60") (pin "GND2") (pinfunction "GND_GND2") (pintype "bidirectional"))
      (node (ref "CON61") (pin "1") (pinfunction "1_1") (pintype "bidirectional"))
      (node (ref "CON62") (pin "1") (pinfunction "1_1") (pintype "bidirectional"))
      (node (ref "CON63") (pin "1") (pinfunction "1_1") (pintype "bidirectional"))
      (node (ref "CON64") (pin "1") (pinfunction "1_1") (pintype "bidirectional"))
      (node (ref "CON7") (pin "P$1") (pinfunction "1_P$1") (pintype "bidirectional"))
      (node (ref "D1") (pin "A") (pinfunction "A_A") (pintype "bidirectional"))
      (node (ref "D2") (pin "A") (pinfunction "A_A") (pintype "bidirectional"))
      (node (ref "D3") (pin "A") (pinfunction "A_A") (pintype "bidirectional"))
      (node (ref "D4") (pin "C") (pinfunction "C_C") (pintype "bidirectional"))
      (node (ref "D5") (pin "C") (pinfunction "C_C") (pintype "bidirectional"))
      (node (ref "D6") (pin "C") (pinfunction "C_C") (pintype "bidirectional"))
      (node (ref "D7") (pin "C") (pinfunction "C_C") (pintype "bidirectional"))
      (node (ref "D8") (pin "C") (pinfunction "C_C") (pintype "bidirectional"))
      (node (ref "IC1") (pin "12") (pinfunction "CLKSEL_12") (pintype "passive"))
      (node (ref "IC1") (pin "29") (pinfunction "DGND_29") (pintype "passive"))
      (node (ref "IC1") (pin "30") (pinfunction "VREFN_30") (pintype "passive"))
      (node (ref "IC1") (pin "32") (pinfunction "AINCOM_32") (pintype "passive"))
      (node (ref "IC1") (pin "41") (pinfunction "ADCINN_41") (pintype "passive"))
      (node (ref "IC1") (pin "5") (pinfunction "AVSS_5") (pintype "passive"))
      (node (ref "IC2") (pin "12") (pinfunction "DIN_12") (pintype "passive"))
      (node (ref "IC2") (pin "21") (pinfunction "DGND_21") (pintype "passive"))
      (node (ref "IC2") (pin "24") (pinfunction "DGND_24") (pintype "passive"))
      (node (ref "IC2") (pin "25") (pinfunction "DGND_25") (pintype "passive"))
      (node (ref "IC2") (pin "30") (pinfunction "FORMAT2_30") (pintype "passive"))
      (node (ref "IC2") (pin "31") (pinfunction "FORMAT1_31") (pintype "passive"))
      (node (ref "IC2") (pin "33") (pinfunction "MODE1_33") (pintype "passive"))
      (node (ref "IC2") (pin "4") (pinfunction "AINN1_4") (pintype "passive"))
      (node (ref "IC2") (pin "43") (pinfunction "AGND_43") (pintype "passive"))
      (node (ref "IC2") (pin "54") (pinfunction "AGND_54") (pintype "passive"))
      (node (ref "IC2") (pin "57") (pinfunction "VREFN_57") (pintype "passive"))
      (node (ref "IC2") (pin "58") (pinfunction "AGND_58") (pintype "passive"))
      (node (ref "IC2") (pin "59") (pinfunction "AGND_59") (pintype "passive"))
      (node (ref "IC2") (pin "6") (pinfunction "AGND_6") (pintype "passive"))
      (node (ref "IC2") (pin "7") (pinfunction "DGND_7") (pintype "passive"))
      (node (ref "IC2") (pin "8") (pinfunction "TEST0_8") (pintype "passive"))
      (node (ref "IC2") (pin "9") (pinfunction "TEST1_9") (pintype "passive"))
      (node (ref "IC2") (pin "POWERPAD") (pinfunction "PGND_POWERPAD") (pintype "bidirectional"))
      (node (ref "IC3") (pin "4") (pinfunction "GND_4") (pintype "passive"))
      (node (ref "IC3") (pin "7") (pinfunction "NC_7") (pintype "passive"))
      (node (ref "IC4") (pin "4") (pinfunction "GND_4") (pintype "passive"))
      (node (ref "IC4") (pin "7") (pinfunction "NC_7") (pintype "passive"))
      (node (ref "J10") (pin "P$1") (pinfunction "1_P$1") (pintype "bidirectional"))
      (node (ref "J16") (pin "P$1") (pinfunction "1_P$1") (pintype "bidirectional"))
      (node (ref "J17") (pin "P$1") (pinfunction "1_P$1") (pintype "bidirectional"))
      (node (ref "J18") (pin "P$1") (pinfunction "1_P$1") (pintype "bidirectional"))
      (node (ref "J19") (pin "P$1") (pinfunction "1_P$1") (pintype "bidirectional"))
      (node (ref "J22") (pin "P$1") (pinfunction "1_P$1") (pintype "bidirectional"))
      (node (ref "J29") (pin "P$1") (pinfunction "1_P$1") (pintype "bidirectional"))
      (node (ref "J47") (pin "10") (pinfunction "10_10") (pintype "passive"))
      (node (ref "J50") (pin "P$1") (pinfunction "1_P$1") (pintype "bidirectional"))
      (node (ref "R107") (pin "2") (pinfunction "P$2_2") (pintype "bidirectional"))
      (node (ref "R108") (pin "2") (pinfunction "P$2_2") (pintype "bidirectional"))
      (node (ref "R109") (pin "2") (pinfunction "P$2_2") (pintype "bidirectional"))
      (node (ref "R110") (pin "2") (pinfunction "P$2_2") (pintype "bidirectional"))
      (node (ref "R16") (pin "2") (pinfunction "P$2_2") (pintype "bidirectional"))
      (node (ref "R18") (pin "2") (pinfunction "P$2_2") (pintype "bidirectional"))
      (node (ref "R20") (pin "2") (pinfunction "P$2_2") (pintype "bidirectional"))
      (node (ref "R26") (pin "2") (pinfunction "P$2_2") (pintype "bidirectional"))
      (node (ref "R28") (pin "2") (pinfunction "P$2_2") (pintype "bidirectional"))
      (node (ref "R30") (pin "2") (pinfunction "P$2_2") (pintype "bidirectional"))
      (node (ref "R33") (pin "2") (pinfunction "P$2_2") (pintype "bidirectional"))
      (node (ref "R43") (pin "2") (pinfunction "P$2_2") (pintype "bidirectional"))
      (node (ref "R45") (pin "P$2") (pinfunction "P$2_P$2") (pintype "bidirectional"))
      (node (ref "R48") (pin "2") (pinfunction "P$2_2") (pintype "bidirectional"))
      (node (ref "R5") (pin "2") (pinfunction "P$2_2") (pintype "bidirectional"))
      (node (ref "R52") (pin "P$2") (pinfunction "P$2_P$2") (pintype "bidirectional"))
      (node (ref "R55") (pin "2") (pinfunction "P$2_2") (pintype "bidirectional"))
      (node (ref "R57") (pin "P$2") (pinfunction "P$2_P$2") (pintype "bidirectional"))
      (node (ref "R6") (pin "2") (pinfunction "P$2_2") (pintype "bidirectional"))
      (node (ref "R63") (pin "2") (pinfunction "P$2_2") (pintype "bidirectional"))
      (node (ref "R65") (pin "P$2") (pinfunction "P$2_P$2") (pintype "bidirectional"))
      (node (ref "R68") (pin "2") (pinfunction "P$2_2") (pintype "bidirectional"))
      (node (ref "R7") (pin "2") (pinfunction "P$2_2") (pintype "bidirectional"))
      (node (ref "R70") (pin "P$2") (pinfunction "P$2_P$2") (pintype "bidirectional"))
      (node (ref "R76") (pin "2") (pinfunction "P$2_2") (pintype "bidirectional"))
      (node (ref "R78") (pin "P$2") (pinfunction "P$2_P$2") (pintype "bidirectional"))
      (node (ref "R8") (pin "2") (pinfunction "P$2_2") (pintype "bidirectional"))
      (node (ref "R81") (pin "2") (pinfunction "P$2_2") (pintype "bidirectional"))
      (node (ref "R83") (pin "P$2") (pinfunction "P$2_P$2") (pintype "bidirectional"))
      (node (ref "R86") (pin "2") (pinfunction "P$2_2") (pintype "bidirectional"))
      (node (ref "R88") (pin "P$2") (pinfunction "P$2_P$2") (pintype "bidirectional"))
      (node (ref "R9") (pin "2") (pinfunction "P$2_2") (pintype "bidirectional"))
      (node (ref "R95") (pin "1") (pinfunction "P$1_1") (pintype "bidirectional"))
      (node (ref "R96") (pin "1") (pinfunction "P$1_1") (pintype "bidirectional"))
      (node (ref "T1") (pin "P$2") (pinfunction "S_P$2") (pintype "bidirectional"))
      (node (ref "T2") (pin "P$2") (pinfunction "S_P$2") (pintype "bidirectional"))
      (node (ref "T3") (pin "P$2") (pinfunction "S_P$2") (pintype "bidirectional"))
      (node (ref "U1") (pin "1") (pinfunction "Y0_1") (pintype "bidirectional"))
      (node (ref "U1") (pin "2") (pinfunction "Y2_2") (pintype "bidirectional"))
      (node (ref "U1") (pin "3") (pinfunction "Y_3") (pintype "bidirectional"))
      (node (ref "U1") (pin "4") (pinfunction "Y3_4") (pintype "bidirectional"))
      (node (ref "U1") (pin "5") (pinfunction "Y1_5") (pintype "bidirectional"))
      (node (ref "U1") (pin "6") (pinfunction "EN_6") (pintype "bidirectional"))
      (node (ref "U1") (pin "7") (pinfunction "GND_7") (pintype "bidirectional"))
      (node (ref "U1") (pin "8") (pinfunction "GND_8") (pintype "bidirectional"))
      (node (ref "U10") (pin "P$11") (pinfunction "M3_P$11") (pintype "bidirectional"))
      (node (ref "U10") (pin "P$23") (pinfunction "GNDD_P$23") (pintype "bidirectional"))
      (node (ref "U10") (pin "P$24") (pinfunction "GNDC_P$24") (pintype "bidirectional"))
      (node (ref "U10") (pin "P$31") (pinfunction "GNDB_P$31") (pintype "bidirectional"))
      (node (ref "U10") (pin "P$32") (pinfunction "GNDA_P$32") (pintype "bidirectional"))
      (node (ref "U10") (pin "P$37") (pinfunction "GND_P$37") (pintype "bidirectional"))
      (node (ref "U10") (pin "P$8") (pinfunction "GND_P$8") (pintype "bidirectional"))
      (node (ref "U10") (pin "P$9") (pinfunction "GND_P$9") (pintype "bidirectional"))
      (node (ref "U11") (pin "P$11") (pinfunction "M3_P$11") (pintype "bidirectional"))
      (node (ref "U11") (pin "P$23") (pinfunction "GNDD_P$23") (pintype "bidirectional"))
      (node (ref "U11") (pin "P$24") (pinfunction "GNDC_P$24") (pintype "bidirectional"))
      (node (ref "U11") (pin "P$31") (pinfunction "GNDB_P$31") (pintype "bidirectional"))
      (node (ref "U11") (pin "P$32") (pinfunction "GNDA_P$32") (pintype "bidirectional"))
      (node (ref "U11") (pin "P$37") (pinfunction "GND_P$37") (pintype "bidirectional"))
      (node (ref "U11") (pin "P$8") (pinfunction "GND_P$8") (pintype "bidirectional"))
      (node (ref "U11") (pin "P$9") (pinfunction "GND_P$9") (pintype "bidirectional"))
      (node (ref "U12") (pin "P$1") (pinfunction "NC_P$1") (pintype "bidirectional"))
      (node (ref "U12") (pin "P$4") (pinfunction "GND_P$4") (pintype "bidirectional"))
      (node (ref "U13") (pin "P$1") (pinfunction "NC_P$1") (pintype "bidirectional"))
      (node (ref "U13") (pin "P$4") (pinfunction "GND_P$4") (pintype "bidirectional"))
      (node (ref "U14") (pin "P$11") (pinfunction "M3_P$11") (pintype "bidirectional"))
      (node (ref "U14") (pin "P$14") (pinfunction "PWMC_P$14") (pintype "bidirectional"))
      (node (ref "U14") (pin "P$16") (pinfunction "PWMD_P$16") (pintype "bidirectional"))
      (node (ref "U14") (pin "P$23") (pinfunction "GNDD_P$23") (pintype "bidirectional"))
      (node (ref "U14") (pin "P$24") (pinfunction "GNDC_P$24") (pintype "bidirectional"))
      (node (ref "U14") (pin "P$31") (pinfunction "GNDB_P$31") (pintype "bidirectional"))
      (node (ref "U14") (pin "P$32") (pinfunction "GNDA_P$32") (pintype "bidirectional"))
      (node (ref "U14") (pin "P$37") (pinfunction "GND_P$37") (pintype "bidirectional"))
      (node (ref "U14") (pin "P$8") (pinfunction "GND_P$8") (pintype "bidirectional"))
      (node (ref "U14") (pin "P$9") (pinfunction "GND_P$9") (pintype "bidirectional"))
      (node (ref "U15") (pin "P$1") (pinfunction "NC_P$1") (pintype "bidirectional"))
      (node (ref "U15") (pin "P$4") (pinfunction "GND_P$4") (pintype "bidirectional"))
      (node (ref "U16") (pin "P$1") (pinfunction "NC_P$1") (pintype "bidirectional"))
      (node (ref "U16") (pin "P$4") (pinfunction "GND_P$4") (pintype "bidirectional"))
      (node (ref "U17") (pin "GND") (pinfunction "GND_GND") (pintype "bidirectional"))
      (node (ref "U18") (pin "P$1") (pinfunction "NC_P$1") (pintype "bidirectional"))
      (node (ref "U18") (pin "P$4") (pinfunction "GND_P$4") (pintype "bidirectional"))
      (node (ref "U19") (pin "GND") (pinfunction "GND_GND") (pintype "bidirectional"))
      (node (ref "U20") (pin "24") (pinfunction "EECS_24") (pintype "bidirectional"))
      (node (ref "U20") (pin "34") (pinfunction "TEST2_34") (pintype "bidirectional"))
      (node (ref "U20") (pin "44") (pinfunction "CLK24_EN_44") (pintype "bidirectional"))
      (node (ref "U20") (pin "GND") (pinfunction "GND_GND") (pintype "bidirectional"))
      (node (ref "U21") (pin "P$1") (pinfunction "GND_P$1") (pintype "bidirectional"))
      (node (ref "U21") (pin "P$10") (pinfunction "P$7_P$10") (pintype "bidirectional"))
      (node (ref "U21") (pin "P$11") (pinfunction "P$11_P$11") (pintype "bidirectional"))
      (node (ref "U21") (pin "P$12") (pinfunction "P$12_P$12") (pintype "bidirectional"))
      (node (ref "U21") (pin "P$13") (pinfunction "P$13_P$13") (pintype "bidirectional"))
      (node (ref "U21") (pin "P$14") (pinfunction "P$14_P$14") (pintype "bidirectional"))
      (node (ref "U21") (pin "P$15") (pinfunction "P$15_P$15") (pintype "bidirectional"))
      (node (ref "U21") (pin "P$16") (pinfunction "P$16_P$16") (pintype "bidirectional"))
      (node (ref "U21") (pin "P$17") (pinfunction "P$17_P$17") (pintype "bidirectional"))
      (node (ref "U21") (pin "P$18") (pinfunction "P$18_P$18") (pintype "bidirectional"))
      (node (ref "U21") (pin "P$7") (pinfunction "P$10_P$7") (pintype "bidirectional"))
      (node (ref "U21") (pin "P$8") (pinfunction "P$9_P$8") (pintype "bidirectional"))
      (node (ref "U21") (pin "P$9") (pinfunction "P$8_P$9") (pintype "bidirectional"))
      (node (ref "U22") (pin "P$1") (pinfunction "GND_P$1") (pintype "bidirectional"))
      (node (ref "U22") (pin "P$10") (pinfunction "P$7_P$10") (pintype "bidirectional"))
      (node (ref "U22") (pin "P$11") (pinfunction "P$11_P$11") (pintype "bidirectional"))
      (node (ref "U22") (pin "P$12") (pinfunction "P$12_P$12") (pintype "bidirectional"))
      (node (ref "U22") (pin "P$13") (pinfunction "P$13_P$13") (pintype "bidirectional"))
      (node (ref "U22") (pin "P$14") (pinfunction "P$14_P$14") (pintype "bidirectional"))
      (node (ref "U22") (pin "P$15") (pinfunction "P$15_P$15") (pintype "bidirectional"))
      (node (ref "U22") (pin "P$16") (pinfunction "P$16_P$16") (pintype "bidirectional"))
      (node (ref "U22") (pin "P$17") (pinfunction "P$17_P$17") (pintype "bidirectional"))
      (node (ref "U22") (pin "P$18") (pinfunction "P$18_P$18") (pintype "bidirectional"))
      (node (ref "U22") (pin "P$7") (pinfunction "P$10_P$7") (pintype "bidirectional"))
      (node (ref "U22") (pin "P$8") (pinfunction "P$9_P$8") (pintype "bidirectional"))
      (node (ref "U22") (pin "P$9") (pinfunction "P$8_P$9") (pintype "bidirectional"))
      (node (ref "U23") (pin "2") (pinfunction "GND_2") (pintype "bidirectional"))
      (node (ref "U23") (pin "3") (pinfunction "GND_3") (pintype "bidirectional"))
      (node (ref "U23") (pin "5") (pinfunction "GND_5") (pintype "bidirectional"))
      (node (ref "U23") (pin "GND") (pinfunction "GND_GND") (pintype "bidirectional"))
      (node (ref "U24") (pin "P$1") (pinfunction "+_P$1") (pintype "bidirectional"))
      (node (ref "U24") (pin "P$2") (pinfunction "GND_P$2") (pintype "bidirectional"))
      (node (ref "U25") (pin "P$11") (pinfunction "GND_P$11") (pintype "bidirectional"))
      (node (ref "U26") (pin "P$11") (pinfunction "GND_P$11") (pintype "bidirectional"))
      (node (ref "U27") (pin "P$11") (pinfunction "GND_P$11") (pintype "bidirectional"))
      (node (ref "U28") (pin "P$11") (pinfunction "GND_P$11") (pintype "bidirectional"))
      (node (ref "U29") (pin "GND") (pinfunction "GND_GND") (pintype "bidirectional"))
      (node (ref "U29") (pin "GND1") (pinfunction "GND1_GND1") (pintype "bidirectional"))
      (node (ref "U29") (pin "GND2") (pinfunction "GND2_GND2") (pintype "bidirectional"))
      (node (ref "U3") (pin "P$3") (pinfunction "GND_P$3") (pintype "bidirectional"))
      (node (ref "U30") (pin "P$11") (pinfunction "GND_P$11") (pintype "bidirectional"))
      (node (ref "U31") (pin "P$11") (pinfunction "GND_P$11") (pintype "bidirectional"))
      (node (ref "U32") (pin "P$11") (pinfunction "GND_P$11") (pintype "bidirectional"))
      (node (ref "U33") (pin "P$12") (pinfunction "GND_P$12") (pintype "bidirectional"))
      (node (ref "U33") (pin "P$2") (pinfunction "GND_P$2") (pintype "bidirectional"))
      (node (ref "U33") (pin "P$3") (pinfunction "GND_P$3") (pintype "bidirectional"))
      (node (ref "U33") (pin "P$4") (pinfunction "GND_P$4") (pintype "bidirectional"))
      (node (ref "U33") (pin "P$6") (pinfunction "GND_P$6") (pintype "bidirectional"))
      (node (ref "U34") (pin "GND") (pinfunction "GND_GND") (pintype "bidirectional"))
      (node (ref "U34") (pin "P$16") (pinfunction "ADDR_P$16") (pintype "bidirectional"))
      (node (ref "U34") (pin "P$6") (pinfunction "GND_P$6") (pintype "bidirectional"))
      (node (ref "U35") (pin "2") (pinfunction "GND_2") (pintype "bidirectional"))
      (node (ref "U35") (pin "3") (pinfunction "GND_3") (pintype "bidirectional"))
      (node (ref "U35") (pin "5") (pinfunction "GND_5") (pintype "bidirectional"))
      (node (ref "U35") (pin "GND") (pinfunction "GND_GND") (pintype "bidirectional"))
      (node (ref "U36") (pin "P$11") (pinfunction "GND_P$11") (pintype "bidirectional"))
      (node (ref "U36") (pin "P$12") (pinfunction "GND_P$12") (pintype "bidirectional"))
      (node (ref "U36") (pin "P$2") (pinfunction "GND_P$2") (pintype "bidirectional"))
      (node (ref "U36") (pin "P$3") (pinfunction "GND_P$3") (pintype "bidirectional"))
      (node (ref "U36") (pin "P$7") (pinfunction "GND_P$7") (pintype "bidirectional"))
      (node (ref "U36") (pin "P$9") (pinfunction "GND_P$9") (pintype "bidirectional"))
      (node (ref "U37") (pin "14") (pinfunction "GND_14") (pintype "bidirectional"))
      (node (ref "U37") (pin "15") (pinfunction "GND_15") (pintype "bidirectional"))
      (node (ref "U37") (pin "16") (pinfunction "GND_16") (pintype "bidirectional"))
      (node (ref "U37") (pin "17") (pinfunction "GND_17") (pintype "bidirectional"))
      (node (ref "U37") (pin "18") (pinfunction "GND_18") (pintype "bidirectional"))
      (node (ref "U37") (pin "2") (pinfunction "GND_2") (pintype "bidirectional"))
      (node (ref "U37") (pin "20") (pinfunction "GND_20") (pintype "bidirectional"))
      (node (ref "U37") (pin "3") (pinfunction "GND_3") (pintype "bidirectional"))
      (node (ref "U37") (pin "4") (pinfunction "GND_4") (pintype "bidirectional"))
      (node (ref "U37") (pin "5") (pinfunction "GND_5") (pintype "bidirectional"))
      (node (ref "U37") (pin "6") (pinfunction "GND_6") (pintype "bidirectional"))
      (node (ref "U37") (pin "PAD") (pinfunction "GND_PAD") (pintype "bidirectional"))
      (node (ref "U38") (pin "2") (pinfunction "GND_2") (pintype "bidirectional"))
      (node (ref "U38") (pin "3") (pinfunction "GND_3") (pintype "bidirectional"))
      (node (ref "U38") (pin "5") (pinfunction "GND_5") (pintype "bidirectional"))
      (node (ref "U38") (pin "GND") (pinfunction "GND_GND") (pintype "bidirectional"))
      (node (ref "U39") (pin "GND") (pinfunction "GND_GND") (pintype "bidirectional"))
      (node (ref "U39") (pin "P$16") (pinfunction "ADDR_P$16") (pintype "bidirectional"))
      (node (ref "U39") (pin "P$6") (pinfunction "GND_P$6") (pintype "bidirectional"))
      (node (ref "U4") (pin "P$3") (pinfunction "GND_P$3") (pintype "bidirectional"))
      (node (ref "U4") (pin "P$9") (pinfunction "GND_P$9") (pintype "bidirectional"))
      (node (ref "U40") (pin "2") (pinfunction "GND_2") (pintype "bidirectional"))
      (node (ref "U40") (pin "3") (pinfunction "GND_3") (pintype "bidirectional"))
      (node (ref "U40") (pin "5") (pinfunction "GND_5") (pintype "bidirectional"))
      (node (ref "U40") (pin "GND") (pinfunction "GND_GND") (pintype "bidirectional"))
      (node (ref "U5") (pin "P$3") (pinfunction "GND_P$3") (pintype "bidirectional"))
      (node (ref "U5") (pin "P$9") (pinfunction "GND_P$9") (pintype "bidirectional"))
      (node (ref "U6") (pin "P$3") (pinfunction "GND_P$3") (pintype "bidirectional"))
      (node (ref "U6") (pin "P$9") (pinfunction "GND_P$9") (pintype "bidirectional"))
      (node (ref "U7") (pin "P$1") (pinfunction "NC_P$1") (pintype "bidirectional"))
      (node (ref "U7") (pin "P$4") (pinfunction "GND_P$4") (pintype "bidirectional"))
      (node (ref "U8") (pin "P$1") (pinfunction "NC_P$1") (pintype "bidirectional"))
      (node (ref "U8") (pin "P$4") (pinfunction "GND_P$4") (pintype "bidirectional"))
      (node (ref "U9") (pin "P$11") (pinfunction "M3_P$11") (pintype "bidirectional"))
      (node (ref "U9") (pin "P$14") (pinfunction "PWMC_P$14") (pintype "bidirectional"))
      (node (ref "U9") (pin "P$16") (pinfunction "PWMD_P$16") (pintype "bidirectional"))
      (node (ref "U9") (pin "P$23") (pinfunction "GNDD_P$23") (pintype "bidirectional"))
      (node (ref "U9") (pin "P$24") (pinfunction "GNDC_P$24") (pintype "bidirectional"))
      (node (ref "U9") (pin "P$31") (pinfunction "GNDB_P$31") (pintype "bidirectional"))
      (node (ref "U9") (pin "P$32") (pinfunction "GNDA_P$32") (pintype "bidirectional"))
      (node (ref "U9") (pin "P$37") (pinfunction "GND_P$37") (pintype "bidirectional"))
      (node (ref "U9") (pin "P$8") (pinfunction "GND_P$8") (pintype "bidirectional"))
      (node (ref "U9") (pin "P$9") (pinfunction "GND_P$9") (pintype "bidirectional"))
    )
    (net (code "73") (name "I2C0") (class "Default")
      (node (ref "CON57") (pin "22") (pinfunction "22_22") (pintype "bidirectional"))
      (node (ref "U27") (pin "P$3") (pinfunction "A2_P$3") (pintype "bidirectional"))
    )
    (net (code "74") (name "I2C0°") (class "Default")
      (node (ref "CON49") (pin "3") (pinfunction "3_3") (pintype "bidirectional"))
      (node (ref "U27") (pin "P$18") (pinfunction "B2_P$18") (pintype "bidirectional"))
    )
    (net (code "75") (name "I2C1") (class "Default")
      (node (ref "CON58") (pin "24") (pinfunction "24_24") (pintype "bidirectional"))
      (node (ref "U30") (pin "P$8") (pinfunction "A7_P$8") (pintype "bidirectional"))
    )
    (net (code "76") (name "I2C1°") (class "Default")
      (node (ref "CON53") (pin "3") (pinfunction "3_3") (pintype "bidirectional"))
      (node (ref "U30") (pin "P$13") (pinfunction "B7_P$13") (pintype "bidirectional"))
    )
    (net (code "77") (name "IMU_DRDY") (class "Default")
      (node (ref "CON58") (pin "5") (pinfunction "5_5") (pintype "bidirectional"))
      (node (ref "U37") (pin "12") (pinfunction "INT_12") (pintype "bidirectional"))
    )
    (net (code "78") (name "IMU_FSYNC") (class "Default")
      (node (ref "J51") (pin "P$2") (pinfunction "2_P$2") (pintype "bidirectional"))
      (node (ref "U29") (pin "RESET") (pinfunction "/RESET_RESET") (pintype "bidirectional"))
    )
    (net (code "79") (name "IMU_SS") (class "Default")
      (node (ref "CON58") (pin "3") (pinfunction "3_3") (pintype "bidirectional"))
      (node (ref "U37") (pin "22") (pinfunction "~{CS}_22") (pintype "bidirectional"))
    )
    (net (code "80") (name "IO0") (class "Default")
      (node (ref "CON57") (pin "17") (pinfunction "17_17") (pintype "bidirectional"))
      (node (ref "U28") (pin "P$9") (pinfunction "A8_P$9") (pintype "bidirectional"))
    )
    (net (code "81") (name "IO0°") (class "Default")
      (node (ref "C102") (pin "2") (pinfunction "P$2_2") (pintype "bidirectional"))
      (node (ref "R42") (pin "2") (pinfunction "P$2_2") (pintype "bidirectional"))
      (node (ref "U28") (pin "P$12") (pinfunction "B8_P$12") (pintype "bidirectional"))
    )
    (net (code "82") (name "IO1") (class "Default")
      (node (ref "CON57") (pin "15") (pinfunction "15_15") (pintype "bidirectional"))
      (node (ref "U28") (pin "P$8") (pinfunction "A7_P$8") (pintype "bidirectional"))
    )
    (net (code "83") (name "IO1°") (class "Default")
      (node (ref "C108") (pin "2") (pinfunction "P$2_2") (pintype "bidirectional"))
      (node (ref "R47") (pin "2") (pinfunction "P$2_2") (pintype "bidirectional"))
      (node (ref "U28") (pin "P$13") (pinfunction "B7_P$13") (pintype "bidirectional"))
    )
    (net (code "84") (name "IO2") (class "Default")
      (node (ref "CON57") (pin "13") (pinfunction "13_13") (pintype "bidirectional"))
      (node (ref "U28") (pin "P$7") (pinfunction "A6_P$7") (pintype "bidirectional"))
    )
    (net (code "85") (name "IO2°") (class "Default")
      (node (ref "C114") (pin "2") (pinfunction "P$2_2") (pintype "bidirectional"))
      (node (ref "R54") (pin "2") (pinfunction "P$2_2") (pintype "bidirectional"))
      (node (ref "U28") (pin "P$14") (pinfunction "B6_P$14") (pintype "bidirectional"))
    )
    (net (code "86") (name "IO3") (class "Default")
      (node (ref "CON57") (pin "9") (pinfunction "9_9") (pintype "bidirectional"))
      (node (ref "U28") (pin "P$6") (pinfunction "A5_P$6") (pintype "bidirectional"))
    )
    (net (code "87") (name "IO3°") (class "Default")
      (node (ref "C117") (pin "2") (pinfunction "P$2_2") (pintype "bidirectional"))
      (node (ref "R60") (pin "2") (pinfunction "P$2_2") (pintype "bidirectional"))
      (node (ref "U28") (pin "P$15") (pinfunction "B5_P$15") (pintype "bidirectional"))
    )
    (net (code "88") (name "IO4") (class "Default")
      (node (ref "CON57") (pin "7") (pinfunction "7_7") (pintype "bidirectional"))
      (node (ref "U28") (pin "P$5") (pinfunction "A4_P$5") (pintype "bidirectional"))
    )
    (net (code "89") (name "IO4°") (class "Default")
      (node (ref "C124") (pin "2") (pinfunction "P$2_2") (pintype "bidirectional"))
      (node (ref "R67") (pin "2") (pinfunction "P$2_2") (pintype "bidirectional"))
      (node (ref "U28") (pin "P$16") (pinfunction "B4_P$16") (pintype "bidirectional"))
    )
    (net (code "90") (name "IO5") (class "Default")
      (node (ref "CON57") (pin "5") (pinfunction "5_5") (pintype "bidirectional"))
      (node (ref "U28") (pin "P$4") (pinfunction "A3_P$4") (pintype "bidirectional"))
    )
    (net (code "91") (name "IO5°") (class "Default")
      (node (ref "C131") (pin "2") (pinfunction "P$2_2") (pintype "bidirectional"))
      (node (ref "R75") (pin "2") (pinfunction "P$2_2") (pintype "bidirectional"))
      (node (ref "U28") (pin "P$17") (pinfunction "B3_P$17") (pintype "bidirectional"))
    )
    (net (code "92") (name "IO6") (class "Default")
      (node (ref "CON57") (pin "3") (pinfunction "3_3") (pintype "bidirectional"))
      (node (ref "U28") (pin "P$3") (pinfunction "A2_P$3") (pintype "bidirectional"))
    )
    (net (code "93") (name "IO6°") (class "Default")
      (node (ref "C134") (pin "2") (pinfunction "P$2_2") (pintype "bidirectional"))
      (node (ref "R80") (pin "2") (pinfunction "P$2_2") (pintype "bidirectional"))
      (node (ref "U28") (pin "P$18") (pinfunction "B2_P$18") (pintype "bidirectional"))
    )
    (net (code "94") (name "IO7") (class "Default")
      (node (ref "CON57") (pin "1") (pinfunction "1_1") (pintype "bidirectional"))
      (node (ref "U28") (pin "P$1") (pinfunction "A1_P$1") (pintype "bidirectional"))
    )
    (net (code "95") (name "IO7°") (class "Default")
      (node (ref "C137") (pin "2") (pinfunction "P$2_2") (pintype "bidirectional"))
      (node (ref "R85") (pin "2") (pinfunction "P$2_2") (pintype "bidirectional"))
      (node (ref "U28") (pin "P$20") (pinfunction "B1_P$20") (pintype "bidirectional"))
    )
    (net (code "96") (name "LAN_3V3") (class "Default")
      (node (ref "C143") (pin "2") (pinfunction "P$2_2") (pintype "bidirectional"))
      (node (ref "C144") (pin "2") (pinfunction "P$2_2") (pintype "bidirectional"))
      (node (ref "C145") (pin "2") (pinfunction "P$2_2") (pintype "bidirectional"))
      (node (ref "C146") (pin "2") (pinfunction "P$2_2") (pintype "bidirectional"))
      (node (ref "C147") (pin "2") (pinfunction "P$2_2") (pintype "bidirectional"))
      (node (ref "C148") (pin "P$2") (pinfunction "P$2_P$2") (pintype "bidirectional"))
      (node (ref "L9") (pin "2") (pinfunction "2_2") (pintype "bidirectional"))
      (node (ref "U20") (pin "10") (pinfunction "VDD33A_10") (pintype "bidirectional"))
      (node (ref "U20") (pin "49") (pinfunction "VDD33A_49") (pintype "bidirectional"))
      (node (ref "U20") (pin "5") (pinfunction "VDD33A_5") (pintype "bidirectional"))
      (node (ref "U20") (pin "51") (pinfunction "VDD33A_51") (pintype "bidirectional"))
      (node (ref "U20") (pin "54") (pinfunction "VDD33A_54") (pintype "bidirectional"))
      (node (ref "U20") (pin "57") (pinfunction "VDD33A_57") (pintype "bidirectional"))
      (node (ref "U20") (pin "64") (pinfunction "VDD33A_64") (pintype "bidirectional"))
    )
    (net (code "97") (name "LEDA") (class "Default")
      (node (ref "CON58") (pin "1") (pinfunction "1_1") (pintype "bidirectional"))
      (node (ref "R10") (pin "1") (pinfunction "P$1_1") (pintype "bidirectional"))
    )
    (net (code "98") (name "LEDB") (class "Default")
      (node (ref "CON58") (pin "2") (pinfunction "2_2") (pintype "bidirectional"))
      (node (ref "R11") (pin "1") (pinfunction "P$1_1") (pintype "bidirectional"))
    )
    (net (code "99") (name "LOW_VOLTAGE") (class "Default")
      (node (ref "C4") (pin "1") (pinfunction "P$1_1") (pintype "bidirectional"))
      (node (ref "IC2") (pin "3") (pinfunction "AINP1_3") (pintype "passive"))
      (node (ref "U1") (pin "13") (pinfunction "X_13") (pintype "bidirectional"))
    )
    (net (code "100") (name "LV_MUXA") (class "Default")
      (node (ref "CON58") (pin "40") (pinfunction "40_40") (pintype "bidirectional"))
      (node (ref "U1") (pin "10") (pinfunction "A_10") (pintype "bidirectional"))
    )
    (net (code "101") (name "LV_MUXB") (class "Default")
      (node (ref "CON58") (pin "39") (pinfunction "39_39") (pintype "bidirectional"))
      (node (ref "U1") (pin "9") (pinfunction "B_9") (pintype "bidirectional"))
    )
    (net (code "102") (name "M0_CS") (class "Default")
      (node (ref "C71") (pin "2") (pinfunction "P$2_2") (pintype "bidirectional"))
      (node (ref "IC2") (pin "45") (pinfunction "AINP8_45") (pintype "passive"))
      (node (ref "R27") (pin "2") (pinfunction "P$2_2") (pintype "bidirectional"))
    )
    (net (code "103") (name "M0_FAULT") (class "Default")
      (node (ref "CON57") (pin "27") (pinfunction "27_27") (pintype "bidirectional"))
      (node (ref "U9") (pin "P$2") (pinfunction "OT_P$2") (pintype "bidirectional"))
      (node (ref "U9") (pin "P$3") (pinfunction "FAULT_P$3") (pintype "bidirectional"))
    )
    (net (code "104") (name "M0_PWMA") (class "Default")
      (node (ref "CON57") (pin "28") (pinfunction "28_28") (pintype "bidirectional"))
      (node (ref "U9") (pin "P$4") (pinfunction "PWMA_P$4") (pintype "bidirectional"))
    )
    (net (code "105") (name "M0_PWMB") (class "Default")
      (node (ref "CON57") (pin "32") (pinfunction "32_32") (pintype "bidirectional"))
      (node (ref "U9") (pin "P$6") (pinfunction "PWMB_P$6") (pintype "bidirectional"))
    )
    (net (code "106") (name "M1_CS") (class "Default")
      (node (ref "C90") (pin "2") (pinfunction "P$2_2") (pintype "bidirectional"))
      (node (ref "IC2") (pin "47") (pinfunction "AINP7_47") (pintype "passive"))
      (node (ref "R34") (pin "2") (pinfunction "P$2_2") (pintype "bidirectional"))
    )
    (net (code "107") (name "M1_FAULT") (class "Default")
      (node (ref "CON57") (pin "24") (pinfunction "24_24") (pintype "bidirectional"))
      (node (ref "U14") (pin "P$2") (pinfunction "OT_P$2") (pintype "bidirectional"))
      (node (ref "U14") (pin "P$3") (pinfunction "FAULT_P$3") (pintype "bidirectional"))
    )
    (net (code "108") (name "M1_PWMA") (class "Default")
      (node (ref "CON57") (pin "25") (pinfunction "25_25") (pintype "bidirectional"))
      (node (ref "U14") (pin "P$4") (pinfunction "PWMA_P$4") (pintype "bidirectional"))
    )
    (net (code "109") (name "M1_PWMB") (class "Default")
      (node (ref "CON57") (pin "26") (pinfunction "26_26") (pintype "bidirectional"))
      (node (ref "U14") (pin "P$6") (pinfunction "PWMB_P$6") (pintype "bidirectional"))
    )
    (net (code "110") (name "M2_CS") (class "Default")
      (node (ref "C76") (pin "2") (pinfunction "P$2_2") (pintype "bidirectional"))
      (node (ref "IC2") (pin "49") (pinfunction "AINP6_49") (pintype "passive"))
      (node (ref "R31") (pin "2") (pinfunction "P$2_2") (pintype "bidirectional"))
    )
    (net (code "111") (name "M2_PWMA") (class "Default")
      (node (ref "CON58") (pin "19") (pinfunction "19_19") (pintype "bidirectional"))
      (node (ref "U10") (pin "P$14") (pinfunction "PWMC_P$14") (pintype "bidirectional"))
    )
    (net (code "112") (name "M2_PWMB") (class "Default")
      (node (ref "CON58") (pin "17") (pinfunction "17_17") (pintype "bidirectional"))
      (node (ref "U10") (pin "P$16") (pinfunction "PWMD_P$16") (pintype "bidirectional"))
    )
    (net (code "113") (name "M3_CS") (class "Default")
      (node (ref "C56") (pin "2") (pinfunction "P$2_2") (pintype "bidirectional"))
      (node (ref "IC2") (pin "51") (pinfunction "AINP5_51") (pintype "passive"))
      (node (ref "R21") (pin "2") (pinfunction "P$2_2") (pintype "bidirectional"))
    )
    (net (code "114") (name "M3_PWMA") (class "Default")
      (node (ref "CON58") (pin "23") (pinfunction "23_23") (pintype "bidirectional"))
      (node (ref "U10") (pin "P$4") (pinfunction "PWMA_P$4") (pintype "bidirectional"))
    )
    (net (code "115") (name "M3_PWMB") (class "Default")
      (node (ref "CON58") (pin "21") (pinfunction "21_21") (pintype "bidirectional"))
      (node (ref "U10") (pin "P$6") (pinfunction "PWMB_P$6") (pintype "bidirectional"))
    )
    (net (code "116") (name "M4_PWMA") (class "Default")
      (node (ref "CON58") (pin "31") (pinfunction "31_31") (pintype "bidirectional"))
      (node (ref "U11") (pin "P$14") (pinfunction "PWMC_P$14") (pintype "bidirectional"))
    )
    (net (code "117") (name "M4_PWMB") (class "Default")
      (node (ref "CON58") (pin "27") (pinfunction "27_27") (pintype "bidirectional"))
      (node (ref "U11") (pin "P$16") (pinfunction "PWMD_P$16") (pintype "bidirectional"))
    )
    (net (code "118") (name "M5_CS") (class "Default")
      (node (ref "C58") (pin "2") (pinfunction "P$2_2") (pintype "bidirectional"))
      (node (ref "IC2") (pin "61") (pinfunction "AINP4_61") (pintype "passive"))
      (node (ref "R22") (pin "2") (pinfunction "P$2_2") (pintype "bidirectional"))
    )
    (net (code "119") (name "M5_PWMA") (class "Default")
      (node (ref "CON58") (pin "35") (pinfunction "35_35") (pintype "bidirectional"))
      (node (ref "U11") (pin "P$4") (pinfunction "PWMA_P$4") (pintype "bidirectional"))
    )
    (net (code "120") (name "M5_PWMB") (class "Default")
      (node (ref "CON58") (pin "33") (pinfunction "33_33") (pintype "bidirectional"))
      (node (ref "U11") (pin "P$6") (pinfunction "PWMB_P$6") (pintype "bidirectional"))
    )
    (net (code "121") (name "M23_FAULT") (class "Default")
      (node (ref "CON58") (pin "25") (pinfunction "25_25") (pintype "bidirectional"))
      (node (ref "U10") (pin "P$2") (pinfunction "OT_P$2") (pintype "bidirectional"))
      (node (ref "U10") (pin "P$3") (pinfunction "FAULT_P$3") (pintype "bidirectional"))
    )
    (net (code "122") (name "M45_FAULT") (class "Default")
      (node (ref "CON58") (pin "37") (pinfunction "37_37") (pintype "bidirectional"))
      (node (ref "U11") (pin "P$2") (pinfunction "OT_P$2") (pintype "bidirectional"))
      (node (ref "U11") (pin "P$3") (pinfunction "FAULT_P$3") (pintype "bidirectional"))
    )
    (net (code "123") (name "MISO0") (class "Default")
      (node (ref "CON57") (pin "36") (pinfunction "36_36") (pintype "bidirectional"))
      (node (ref "U25") (pin "P$6") (pinfunction "A5_P$6") (pintype "bidirectional"))
    )
    (net (code "124") (name "MISO0°") (class "Default")
      (node (ref "CON40") (pin "5") (pinfunction "5_5") (pintype "bidirectional"))
      (node (ref "U25") (pin "P$15") (pinfunction "B5_P$15") (pintype "bidirectional"))
    )
    (net (code "125") (name "MISO1") (class "Default")
      (node (ref "CON58") (pin "20") (pinfunction "20_20") (pintype "bidirectional"))
      (node (ref "U32") (pin "P$1") (pinfunction "A1_P$1") (pintype "bidirectional"))
      (node (ref "U37") (pin "9") (pinfunction "AD0/SDO_9") (pintype "bidirectional"))
    )
    (net (code "126") (name "MISO1°") (class "Default")
      (node (ref "CON45") (pin "5") (pinfunction "5_5") (pintype "bidirectional"))
      (node (ref "U32") (pin "P$20") (pinfunction "B1_P$20") (pintype "bidirectional"))
    )
    (net (code "127") (name "MOSI0") (class "Default")
      (node (ref "CON57") (pin "35") (pinfunction "35_35") (pintype "bidirectional"))
      (node (ref "U25") (pin "P$7") (pinfunction "A6_P$7") (pintype "bidirectional"))
    )
    (net (code "128") (name "MOSI0°") (class "Default")
      (node (ref "CON40") (pin "4") (pinfunction "4_4") (pintype "bidirectional"))
      (node (ref "U25") (pin "P$14") (pinfunction "B6_P$14") (pintype "bidirectional"))
    )
    (net (code "129") (name "MOSI1") (class "Default")
      (node (ref "CON58") (pin "18") (pinfunction "18_18") (pintype "bidirectional"))
      (node (ref "U32") (pin "P$3") (pinfunction "A2_P$3") (pintype "bidirectional"))
      (node (ref "U37") (pin "24") (pinfunction "SDA/SDI_24") (pintype "bidirectional"))
    )
    (net (code "130") (name "MOSI1°") (class "Default")
      (node (ref "CON45") (pin "4") (pinfunction "4_4") (pintype "bidirectional"))
      (node (ref "U32") (pin "P$18") (pinfunction "B2_P$18") (pintype "bidirectional"))
    )
    (net (code "131") (name "Net-(C7-P$1)") (class "Default")
      (node (ref "C7") (pin "1") (pinfunction "P$1_1") (pintype "bidirectional"))
      (node (ref "R1") (pin "2") (pinfunction "P$2_2") (pintype "bidirectional"))
      (node (ref "R5") (pin "1") (pinfunction "P$1_1") (pintype "bidirectional"))
      (node (ref "U1") (pin "11") (pinfunction "X3_11") (pintype "bidirectional"))
    )
    (net (code "132") (name "Net-(C8-P$1)") (class "Default")
      (node (ref "C8") (pin "1") (pinfunction "P$1_1") (pintype "bidirectional"))
      (node (ref "R2") (pin "2") (pinfunction "P$2_2") (pintype "bidirectional"))
      (node (ref "R6") (pin "1") (pinfunction "P$1_1") (pintype "bidirectional"))
      (node (ref "U1") (pin "15") (pinfunction "X2_15") (pintype "bidirectional"))
    )
    (net (code "133") (name "Net-(C9-P$1)") (class "Default")
      (node (ref "C9") (pin "1") (pinfunction "P$1_1") (pintype "bidirectional"))
      (node (ref "R3") (pin "2") (pinfunction "P$2_2") (pintype "bidirectional"))
      (node (ref "R7") (pin "1") (pinfunction "P$1_1") (pintype "bidirectional"))
      (node (ref "U1") (pin "14") (pinfunction "X1_14") (pintype "bidirectional"))
    )
    (net (code "134") (name "Net-(C10-P$1)") (class "Default")
      (node (ref "C10") (pin "1") (pinfunction "P$1_1") (pintype "bidirectional"))
      (node (ref "R4") (pin "2") (pinfunction "P$2_2") (pintype "bidirectional"))
      (node (ref "R8") (pin "1") (pinfunction "P$1_1") (pintype "bidirectional"))
      (node (ref "U1") (pin "12") (pinfunction "X0_12") (pintype "bidirectional"))
    )
    (net (code "135") (name "Net-(C19-P$1)") (class "Default")
      (node (ref "C19") (pin "1") (pinfunction "P$1_1") (pintype "bidirectional"))
      (node (ref "U4") (pin "P$8") (pinfunction "SS_P$8") (pintype "bidirectional"))
    )
    (net (code "136") (name "Net-(C23-P$1)") (class "Default")
      (node (ref "C23") (pin "1") (pinfunction "P$1_1") (pintype "bidirectional"))
      (node (ref "U5") (pin "P$8") (pinfunction "SS_P$8") (pintype "bidirectional"))
    )
    (net (code "137") (name "Net-(C27-P$1)") (class "Default")
      (node (ref "C27") (pin "1") (pinfunction "P$1_1") (pintype "bidirectional"))
      (node (ref "U6") (pin "P$8") (pinfunction "SS_P$8") (pintype "bidirectional"))
    )
    (net (code "138") (name "Net-(C67-P$2)") (class "Default")
      (node (ref "C67") (pin "2") (pinfunction "P$2_2") (pintype "bidirectional"))
      (node (ref "J11") (pin "P$1") (pinfunction "1_P$1") (pintype "bidirectional"))
      (node (ref "J8") (pin "P$1") (pinfunction "1_P$1") (pintype "bidirectional"))
      (node (ref "J9") (pin "P$1") (pinfunction "1_P$1") (pintype "bidirectional"))
      (node (ref "U9") (pin "P$10") (pinfunction "VCAP_P$10") (pintype "bidirectional"))
    )
    (net (code "139") (name "Net-(C73-P$2)") (class "Default")
      (node (ref "C73") (pin "2") (pinfunction "P$2_2") (pintype "bidirectional"))
      (node (ref "J12") (pin "P$1") (pinfunction "1_P$1") (pintype "bidirectional"))
      (node (ref "J13") (pin "P$1") (pinfunction "1_P$1") (pintype "bidirectional"))
      (node (ref "U10") (pin "P$10") (pinfunction "VCAP_P$10") (pintype "bidirectional"))
    )
    (net (code "140") (name "Net-(C75-P$2)") (class "Default")
      (node (ref "C75") (pin "2") (pinfunction "P$2_2") (pintype "bidirectional"))
      (node (ref "J14") (pin "P$1") (pinfunction "1_P$1") (pintype "bidirectional"))
      (node (ref "J15") (pin "P$1") (pinfunction "1_P$1") (pintype "bidirectional"))
      (node (ref "U11") (pin "P$10") (pinfunction "VCAP_P$10") (pintype "bidirectional"))
    )
    (net (code "141") (name "Net-(C89-P$2)") (class "Default")
      (node (ref "C89") (pin "2") (pinfunction "P$2_2") (pintype "bidirectional"))
      (node (ref "J20") (pin "P$1") (pinfunction "1_P$1") (pintype "bidirectional"))
      (node (ref "J21") (pin "P$1") (pinfunction "1_P$1") (pintype "bidirectional"))
      (node (ref "J23") (pin "P$1") (pinfunction "1_P$1") (pintype "bidirectional"))
      (node (ref "U14") (pin "P$10") (pinfunction "VCAP_P$10") (pintype "bidirectional"))
    )
    (net (code "142") (name "Net-(C150-P$2)") (class "Default")
      (node (ref "C150") (pin "2") (pinfunction "P$2_2") (pintype "bidirectional"))
      (node (ref "Q1") (pin "1") (pinfunction "1_1") (pintype "bidirectional"))
      (node (ref "R90") (pin "2") (pinfunction "P$2_2") (pintype "bidirectional"))
      (node (ref "U20") (pin "61") (pinfunction "XI_61") (pintype "bidirectional"))
    )
    (net (code "143") (name "Net-(C151-P$2)") (class "Default")
      (node (ref "C151") (pin "2") (pinfunction "P$2_2") (pintype "bidirectional"))
      (node (ref "Q1") (pin "2") (pinfunction "2_2") (pintype "bidirectional"))
      (node (ref "R90") (pin "1") (pinfunction "P$1_1") (pintype "bidirectional"))
      (node (ref "U20") (pin "60") (pinfunction "XO_60") (pintype "bidirectional"))
    )
    (net (code "144") (name "Net-(C154-P$2)") (class "Default")
      (node (ref "C153") (pin "P$2") (pinfunction "P$2_P$2") (pintype "bidirectional"))
      (node (ref "C154") (pin "2") (pinfunction "P$2_2") (pintype "bidirectional"))
      (node (ref "C155") (pin "2") (pinfunction "P$2_2") (pintype "bidirectional"))
      (node (ref "U20") (pin "15") (pinfunction "VDD18CORE_15") (pintype "bidirectional"))
      (node (ref "U20") (pin "38") (pinfunction "VDD18CORE_38") (pintype "bidirectional"))
    )
    (net (code "145") (name "Net-(C156-P$2)") (class "Default")
      (node (ref "C156") (pin "2") (pinfunction "P$2_2") (pintype "bidirectional"))
      (node (ref "L10") (pin "1") (pinfunction "1_1") (pintype "bidirectional"))
      (node (ref "U20") (pin "48") (pinfunction "VDD18ETHPLL_48") (pintype "bidirectional"))
    )
    (net (code "146") (name "Net-(C157-P$2)") (class "Default")
      (node (ref "C157") (pin "2") (pinfunction "P$2_2") (pintype "bidirectional"))
      (node (ref "C158") (pin "P$2") (pinfunction "P$2_P$2") (pintype "bidirectional"))
      (node (ref "L10") (pin "2") (pinfunction "2_2") (pintype "bidirectional"))
      (node (ref "U20") (pin "62") (pinfunction "VDD18USBPLL_62") (pintype "bidirectional"))
    )
    (net (code "147") (name "Net-(C168-P$2)") (class "Default")
      (node (ref "C168") (pin "2") (pinfunction "P$2_2") (pintype "bidirectional"))
      (node (ref "IC1") (pin "8") (pinfunction "XTAL1_8") (pintype "passive"))
      (node (ref "Q2") (pin "P$1") (pinfunction "P1_P$1") (pintype "bidirectional"))
    )
    (net (code "148") (name "Net-(C169-P$2)") (class "Default")
      (node (ref "C169") (pin "2") (pinfunction "P$2_2") (pintype "bidirectional"))
      (node (ref "IC1") (pin "9") (pinfunction "XTAL2_9") (pintype "passive"))
      (node (ref "Q2") (pin "P$2") (pinfunction "P2_P$2") (pintype "bidirectional"))
    )
    (net (code "149") (name "Net-(C170-P$2)") (class "Default")
      (node (ref "C170") (pin "2") (pinfunction "P$2_2") (pintype "bidirectional"))
      (node (ref "IC1") (pin "7") (pinfunction "PLLCAP_7") (pintype "passive"))
    )
    (net (code "150") (name "Net-(C182-P$2)") (class "Default")
      (node (ref "C182") (pin "2") (pinfunction "P$2_2") (pintype "bidirectional"))
      (node (ref "J33") (pin "P$1") (pinfunction "1_P$1") (pintype "bidirectional"))
      (node (ref "J34") (pin "P$1") (pinfunction "1_P$1") (pintype "bidirectional"))
      (node (ref "U25") (pin "P$19") (pinfunction "VB_P$19") (pintype "bidirectional"))
    )
    (net (code "151") (name "Net-(C184-P$2)") (class "Default")
      (node (ref "C184") (pin "2") (pinfunction "P$2_2") (pintype "bidirectional"))
      (node (ref "J35") (pin "P$1") (pinfunction "1_P$1") (pintype "bidirectional"))
      (node (ref "J36") (pin "P$1") (pinfunction "1_P$1") (pintype "bidirectional"))
      (node (ref "U26") (pin "P$19") (pinfunction "VB_P$19") (pintype "bidirectional"))
    )
    (net (code "152") (name "Net-(C186-P$2)") (class "Default")
      (node (ref "C186") (pin "2") (pinfunction "P$2_2") (pintype "bidirectional"))
      (node (ref "J37") (pin "P$1") (pinfunction "1_P$1") (pintype "bidirectional"))
      (node (ref "J38") (pin "P$1") (pinfunction "1_P$1") (pintype "bidirectional"))
      (node (ref "U27") (pin "P$19") (pinfunction "VB_P$19") (pintype "bidirectional"))
    )
    (net (code "153") (name "Net-(C188-P$2)") (class "Default")
      (node (ref "C188") (pin "2") (pinfunction "P$2_2") (pintype "bidirectional"))
      (node (ref "J39") (pin "P$1") (pinfunction "1_P$1") (pintype "bidirectional"))
      (node (ref "J40") (pin "P$1") (pinfunction "1_P$1") (pintype "bidirectional"))
      (node (ref "U28") (pin "P$19") (pinfunction "VB_P$19") (pintype "bidirectional"))
    )
    (net (code "154") (name "Net-(C190-P$2)") (class "Default")
      (node (ref "C190") (pin "2") (pinfunction "P$2_2") (pintype "bidirectional"))
      (node (ref "J41") (pin "P$1") (pinfunction "1_P$1") (pintype "bidirectional"))
      (node (ref "J42") (pin "P$1") (pinfunction "1_P$1") (pintype "bidirectional"))
      (node (ref "U30") (pin "P$19") (pinfunction "VB_P$19") (pintype "bidirectional"))
    )
    (net (code "155") (name "Net-(C192-P$2)") (class "Default")
      (node (ref "C192") (pin "2") (pinfunction "P$2_2") (pintype "bidirectional"))
      (node (ref "J43") (pin "P$1") (pinfunction "1_P$1") (pintype "bidirectional"))
      (node (ref "J44") (pin "P$1") (pinfunction "1_P$1") (pintype "bidirectional"))
      (node (ref "U31") (pin "P$19") (pinfunction "VB_P$19") (pintype "bidirectional"))
    )
    (net (code "156") (name "Net-(C194-P$2)") (class "Default")
      (node (ref "C194") (pin "2") (pinfunction "P$2_2") (pintype "bidirectional"))
      (node (ref "J45") (pin "P$1") (pinfunction "1_P$1") (pintype "bidirectional"))
      (node (ref "J46") (pin "P$1") (pinfunction "1_P$1") (pintype "bidirectional"))
      (node (ref "U32") (pin "P$19") (pinfunction "VB_P$19") (pintype "bidirectional"))
    )
    (net (code "157") (name "Net-(C216-P$2)") (class "Default")
      (node (ref "C216") (pin "2") (pinfunction "P$2_2") (pintype "bidirectional"))
      (node (ref "C220") (pin "P$2") (pinfunction "P$2_P$2") (pintype "bidirectional"))
      (node (ref "U37") (pin "1") (pinfunction "VDDIO_1") (pintype "bidirectional"))
      (node (ref "U37") (pin "13") (pinfunction "VDD_13") (pintype "bidirectional"))
      (node (ref "U37") (pin "8") (pinfunction "VDDIO_8") (pintype "bidirectional"))
      (node (ref "U38") (pin "1") (pinfunction "VO_1") (pintype "bidirectional"))
    )
    (net (code "158") (name "Net-(C217-P$2)") (class "Default")
      (node (ref "C217") (pin "2") (pinfunction "P$2_2") (pintype "bidirectional"))
      (node (ref "U37") (pin "10") (pinfunction "REGOUT_10") (pintype "bidirectional"))
    )
    (net (code "159") (name "Net-(CON3-1)") (class "Default")
      (node (ref "CON3") (pin "P$1") (pinfunction "1_P$1") (pintype "bidirectional"))
      (node (ref "CON4") (pin "P$2") (pinfunction "2_P$2") (pintype "bidirectional"))
    )
    (net (code "160") (name "Net-(CON4-1)") (class "Default")
      (node (ref "CON4") (pin "P$1") (pinfunction "1_P$1") (pintype "bidirectional"))
      (node (ref "CON5") (pin "P$2") (pinfunction "2_P$2") (pintype "bidirectional"))
    )
    (net (code "161") (name "Net-(CON5-1)") (class "Default")
      (node (ref "CON5") (pin "P$1") (pinfunction "1_P$1") (pintype "bidirectional"))
      (node (ref "CON6") (pin "P$2") (pinfunction "2_P$2") (pintype "bidirectional"))
    )
    (net (code "162") (name "Net-(CON7-2)") (class "Default")
      (node (ref "C25") (pin "P$1") (pinfunction "P$1_P$1") (pintype "bidirectional"))
      (node (ref "C26") (pin "+") (pinfunction "+_+") (pintype "bidirectional"))
      (node (ref "CON7") (pin "P$2") (pinfunction "2_P$2") (pintype "bidirectional"))
      (node (ref "R19") (pin "1") (pinfunction "P$1_1") (pintype "bidirectional"))
      (node (ref "U6") (pin "P$4") (pinfunction "VO_P$4") (pintype "bidirectional"))
      (node (ref "U6") (pin "P$5") (pinfunction "VO_P$5") (pintype "bidirectional"))
    )
    (net (code "163") (name "Net-(CON8-1)") (class "Default")
      (node (ref "CON8") (pin "P$1") (pinfunction "1_P$1") (pintype "bidirectional"))
      (node (ref "L1") (pin "P$1") (pinfunction "1_P$1") (pintype "bidirectional"))
      (node (ref "L2") (pin "P$1") (pinfunction "1_P$1") (pintype "bidirectional"))
    )
    (net (code "164") (name "Net-(CON8-2)") (class "Default")
      (node (ref "CON8") (pin "P$2") (pinfunction "2_P$2") (pintype "bidirectional"))
      (node (ref "R24") (pin "P$2") (pinfunction "P$2_P$2") (pintype "bidirectional"))
      (node (ref "U12") (pin "P$2") (pinfunction "IN+_P$2") (pintype "bidirectional"))
    )
    (net (code "165") (name "Net-(CON9-1)") (class "Default")
      (node (ref "CON9") (pin "P$1") (pinfunction "1_P$1") (pintype "bidirectional"))
      (node (ref "R23") (pin "P$2") (pinfunction "P$2_P$2") (pintype "bidirectional"))
      (node (ref "U7") (pin "P$3") (pinfunction "IN-_P$3") (pintype "bidirectional"))
    )
    (net (code "166") (name "Net-(CON9-2)") (class "Default")
      (node (ref "C64") (pin "P$2") (pinfunction "P$2_P$2") (pintype "bidirectional"))
      (node (ref "CON9") (pin "P$2") (pinfunction "2_P$2") (pintype "bidirectional"))
      (node (ref "U10") (pin "P$30") (pinfunction "OUTB_P$30") (pintype "bidirectional"))
    )
    (net (code "167") (name "Net-(CON10-1)") (class "Default")
      (node (ref "CON10") (pin "P$1") (pinfunction "1_P$1") (pintype "bidirectional"))
      (node (ref "R25") (pin "P$2") (pinfunction "P$2_P$2") (pintype "bidirectional"))
      (node (ref "U8") (pin "P$3") (pinfunction "IN-_P$3") (pintype "bidirectional"))
    )
    (net (code "168") (name "Net-(CON10-2)") (class "Default")
      (node (ref "C66") (pin "P$2") (pinfunction "P$2_P$2") (pintype "bidirectional"))
      (node (ref "CON10") (pin "P$2") (pinfunction "2_P$2") (pintype "bidirectional"))
      (node (ref "U11") (pin "P$30") (pinfunction "OUTB_P$30") (pintype "bidirectional"))
    )
    (net (code "169") (name "Net-(CON11-1)") (class "Default")
      (node (ref "C68") (pin "P$2") (pinfunction "P$2_P$2") (pintype "bidirectional"))
      (node (ref "CON11") (pin "P$1") (pinfunction "1_P$1") (pintype "bidirectional"))
      (node (ref "U10") (pin "P$25") (pinfunction "OUTC_P$25") (pintype "bidirectional"))
    )
    (net (code "170") (name "Net-(CON11-2)") (class "Default")
      (node (ref "CON11") (pin "P$2") (pinfunction "2_P$2") (pintype "bidirectional"))
      (node (ref "R29") (pin "P$2") (pinfunction "P$2_P$2") (pintype "bidirectional"))
      (node (ref "U13") (pin "P$2") (pinfunction "IN+_P$2") (pintype "bidirectional"))
    )
    (net (code "171") (name "Net-(CON12-1)") (class "Default")
      (node (ref "C69") (pin "P$2") (pinfunction "P$2_P$2") (pintype "bidirectional"))
      (node (ref "CON12") (pin "P$1") (pinfunction "1_P$1") (pintype "bidirectional"))
      (node (ref "U11") (pin "P$25") (pinfunction "OUTC_P$25") (pintype "bidirectional"))
    )
    (net (code "172") (name "Net-(CON12-2)") (class "Default")
      (node (ref "C74") (pin "P$2") (pinfunction "P$2_P$2") (pintype "bidirectional"))
      (node (ref "CON12") (pin "P$2") (pinfunction "2_P$2") (pintype "bidirectional"))
      (node (ref "U11") (pin "P$22") (pinfunction "OUTD_P$22") (pintype "bidirectional"))
    )
    (net (code "173") (name "Net-(CON13-1)") (class "Default")
      (node (ref "CON13") (pin "P$1") (pinfunction "1_P$1") (pintype "bidirectional"))
      (node (ref "L5") (pin "P$1") (pinfunction "1_P$1") (pintype "bidirectional"))
      (node (ref "L6") (pin "P$1") (pinfunction "1_P$1") (pintype "bidirectional"))
    )
    (net (code "174") (name "Net-(CON13-2)") (class "Default")
      (node (ref "CON13") (pin "P$2") (pinfunction "2_P$2") (pintype "bidirectional"))
      (node (ref "R32") (pin "P$2") (pinfunction "P$2_P$2") (pintype "bidirectional"))
      (node (ref "U15") (pin "P$3") (pinfunction "IN-_P$3") (pintype "bidirectional"))
    )
    (net (code "175") (name "Net-(CON14-1)") (class "Default")
      (node (ref "CON14") (pin "P$1") (pinfunction "1_P$1") (pintype "bidirectional"))
      (node (ref "U17") (pin "V") (pinfunction "V_V") (pintype "bidirectional"))
    )
    (net (code "176") (name "Net-(CON14-2)") (class "Default")
      (node (ref "CON14") (pin "P$2") (pinfunction "2_P$2") (pintype "bidirectional"))
      (node (ref "K1") (pin "1") (pinfunction "NF_1") (pintype "bidirectional"))
      (node (ref "K2") (pin "12") (pinfunction "NO_12") (pintype "bidirectional"))
    )
    (net (code "177") (name "Net-(CON14-3)") (class "Default")
      (node (ref "CON14") (pin "P$3") (pinfunction "3_P$3") (pintype "bidirectional"))
      (node (ref "K1") (pin "12") (pinfunction "NO_12") (pintype "bidirectional"))
      (node (ref "K2") (pin "1") (pinfunction "NF_1") (pintype "bidirectional"))
    )
    (net (code "178") (name "Net-(CON17-1)") (class "Default")
      (node (ref "CON17") (pin "P$1") (pinfunction "1_P$1") (pintype "bidirectional"))
      (node (ref "U19") (pin "V") (pinfunction "V_V") (pintype "bidirectional"))
    )
    (net (code "179") (name "Net-(CON17-2)") (class "Default")
      (node (ref "CON17") (pin "P$2") (pinfunction "2_P$2") (pintype "bidirectional"))
      (node (ref "K3") (pin "1") (pinfunction "NF_1") (pintype "bidirectional"))
      (node (ref "K4") (pin "12") (pinfunction "NO_12") (pintype "bidirectional"))
    )
    (net (code "180") (name "Net-(CON17-3)") (class "Default")
      (node (ref "CON17") (pin "P$3") (pinfunction "3_P$3") (pintype "bidirectional"))
      (node (ref "K3") (pin "12") (pinfunction "NO_12") (pintype "bidirectional"))
      (node (ref "K4") (pin "1") (pinfunction "NF_1") (pintype "bidirectional"))
    )
    (net (code "181") (name "Net-(CON60-D+)") (class "Default")
      (node (ref "CON60") (pin "3") (pinfunction "D+_3") (pintype "bidirectional"))
      (node (ref "J49") (pin "P$1") (pinfunction "1_P$1") (pintype "bidirectional"))
    )
    (net (code "182") (name "Net-(CON60-D-)") (class "Default")
      (node (ref "CON60") (pin "2") (pinfunction "D-_2") (pintype "bidirectional"))
      (node (ref "J48") (pin "P$1") (pinfunction "1_P$1") (pintype "bidirectional"))
    )
    (net (code "183") (name "Net-(IC2-DVDD)") (class "Default")
      (node (ref "C166") (pin "P$2") (pinfunction "P$2_P$2") (pintype "bidirectional"))
      (node (ref "IC2") (pin "26") (pinfunction "DVDD_26") (pintype "passive"))
      (node (ref "U23") (pin "1") (pinfunction "VO_1") (pintype "bidirectional"))
    )
    (net (code "184") (name "Net-(IC2-MODE0)") (class "Default")
      (node (ref "IC2") (pin "34") (pinfunction "MODE0_34") (pintype "passive"))
      (node (ref "J28") (pin "P$1") (pinfunction "1_P$1") (pintype "bidirectional"))
      (node (ref "J29") (pin "P$2") (pinfunction "2_P$2") (pintype "bidirectional"))
    )
    (net (code "185") (name "Net-(IC2-VCOM)") (class "Default")
      (node (ref "IC2") (pin "55") (pinfunction "VCOM_55") (pintype "passive"))
      (node (ref "J30") (pin "P$2") (pinfunction "2_P$2") (pintype "bidirectional"))
    )
    (net (code "186") (name "Net-(IC3-TRIM)") (class "Default")
      (node (ref "C175") (pin "P$1") (pinfunction "P$1_P$1") (pintype "bidirectional"))
      (node (ref "IC3") (pin "5") (pinfunction "TRIM_5") (pintype "passive"))
    )
    (net (code "187") (name "Net-(IC3-VOUT)") (class "Default")
      (node (ref "IC3") (pin "6") (pinfunction "VOUT_6") (pintype "passive"))
      (node (ref "J31") (pin "P$1") (pinfunction "1_P$1") (pintype "bidirectional"))
    )
    (net (code "188") (name "Net-(IC4-TRIM)") (class "Default")
      (node (ref "C179") (pin "P$1") (pinfunction "P$1_P$1") (pintype "bidirectional"))
      (node (ref "IC4") (pin "5") (pinfunction "TRIM_5") (pintype "passive"))
    )
    (net (code "189") (name "Net-(IC4-VOUT)") (class "Default")
      (node (ref "IC4") (pin "6") (pinfunction "VOUT_6") (pintype "passive"))
      (node (ref "J32") (pin "P$1") (pinfunction "1_P$1") (pintype "bidirectional"))
    )
    (net (code "190") (name "Net-(J2-2)") (class "Default")
      (node (ref "J2") (pin "P$2") (pinfunction "2_P$2") (pintype "bidirectional"))
      (node (ref "J3") (pin "P$2") (pinfunction "2_P$2") (pintype "bidirectional"))
      (node (ref "U2") (pin "+") (pinfunction "+_+") (pintype "bidirectional"))
    )
    (net (code "191") (name "Net-(J4-2)") (class "Default")
      (node (ref "C42") (pin "P$2") (pinfunction "P$2_P$2") (pintype "bidirectional"))
      (node (ref "C43") (pin "P$2") (pinfunction "P$2_P$2") (pintype "bidirectional"))
      (node (ref "C44") (pin "P$2") (pinfunction "P$2_P$2") (pintype "bidirectional"))
      (node (ref "C45") (pin "P$2") (pinfunction "P$2_P$2") (pintype "bidirectional"))
      (node (ref "J4") (pin "P$2") (pinfunction "2_P$2") (pintype "bidirectional"))
      (node (ref "J5") (pin "P$2") (pinfunction "2_P$2") (pintype "bidirectional"))
      (node (ref "U10") (pin "P$21") (pinfunction "VDDD_P$21") (pintype "bidirectional"))
      (node (ref "U10") (pin "P$26") (pinfunction "VDDC_P$26") (pintype "bidirectional"))
      (node (ref "U10") (pin "P$29") (pinfunction "VDDB_P$29") (pintype "bidirectional"))
      (node (ref "U10") (pin "P$34") (pinfunction "VDDA_P$34") (pintype "bidirectional"))
    )
    (net (code "192") (name "Net-(J6-2)") (class "Default")
      (node (ref "C51") (pin "P$2") (pinfunction "P$2_P$2") (pintype "bidirectional"))
      (node (ref "C52") (pin "P$2") (pinfunction "P$2_P$2") (pintype "bidirectional"))
      (node (ref "C53") (pin "P$2") (pinfunction "P$2_P$2") (pintype "bidirectional"))
      (node (ref "C54") (pin "P$2") (pinfunction "P$2_P$2") (pintype "bidirectional"))
      (node (ref "J6") (pin "P$2") (pinfunction "2_P$2") (pintype "bidirectional"))
      (node (ref "J7") (pin "P$2") (pinfunction "2_P$2") (pintype "bidirectional"))
      (node (ref "U11") (pin "P$21") (pinfunction "VDDD_P$21") (pintype "bidirectional"))
      (node (ref "U11") (pin "P$26") (pinfunction "VDDC_P$26") (pintype "bidirectional"))
      (node (ref "U11") (pin "P$29") (pinfunction "VDDB_P$29") (pintype "bidirectional"))
      (node (ref "U11") (pin "P$34") (pinfunction "VDDA_P$34") (pintype "bidirectional"))
    )
    (net (code "193") (name "Net-(J8-2)") (class "Default")
      (node (ref "J8") (pin "P$2") (pinfunction "2_P$2") (pintype "bidirectional"))
      (node (ref "U9") (pin "P$5") (pinfunction "RST_AB_P$5") (pintype "bidirectional"))
    )
    (net (code "194") (name "Net-(J9-2)") (class "Default")
      (node (ref "J9") (pin "P$2") (pinfunction "2_P$2") (pintype "bidirectional"))
      (node (ref "U9") (pin "P$15") (pinfunction "RST_CD_P$15") (pintype "bidirectional"))
    )
    (net (code "195") (name "Net-(J10-2)") (class "Default")
      (node (ref "J10") (pin "P$2") (pinfunction "2_P$2") (pintype "bidirectional"))
      (node (ref "U9") (pin "P$13") (pinfunction "M1_P$13") (pintype "bidirectional"))
    )
    (net (code "196") (name "Net-(J11-2)") (class "Default")
      (node (ref "J11") (pin "P$2") (pinfunction "2_P$2") (pintype "bidirectional"))
      (node (ref "U9") (pin "P$12") (pinfunction "M2_P$12") (pintype "bidirectional"))
    )
    (net (code "197") (name "Net-(J12-2)") (class "Default")
      (node (ref "J12") (pin "P$2") (pinfunction "2_P$2") (pintype "bidirectional"))
      (node (ref "U10") (pin "P$5") (pinfunction "RST_AB_P$5") (pintype "bidirectional"))
    )
    (net (code "198") (name "Net-(J13-2)") (class "Default")
      (node (ref "J13") (pin "P$2") (pinfunction "2_P$2") (pintype "bidirectional"))
      (node (ref "U10") (pin "P$15") (pinfunction "RST_CD_P$15") (pintype "bidirectional"))
    )
    (net (code "199") (name "Net-(J14-2)") (class "Default")
      (node (ref "J14") (pin "P$2") (pinfunction "2_P$2") (pintype "bidirectional"))
      (node (ref "U11") (pin "P$5") (pinfunction "RST_AB_P$5") (pintype "bidirectional"))
    )
    (net (code "200") (name "Net-(J15-2)") (class "Default")
      (node (ref "J15") (pin "P$2") (pinfunction "2_P$2") (pintype "bidirectional"))
      (node (ref "U11") (pin "P$15") (pinfunction "RST_CD_P$15") (pintype "bidirectional"))
    )
    (net (code "201") (name "Net-(J16-2)") (class "Default")
      (node (ref "J16") (pin "P$2") (pinfunction "2_P$2") (pintype "bidirectional"))
      (node (ref "U10") (pin "P$13") (pinfunction "M1_P$13") (pintype "bidirectional"))
    )
    (net (code "202") (name "Net-(J17-2)") (class "Default")
      (node (ref "J17") (pin "P$2") (pinfunction "2_P$2") (pintype "bidirectional"))
      (node (ref "U10") (pin "P$12") (pinfunction "M2_P$12") (pintype "bidirectional"))
    )
    (net (code "203") (name "Net-(J18-2)") (class "Default")
      (node (ref "J18") (pin "P$2") (pinfunction "2_P$2") (pintype "bidirectional"))
      (node (ref "U11") (pin "P$13") (pinfunction "M1_P$13") (pintype "bidirectional"))
    )
    (net (code "204") (name "Net-(J19-2)") (class "Default")
      (node (ref "J19") (pin "P$2") (pinfunction "2_P$2") (pintype "bidirectional"))
      (node (ref "U11") (pin "P$12") (pinfunction "M2_P$12") (pintype "bidirectional"))
    )
    (net (code "205") (name "Net-(J20-2)") (class "Default")
      (node (ref "J20") (pin "P$2") (pinfunction "2_P$2") (pintype "bidirectional"))
      (node (ref "U14") (pin "P$5") (pinfunction "RST_AB_P$5") (pintype "bidirectional"))
    )
    (net (code "206") (name "Net-(J21-2)") (class "Default")
      (node (ref "J21") (pin "P$2") (pinfunction "2_P$2") (pintype "bidirectional"))
      (node (ref "U14") (pin "P$15") (pinfunction "RST_CD_P$15") (pintype "bidirectional"))
    )
    (net (code "207") (name "Net-(J22-2)") (class "Default")
      (node (ref "J22") (pin "P$2") (pinfunction "2_P$2") (pintype "bidirectional"))
      (node (ref "U14") (pin "P$13") (pinfunction "M1_P$13") (pintype "bidirectional"))
    )
    (net (code "208") (name "Net-(J23-2)") (class "Default")
      (node (ref "J23") (pin "P$2") (pinfunction "2_P$2") (pintype "bidirectional"))
      (node (ref "U14") (pin "P$12") (pinfunction "M2_P$12") (pintype "bidirectional"))
    )
    (net (code "209") (name "Net-(J26-2)") (class "Default")
      (node (ref "J26") (pin "P$2") (pinfunction "2_P$2") (pintype "bidirectional"))
      (node (ref "U17") (pin "VCC") (pinfunction "VCC_VCC") (pintype "bidirectional"))
    )
    (net (code "210") (name "Net-(J27-2)") (class "Default")
      (node (ref "J27") (pin "P$2") (pinfunction "2_P$2") (pintype "bidirectional"))
      (node (ref "U19") (pin "VCC") (pinfunction "VCC_VCC") (pintype "bidirectional"))
    )
    (net (code "211") (name "Net-(J50-2)") (class "Default")
      (node (ref "J50") (pin "P$2") (pinfunction "2_P$2") (pintype "bidirectional"))
      (node (ref "J51") (pin "P$1") (pinfunction "1_P$1") (pintype "bidirectional"))
      (node (ref "U37") (pin "11") (pinfunction "FSYNC_11") (pintype "bidirectional"))
    )
    (net (code "212") (name "Net-(K1-COM-Pad6)") (class "Default")
      (node (ref "K1") (pin "6") (pinfunction "COM_6") (pintype "bidirectional"))
      (node (ref "K1") (pin "7") (pinfunction "COM_7") (pintype "bidirectional"))
      (node (ref "U17") (pin "U") (pinfunction "U_U") (pintype "bidirectional"))
    )
    (net (code "213") (name "Net-(K2-COM-Pad6)") (class "Default")
      (node (ref "K2") (pin "6") (pinfunction "COM_6") (pintype "bidirectional"))
      (node (ref "K2") (pin "7") (pinfunction "COM_7") (pintype "bidirectional"))
      (node (ref "U17") (pin "W") (pinfunction "W_W") (pintype "bidirectional"))
    )
    (net (code "214") (name "Net-(K3-COM-Pad6)") (class "Default")
      (node (ref "K3") (pin "6") (pinfunction "COM_6") (pintype "bidirectional"))
      (node (ref "K3") (pin "7") (pinfunction "COM_7") (pintype "bidirectional"))
      (node (ref "U19") (pin "U") (pinfunction "U_U") (pintype "bidirectional"))
    )
    (net (code "215") (name "Net-(K4-COM-Pad6)") (class "Default")
      (node (ref "K4") (pin "6") (pinfunction "COM_6") (pintype "bidirectional"))
      (node (ref "K4") (pin "7") (pinfunction "COM_7") (pintype "bidirectional"))
      (node (ref "U19") (pin "W") (pinfunction "W_W") (pintype "bidirectional"))
    )
    (net (code "216") (name "Net-(L1-2)") (class "Default")
      (node (ref "C55") (pin "P$2") (pinfunction "P$2_P$2") (pintype "bidirectional"))
      (node (ref "L1") (pin "P$2") (pinfunction "2_P$2") (pintype "bidirectional"))
      (node (ref "U9") (pin "P$33") (pinfunction "OUTA_P$33") (pintype "bidirectional"))
    )
    (net (code "217") (name "Net-(L2-2)") (class "Default")
      (node (ref "C60") (pin "P$2") (pinfunction "P$2_P$2") (pintype "bidirectional"))
      (node (ref "L2") (pin "P$2") (pinfunction "2_P$2") (pintype "bidirectional"))
      (node (ref "U9") (pin "P$30") (pinfunction "OUTB_P$30") (pintype "bidirectional"))
    )
    (net (code "218") (name "Net-(L3-1)") (class "Default")
      (node (ref "L3") (pin "P$1") (pinfunction "1_P$1") (pintype "bidirectional"))
      (node (ref "L4") (pin "P$1") (pinfunction "1_P$1") (pintype "bidirectional"))
      (node (ref "R24") (pin "P$1") (pinfunction "P$1_P$1") (pintype "bidirectional"))
      (node (ref "U12") (pin "P$3") (pinfunction "IN-_P$3") (pintype "bidirectional"))
    )
    (net (code "219") (name "Net-(L3-2)") (class "Default")
      (node (ref "C62") (pin "P$2") (pinfunction "P$2_P$2") (pintype "bidirectional"))
      (node (ref "L3") (pin "P$2") (pinfunction "2_P$2") (pintype "bidirectional"))
      (node (ref "U9") (pin "P$25") (pinfunction "OUTC_P$25") (pintype "bidirectional"))
    )
    (net (code "220") (name "Net-(L4-2)") (class "Default")
      (node (ref "C65") (pin "P$2") (pinfunction "P$2_P$2") (pintype "bidirectional"))
      (node (ref "L4") (pin "P$2") (pinfunction "2_P$2") (pintype "bidirectional"))
      (node (ref "U9") (pin "P$22") (pinfunction "OUTD_P$22") (pintype "bidirectional"))
    )
    (net (code "221") (name "Net-(L5-2)") (class "Default")
      (node (ref "C85") (pin "P$2") (pinfunction "P$2_P$2") (pintype "bidirectional"))
      (node (ref "L5") (pin "P$2") (pinfunction "2_P$2") (pintype "bidirectional"))
      (node (ref "U14") (pin "P$33") (pinfunction "OUTA_P$33") (pintype "bidirectional"))
    )
    (net (code "222") (name "Net-(L6-2)") (class "Default")
      (node (ref "C86") (pin "P$2") (pinfunction "P$2_P$2") (pintype "bidirectional"))
      (node (ref "L6") (pin "P$2") (pinfunction "2_P$2") (pintype "bidirectional"))
      (node (ref "U14") (pin "P$30") (pinfunction "OUTB_P$30") (pintype "bidirectional"))
    )
    (net (code "223") (name "Net-(L7-1)") (class "Default")
      (node (ref "L7") (pin "P$1") (pinfunction "1_P$1") (pintype "bidirectional"))
      (node (ref "L8") (pin "P$1") (pinfunction "1_P$1") (pintype "bidirectional"))
      (node (ref "R32") (pin "P$1") (pinfunction "P$1_P$1") (pintype "bidirectional"))
      (node (ref "U15") (pin "P$2") (pinfunction "IN+_P$2") (pintype "bidirectional"))
    )
    (net (code "224") (name "Net-(L7-2)") (class "Default")
      (node (ref "C87") (pin "P$2") (pinfunction "P$2_P$2") (pintype "bidirectional"))
      (node (ref "L7") (pin "P$2") (pinfunction "2_P$2") (pintype "bidirectional"))
      (node (ref "U14") (pin "P$25") (pinfunction "OUTC_P$25") (pintype "bidirectional"))
    )
    (net (code "225") (name "Net-(L8-2)") (class "Default")
      (node (ref "C88") (pin "P$2") (pinfunction "P$2_P$2") (pintype "bidirectional"))
      (node (ref "L8") (pin "P$2") (pinfunction "2_P$2") (pintype "bidirectional"))
      (node (ref "U14") (pin "P$22") (pinfunction "OUTD_P$22") (pintype "bidirectional"))
    )
    (net (code "226") (name "Net-(R9-P$1)") (class "Default")
      (node (ref "R9") (pin "1") (pinfunction "P$1_1") (pintype "bidirectional"))
      (node (ref "U3") (pin "P$5") (pinfunction "RSET_P$5") (pintype "bidirectional"))
    )
    (net (code "227") (name "Net-(R10-P$2)") (class "Default")
      (node (ref "D4") (pin "A") (pinfunction "A_A") (pintype "bidirectional"))
      (node (ref "R10") (pin "2") (pinfunction "P$2_2") (pintype "bidirectional"))
    )
    (net (code "228") (name "Net-(R11-P$2)") (class "Default")
      (node (ref "D5") (pin "A") (pinfunction "A_A") (pintype "bidirectional"))
      (node (ref "R11") (pin "2") (pinfunction "P$2_2") (pintype "bidirectional"))
    )
    (net (code "229") (name "Net-(R12-P$2)") (class "Default")
      (node (ref "D6") (pin "A") (pinfunction "A_A") (pintype "bidirectional"))
      (node (ref "R12") (pin "2") (pinfunction "P$2_2") (pintype "bidirectional"))
    )
    (net (code "230") (name "Net-(R13-P$2)") (class "Default")
      (node (ref "D7") (pin "A") (pinfunction "A_A") (pintype "bidirectional"))
      (node (ref "R13") (pin "2") (pinfunction "P$2_2") (pintype "bidirectional"))
    )
    (net (code "231") (name "Net-(R14-P$2)") (class "Default")
      (node (ref "D8") (pin "A") (pinfunction "A_A") (pintype "bidirectional"))
      (node (ref "R14") (pin "2") (pinfunction "P$2_2") (pintype "bidirectional"))
    )
    (net (code "232") (name "Net-(R15-P$2)") (class "Default")
      (node (ref "R15") (pin "2") (pinfunction "P$2_2") (pintype "bidirectional"))
      (node (ref "R16") (pin "1") (pinfunction "P$1_1") (pintype "bidirectional"))
      (node (ref "U4") (pin "P$6") (pinfunction "ADJ_P$6") (pintype "bidirectional"))
    )
    (net (code "233") (name "Net-(R17-P$2)") (class "Default")
      (node (ref "R17") (pin "2") (pinfunction "P$2_2") (pintype "bidirectional"))
      (node (ref "R18") (pin "1") (pinfunction "P$1_1") (pintype "bidirectional"))
      (node (ref "U5") (pin "P$6") (pinfunction "ADJ_P$6") (pintype "bidirectional"))
    )
    (net (code "234") (name "Net-(R19-P$2)") (class "Default")
      (node (ref "R19") (pin "2") (pinfunction "P$2_2") (pintype "bidirectional"))
      (node (ref "R20") (pin "1") (pinfunction "P$1_1") (pintype "bidirectional"))
      (node (ref "U6") (pin "P$6") (pinfunction "ADJ_P$6") (pintype "bidirectional"))
    )
    (net (code "235") (name "Net-(R21-P$1)") (class "Default")
      (node (ref "R21") (pin "1") (pinfunction "P$1_1") (pintype "bidirectional"))
      (node (ref "U7") (pin "P$8") (pinfunction "OUT_P$8") (pintype "bidirectional"))
    )
    (net (code "236") (name "Net-(R22-P$1)") (class "Default")
      (node (ref "R22") (pin "1") (pinfunction "P$1_1") (pintype "bidirectional"))
      (node (ref "U8") (pin "P$8") (pinfunction "OUT_P$8") (pintype "bidirectional"))
    )
    (net (code "237") (name "Net-(R26-P$1)") (class "Default")
      (node (ref "R26") (pin "1") (pinfunction "P$1_1") (pintype "bidirectional"))
      (node (ref "U9") (pin "P$7") (pinfunction "OC_ADJ_P$7") (pintype "bidirectional"))
    )
    (net (code "238") (name "Net-(R27-P$1)") (class "Default")
      (node (ref "R27") (pin "1") (pinfunction "P$1_1") (pintype "bidirectional"))
      (node (ref "U12") (pin "P$8") (pinfunction "OUT_P$8") (pintype "bidirectional"))
    )
    (net (code "239") (name "Net-(R28-P$1)") (class "Default")
      (node (ref "R28") (pin "1") (pinfunction "P$1_1") (pintype "bidirectional"))
      (node (ref "U10") (pin "P$7") (pinfunction "OC_ADJ_P$7") (pintype "bidirectional"))
    )
    (net (code "240") (name "Net-(R30-P$1)") (class "Default")
      (node (ref "R30") (pin "1") (pinfunction "P$1_1") (pintype "bidirectional"))
      (node (ref "U11") (pin "P$7") (pinfunction "OC_ADJ_P$7") (pintype "bidirectional"))
    )
    (net (code "241") (name "Net-(R31-P$1)") (class "Default")
      (node (ref "R31") (pin "1") (pinfunction "P$1_1") (pintype "bidirectional"))
      (node (ref "U13") (pin "P$8") (pinfunction "OUT_P$8") (pintype "bidirectional"))
    )
    (net (code "242") (name "Net-(R33-P$1)") (class "Default")
      (node (ref "R33") (pin "1") (pinfunction "P$1_1") (pintype "bidirectional"))
      (node (ref "U14") (pin "P$7") (pinfunction "OC_ADJ_P$7") (pintype "bidirectional"))
    )
    (net (code "243") (name "Net-(R34-P$1)") (class "Default")
      (node (ref "R34") (pin "1") (pinfunction "P$1_1") (pintype "bidirectional"))
      (node (ref "U15") (pin "P$8") (pinfunction "OUT_P$8") (pintype "bidirectional"))
    )
    (net (code "244") (name "Net-(R35-P$1)") (class "Default")
      (node (ref "R35") (pin "1") (pinfunction "P$1_1") (pintype "bidirectional"))
      (node (ref "U16") (pin "P$8") (pinfunction "OUT_P$8") (pintype "bidirectional"))
    )
    (net (code "245") (name "Net-(R37-P$1)") (class "Default")
      (node (ref "R37") (pin "1") (pinfunction "P$1_1") (pintype "bidirectional"))
      (node (ref "U18") (pin "P$8") (pinfunction "OUT_P$8") (pintype "bidirectional"))
    )
    (net (code "246") (name "Net-(R41-P$1)") (class "Default")
      (node (ref "CON20") (pin "3") (pinfunction "3_3") (pintype "bidirectional"))
      (node (ref "R41") (pin "1") (pinfunction "P$1_1") (pintype "bidirectional"))
    )
    (net (code "247") (name "Net-(R42-P$1)") (class "Default")
      (node (ref "CON22") (pin "3") (pinfunction "3_3") (pintype "bidirectional"))
      (node (ref "R42") (pin "1") (pinfunction "P$1_1") (pintype "bidirectional"))
    )
    (net (code "248") (name "Net-(R44-P$2)") (class "Default")
      (node (ref "CON21") (pin "1") (pinfunction "1_1") (pintype "bidirectional"))
      (node (ref "R44") (pin "2") (pinfunction "P$2_2") (pintype "bidirectional"))
      (node (ref "R45") (pin "P$1") (pinfunction "P$1_P$1") (pintype "bidirectional"))
    )
    (net (code "249") (name "Net-(R46-P$1)") (class "Default")
      (node (ref "CON23") (pin "3") (pinfunction "3_3") (pintype "bidirectional"))
      (node (ref "R46") (pin "1") (pinfunction "P$1_1") (pintype "bidirectional"))
    )
    (net (code "250") (name "Net-(R47-P$1)") (class "Default")
      (node (ref "CON25") (pin "3") (pinfunction "3_3") (pintype "bidirectional"))
      (node (ref "R47") (pin "1") (pinfunction "P$1_1") (pintype "bidirectional"))
    )
    (net (code "251") (name "Net-(R49-P$2)") (class "Default")
      (node (ref "CON24") (pin "1") (pinfunction "1_1") (pintype "bidirectional"))
      (node (ref "R49") (pin "2") (pinfunction "P$2_2") (pintype "bidirectional"))
      (node (ref "R52") (pin "P$1") (pinfunction "P$1_P$1") (pintype "bidirectional"))
    )
    (net (code "252") (name "Net-(R53-P$1)") (class "Default")
      (node (ref "CON28") (pin "3") (pinfunction "3_3") (pintype "bidirectional"))
      (node (ref "R53") (pin "1") (pinfunction "P$1_1") (pintype "bidirectional"))
    )
    (net (code "253") (name "Net-(R54-P$1)") (class "Default")
      (node (ref "CON30") (pin "3") (pinfunction "3_3") (pintype "bidirectional"))
      (node (ref "R54") (pin "1") (pinfunction "P$1_1") (pintype "bidirectional"))
    )
    (net (code "254") (name "Net-(R56-P$2)") (class "Default")
      (node (ref "CON29") (pin "1") (pinfunction "1_1") (pintype "bidirectional"))
      (node (ref "R56") (pin "2") (pinfunction "P$2_2") (pintype "bidirectional"))
      (node (ref "R57") (pin "P$1") (pinfunction "P$1_P$1") (pintype "bidirectional"))
    )
    (net (code "255") (name "Net-(R58-P$2)") (class "Default")
      (node (ref "CON32") (pin "4") (pinfunction "4_4") (pintype "bidirectional"))
      (node (ref "R58") (pin "2") (pinfunction "P$2_2") (pintype "bidirectional"))
    )
    (net (code "256") (name "Net-(R59-P$1)") (class "Default")
      (node (ref "CON33") (pin "3") (pinfunction "3_3") (pintype "bidirectional"))
      (node (ref "R59") (pin "1") (pinfunction "P$1_1") (pintype "bidirectional"))
    )
    (net (code "257") (name "Net-(R60-P$1)") (class "Default")
      (node (ref "CON35") (pin "3") (pinfunction "3_3") (pintype "bidirectional"))
      (node (ref "R60") (pin "1") (pinfunction "P$1_1") (pintype "bidirectional"))
    )
    (net (code "258") (name "Net-(R61-P$2)") (class "Default")
      (node (ref "CON32") (pin "3") (pinfunction "3_3") (pintype "bidirectional"))
      (node (ref "R61") (pin "2") (pinfunction "P$2_2") (pintype "bidirectional"))
    )
    (net (code "259") (name "Net-(R62-P$2)") (class "Default")
      (node (ref "CON32") (pin "2") (pinfunction "2_2") (pintype "bidirectional"))
      (node (ref "R62") (pin "2") (pinfunction "P$2_2") (pintype "bidirectional"))
    )
    (net (code "260") (name "Net-(R64-P$2)") (class "Default")
      (node (ref "CON34") (pin "1") (pinfunction "1_1") (pintype "bidirectional"))
      (node (ref "R64") (pin "2") (pinfunction "P$2_2") (pintype "bidirectional"))
      (node (ref "R65") (pin "P$1") (pinfunction "P$1_P$1") (pintype "bidirectional"))
    )
    (net (code "261") (name "Net-(R66-P$1)") (class "Default")
      (node (ref "CON37") (pin "3") (pinfunction "3_3") (pintype "bidirectional"))
      (node (ref "R66") (pin "1") (pinfunction "P$1_1") (pintype "bidirectional"))
    )
    (net (code "262") (name "Net-(R67-P$1)") (class "Default")
      (node (ref "CON39") (pin "3") (pinfunction "3_3") (pintype "bidirectional"))
      (node (ref "R67") (pin "1") (pinfunction "P$1_1") (pintype "bidirectional"))
    )
    (net (code "263") (name "Net-(R69-P$2)") (class "Default")
      (node (ref "CON38") (pin "1") (pinfunction "1_1") (pintype "bidirectional"))
      (node (ref "R69") (pin "2") (pinfunction "P$2_2") (pintype "bidirectional"))
      (node (ref "R70") (pin "P$1") (pinfunction "P$1_P$1") (pintype "bidirectional"))
    )
    (net (code "264") (name "Net-(R71-P$2)") (class "Default")
      (node (ref "CON41") (pin "4") (pinfunction "4_4") (pintype "bidirectional"))
      (node (ref "R71") (pin "2") (pinfunction "P$2_2") (pintype "bidirectional"))
    )
    (net (code "265") (name "Net-(R72-P$2)") (class "Default")
      (node (ref "CON41") (pin "3") (pinfunction "3_3") (pintype "bidirectional"))
      (node (ref "R72") (pin "2") (pinfunction "P$2_2") (pintype "bidirectional"))
    )
    (net (code "266") (name "Net-(R73-P$2)") (class "Default")
      (node (ref "CON41") (pin "2") (pinfunction "2_2") (pintype "bidirectional"))
      (node (ref "R73") (pin "2") (pinfunction "P$2_2") (pintype "bidirectional"))
    )
    (net (code "267") (name "Net-(R74-P$1)") (class "Default")
      (node (ref "CON42") (pin "3") (pinfunction "3_3") (pintype "bidirectional"))
      (node (ref "R74") (pin "1") (pinfunction "P$1_1") (pintype "bidirectional"))
    )
    (net (code "268") (name "Net-(R75-P$1)") (class "Default")
      (node (ref "CON44") (pin "3") (pinfunction "3_3") (pintype "bidirectional"))
      (node (ref "R75") (pin "1") (pinfunction "P$1_1") (pintype "bidirectional"))
    )
    (net (code "269") (name "Net-(R77-P$2)") (class "Default")
      (node (ref "CON43") (pin "1") (pinfunction "1_1") (pintype "bidirectional"))
      (node (ref "R77") (pin "2") (pinfunction "P$2_2") (pintype "bidirectional"))
      (node (ref "R78") (pin "P$1") (pinfunction "P$1_P$1") (pintype "bidirectional"))
    )
    (net (code "270") (name "Net-(R79-P$1)") (class "Default")
      (node (ref "CON46") (pin "3") (pinfunction "3_3") (pintype "bidirectional"))
      (node (ref "R79") (pin "1") (pinfunction "P$1_1") (pintype "bidirectional"))
    )
    (net (code "271") (name "Net-(R80-P$1)") (class "Default")
      (node (ref "CON48") (pin "3") (pinfunction "3_3") (pintype "bidirectional"))
      (node (ref "R80") (pin "1") (pinfunction "P$1_1") (pintype "bidirectional"))
    )
    (net (code "272") (name "Net-(R82-P$2)") (class "Default")
      (node (ref "CON47") (pin "1") (pinfunction "1_1") (pintype "bidirectional"))
      (node (ref "R82") (pin "2") (pinfunction "P$2_2") (pintype "bidirectional"))
      (node (ref "R83") (pin "P$1") (pinfunction "P$1_P$1") (pintype "bidirectional"))
    )
    (net (code "273") (name "Net-(R84-P$1)") (class "Default")
      (node (ref "CON50") (pin "3") (pinfunction "3_3") (pintype "bidirectional"))
      (node (ref "R84") (pin "1") (pinfunction "P$1_1") (pintype "bidirectional"))
    )
    (net (code "274") (name "Net-(R85-P$1)") (class "Default")
      (node (ref "CON52") (pin "3") (pinfunction "3_3") (pintype "bidirectional"))
      (node (ref "R85") (pin "1") (pinfunction "P$1_1") (pintype "bidirectional"))
    )
    (net (code "275") (name "Net-(R87-P$2)") (class "Default")
      (node (ref "CON51") (pin "1") (pinfunction "1_1") (pintype "bidirectional"))
      (node (ref "R87") (pin "2") (pinfunction "P$2_2") (pintype "bidirectional"))
      (node (ref "R88") (pin "P$1") (pinfunction "P$1_P$1") (pintype "bidirectional"))
    )
    (net (code "276") (name "Net-(R89-P$1)") (class "Default")
      (node (ref "R89") (pin "1") (pinfunction "P$1_1") (pintype "bidirectional"))
      (node (ref "U20") (pin "12") (pinfunction "NRESET_12") (pintype "bidirectional"))
    )
    (net (code "277") (name "Net-(R91-P$1)") (class "Default")
      (node (ref "R91") (pin "1") (pinfunction "P$1_1") (pintype "bidirectional"))
      (node (ref "U21") (pin "P$2") (pinfunction "GPIO2_P$2") (pintype "bidirectional"))
    )
    (net (code "278") (name "Net-(R92-P$1)") (class "Default")
      (node (ref "R92") (pin "1") (pinfunction "P$1_1") (pintype "bidirectional"))
      (node (ref "U21") (pin "P$3") (pinfunction "GPIO9_P$3") (pintype "bidirectional"))
    )
    (net (code "279") (name "Net-(R92-P$2)") (class "Default")
      (node (ref "D9") (pin "C") (pinfunction "C_C") (pintype "bidirectional"))
      (node (ref "R92") (pin "2") (pinfunction "P$2_2") (pintype "bidirectional"))
    )
    (net (code "280") (name "Net-(R93-P$1)") (class "Default")
      (node (ref "R93") (pin "1") (pinfunction "P$1_1") (pintype "bidirectional"))
      (node (ref "U22") (pin "P$2") (pinfunction "GPIO2_P$2") (pintype "bidirectional"))
    )
    (net (code "281") (name "Net-(R94-P$1)") (class "Default")
      (node (ref "R94") (pin "1") (pinfunction "P$1_1") (pintype "bidirectional"))
      (node (ref "U22") (pin "P$3") (pinfunction "GPIO9_P$3") (pintype "bidirectional"))
    )
    (net (code "282") (name "Net-(R94-P$2)") (class "Default")
      (node (ref "D10") (pin "C") (pinfunction "C_C") (pintype "bidirectional"))
      (node (ref "R94") (pin "2") (pinfunction "P$2_2") (pintype "bidirectional"))
    )
    (net (code "283") (name "Net-(R95-P$2)") (class "Default")
      (node (ref "R95") (pin "2") (pinfunction "P$2_2") (pintype "bidirectional"))
      (node (ref "U20") (pin "50") (pinfunction "EXRES_50") (pintype "bidirectional"))
    )
    (net (code "284") (name "Net-(R96-P$2)") (class "Default")
      (node (ref "R96") (pin "2") (pinfunction "P$2_2") (pintype "bidirectional"))
      (node (ref "U20") (pin "63") (pinfunction "USBRBIAS_63") (pintype "bidirectional"))
    )
    (net (code "285") (name "Net-(R97-P$2)") (class "Default")
      (node (ref "R97") (pin "2") (pinfunction "P$2_2") (pintype "bidirectional"))
      (node (ref "R98") (pin "1") (pinfunction "P$1_1") (pintype "bidirectional"))
      (node (ref "U24") (pin "P$3") (pinfunction "-_P$3") (pintype "bidirectional"))
    )
    (net (code "286") (name "Net-(R107-P$1)") (class "Default")
      (node (ref "R107") (pin "1") (pinfunction "P$1_1") (pintype "bidirectional"))
      (node (ref "U33") (pin "P$5") (pinfunction "RST_P$5") (pintype "bidirectional"))
      (node (ref "U34") (pin "P$4") (pinfunction "P2_P$4") (pintype "bidirectional"))
    )
    (net (code "287") (name "Net-(R108-P$1)") (class "Default")
      (node (ref "CON62") (pin "3") (pinfunction "3_3") (pintype "bidirectional"))
      (node (ref "R108") (pin "1") (pinfunction "P$1_1") (pintype "bidirectional"))
      (node (ref "U34") (pin "P$1") (pinfunction "RST_P$1") (pintype "bidirectional"))
    )
    (net (code "288") (name "Net-(R109-P$1)") (class "Default")
      (node (ref "R109") (pin "1") (pinfunction "P$1_1") (pintype "bidirectional"))
      (node (ref "U36") (pin "P$4") (pinfunction "RST_P$4") (pintype "bidirectional"))
      (node (ref "U39") (pin "P$4") (pinfunction "P2_P$4") (pintype "bidirectional"))
    )
    (net (code "289") (name "Net-(R110-P$1)") (class "Default")
      (node (ref "CON64") (pin "3") (pinfunction "3_3") (pintype "bidirectional"))
      (node (ref "R110") (pin "1") (pinfunction "P$1_1") (pintype "bidirectional"))
      (node (ref "U39") (pin "P$1") (pinfunction "RST_P$1") (pintype "bidirectional"))
    )
    (net (code "290") (name "Net-(T1-D)") (class "Default")
      (node (ref "T1") (pin "P$3") (pinfunction "D_P$3") (pintype "bidirectional"))
      (node (ref "U2") (pin "-") (pinfunction "-_-") (pintype "bidirectional"))
    )
    (net (code "291") (name "Net-(T2-D)") (class "Default")
      (node (ref "K1") (pin "11") (pinfunction "C_11") (pintype "bidirectional"))
      (node (ref "K2") (pin "2") (pinfunction "C_2") (pintype "bidirectional"))
      (node (ref "T2") (pin "P$3") (pinfunction "D_P$3") (pintype "bidirectional"))
    )
    (net (code "292") (name "Net-(T3-D)") (class "Default")
      (node (ref "K3") (pin "2") (pinfunction "C_2") (pintype "bidirectional"))
      (node (ref "K4") (pin "11") (pinfunction "C_11") (pintype "bidirectional"))
      (node (ref "T3") (pin "P$3") (pinfunction "D_P$3") (pintype "bidirectional"))
    )
    (net (code "293") (name "Net-(U9-BSTA)") (class "Default")
      (node (ref "C55") (pin "P$1") (pinfunction "P$1_P$1") (pintype "bidirectional"))
      (node (ref "U9") (pin "P$35") (pinfunction "BSTA_P$35") (pintype "bidirectional"))
    )
    (net (code "294") (name "Net-(U9-BSTB)") (class "Default")
      (node (ref "C60") (pin "P$1") (pinfunction "P$1_P$1") (pintype "bidirectional"))
      (node (ref "U9") (pin "P$28") (pinfunction "BSTB_P$28") (pintype "bidirectional"))
    )
    (net (code "295") (name "Net-(U9-BSTC)") (class "Default")
      (node (ref "C62") (pin "P$1") (pinfunction "P$1_P$1") (pintype "bidirectional"))
      (node (ref "U9") (pin "P$27") (pinfunction "BSTC_P$27") (pintype "bidirectional"))
    )
    (net (code "296") (name "Net-(U9-BSTD)") (class "Default")
      (node (ref "C65") (pin "P$1") (pinfunction "P$1_P$1") (pintype "bidirectional"))
      (node (ref "U9") (pin "P$20") (pinfunction "BSTD_P$20") (pintype "bidirectional"))
    )
    (net (code "297") (name "Net-(U10-BSTA)") (class "Default")
      (node (ref "C61") (pin "P$1") (pinfunction "P$1_P$1") (pintype "bidirectional"))
      (node (ref "U10") (pin "P$35") (pinfunction "BSTA_P$35") (pintype "bidirectional"))
    )
    (net (code "298") (name "Net-(U10-BSTB)") (class "Default")
      (node (ref "C64") (pin "P$1") (pinfunction "P$1_P$1") (pintype "bidirectional"))
      (node (ref "U10") (pin "P$28") (pinfunction "BSTB_P$28") (pintype "bidirectional"))
    )
    (net (code "299") (name "Net-(U10-BSTC)") (class "Default")
      (node (ref "C68") (pin "P$1") (pinfunction "P$1_P$1") (pintype "bidirectional"))
      (node (ref "U10") (pin "P$27") (pinfunction "BSTC_P$27") (pintype "bidirectional"))
    )
    (net (code "300") (name "Net-(U10-BSTD)") (class "Default")
      (node (ref "C70") (pin "P$1") (pinfunction "P$1_P$1") (pintype "bidirectional"))
      (node (ref "U10") (pin "P$20") (pinfunction "BSTD_P$20") (pintype "bidirectional"))
    )
    (net (code "301") (name "Net-(U10-OUTA)") (class "Default")
      (node (ref "C61") (pin "P$2") (pinfunction "P$2_P$2") (pintype "bidirectional"))
      (node (ref "R23") (pin "P$1") (pinfunction "P$1_P$1") (pintype "bidirectional"))
      (node (ref "U10") (pin "P$33") (pinfunction "OUTA_P$33") (pintype "bidirectional"))
      (node (ref "U7") (pin "P$2") (pinfunction "IN+_P$2") (pintype "bidirectional"))
    )
    (net (code "302") (name "Net-(U10-OUTD)") (class "Default")
      (node (ref "C70") (pin "P$2") (pinfunction "P$2_P$2") (pintype "bidirectional"))
      (node (ref "R29") (pin "P$1") (pinfunction "P$1_P$1") (pintype "bidirectional"))
      (node (ref "U10") (pin "P$22") (pinfunction "OUTD_P$22") (pintype "bidirectional"))
      (node (ref "U13") (pin "P$3") (pinfunction "IN-_P$3") (pintype "bidirectional"))
    )
    (net (code "303") (name "Net-(U11-BSTA)") (class "Default")
      (node (ref "C63") (pin "P$1") (pinfunction "P$1_P$1") (pintype "bidirectional"))
      (node (ref "U11") (pin "P$35") (pinfunction "BSTA_P$35") (pintype "bidirectional"))
    )
    (net (code "304") (name "Net-(U11-BSTB)") (class "Default")
      (node (ref "C66") (pin "P$1") (pinfunction "P$1_P$1") (pintype "bidirectional"))
      (node (ref "U11") (pin "P$28") (pinfunction "BSTB_P$28") (pintype "bidirectional"))
    )
    (net (code "305") (name "Net-(U11-BSTC)") (class "Default")
      (node (ref "C69") (pin "P$1") (pinfunction "P$1_P$1") (pintype "bidirectional"))
      (node (ref "U11") (pin "P$27") (pinfunction "BSTC_P$27") (pintype "bidirectional"))
    )
    (net (code "306") (name "Net-(U11-BSTD)") (class "Default")
      (node (ref "C74") (pin "P$1") (pinfunction "P$1_P$1") (pintype "bidirectional"))
      (node (ref "U11") (pin "P$20") (pinfunction "BSTD_P$20") (pintype "bidirectional"))
    )
    (net (code "307") (name "Net-(U11-OUTA)") (class "Default")
      (node (ref "C63") (pin "P$2") (pinfunction "P$2_P$2") (pintype "bidirectional"))
      (node (ref "R25") (pin "P$1") (pinfunction "P$1_P$1") (pintype "bidirectional"))
      (node (ref "U11") (pin "P$33") (pinfunction "OUTA_P$33") (pintype "bidirectional"))
      (node (ref "U8") (pin "P$2") (pinfunction "IN+_P$2") (pintype "bidirectional"))
    )
    (net (code "308") (name "Net-(U14-BSTA)") (class "Default")
      (node (ref "C85") (pin "P$1") (pinfunction "P$1_P$1") (pintype "bidirectional"))
      (node (ref "U14") (pin "P$35") (pinfunction "BSTA_P$35") (pintype "bidirectional"))
    )
    (net (code "309") (name "Net-(U14-BSTB)") (class "Default")
      (node (ref "C86") (pin "P$1") (pinfunction "P$1_P$1") (pintype "bidirectional"))
      (node (ref "U14") (pin "P$28") (pinfunction "BSTB_P$28") (pintype "bidirectional"))
    )
    (net (code "310") (name "Net-(U14-BSTC)") (class "Default")
      (node (ref "C87") (pin "P$1") (pinfunction "P$1_P$1") (pintype "bidirectional"))
      (node (ref "U14") (pin "P$27") (pinfunction "BSTC_P$27") (pintype "bidirectional"))
    )
    (net (code "311") (name "Net-(U14-BSTD)") (class "Default")
      (node (ref "C88") (pin "P$1") (pinfunction "P$1_P$1") (pintype "bidirectional"))
      (node (ref "U14") (pin "P$20") (pinfunction "BSTD_P$20") (pintype "bidirectional"))
    )
    (net (code "312") (name "Net-(U16-IN+)") (class "Default")
      (node (ref "R36") (pin "P$1") (pinfunction "P$1_P$1") (pintype "bidirectional"))
      (node (ref "U16") (pin "P$2") (pinfunction "IN+_P$2") (pintype "bidirectional"))
      (node (ref "U17") (pin "PWR") (pinfunction "PWR_PWR") (pintype "bidirectional"))
    )
    (net (code "313") (name "Net-(U18-IN-)") (class "Default")
      (node (ref "R38") (pin "P$1") (pinfunction "P$1_P$1") (pintype "bidirectional"))
      (node (ref "U18") (pin "P$3") (pinfunction "IN-_P$3") (pintype "bidirectional"))
      (node (ref "U19") (pin "PWR") (pinfunction "PWR_PWR") (pintype "bidirectional"))
    )
    (net (code "314") (name "Net-(U20-USBDM0)") (class "Default")
      (node (ref "CON56") (pin "3") (pinfunction "3_3") (pintype "bidirectional"))
      (node (ref "U20") (pin "58") (pinfunction "USBDM0_58") (pintype "bidirectional"))
    )
    (net (code "315") (name "Net-(U20-USBDP0)") (class "Default")
      (node (ref "CON56") (pin "2") (pinfunction "2_2") (pintype "bidirectional"))
      (node (ref "U20") (pin "59") (pinfunction "USBDP0_59") (pintype "bidirectional"))
    )
    (net (code "316") (name "Net-(U33-SCL)") (class "Default")
      (node (ref "CON61") (pin "4") (pinfunction "4_4") (pintype "bidirectional"))
      (node (ref "CON62") (pin "4") (pinfunction "4_4") (pintype "bidirectional"))
      (node (ref "U33") (pin "P$10") (pinfunction "SCL_P$10") (pintype "bidirectional"))
      (node (ref "U34") (pin "P$12") (pinfunction "SCL_P$12") (pintype "bidirectional"))
    )
    (net (code "317") (name "Net-(U33-SDA)") (class "Default")
      (node (ref "CON61") (pin "2") (pinfunction "2_2") (pintype "bidirectional"))
      (node (ref "CON62") (pin "2") (pinfunction "2_2") (pintype "bidirectional"))
      (node (ref "U33") (pin "P$9") (pinfunction "SDA_P$9") (pintype "bidirectional"))
      (node (ref "U34") (pin "P$13") (pinfunction "SDA_P$13") (pintype "bidirectional"))
    )
    (net (code "318") (name "Net-(U34-P7)") (class "Default")
      (node (ref "CON61") (pin "3") (pinfunction "3_3") (pintype "bidirectional"))
      (node (ref "U34") (pin "P$10") (pinfunction "P7_P$10") (pintype "bidirectional"))
    )
    (net (code "319") (name "Net-(U34-VCCI)") (class "Default")
      (node (ref "C197") (pin "P$1") (pinfunction "P$1_P$1") (pintype "bidirectional"))
      (node (ref "U33") (pin "P$1") (pinfunction "VCC_P$1") (pintype "bidirectional"))
      (node (ref "U33") (pin "P$11") (pinfunction "VCC_P$11") (pintype "bidirectional"))
      (node (ref "U34") (pin "P$14") (pinfunction "VCCP_P$14") (pintype "bidirectional"))
      (node (ref "U34") (pin "P$15") (pinfunction "VCCI_P$15") (pintype "bidirectional"))
      (node (ref "U35") (pin "1") (pinfunction "VO_1") (pintype "bidirectional"))
    )
    (net (code "320") (name "Net-(U35-EN)") (class "Default")
      (node (ref "C198") (pin "P$1") (pinfunction "P$1_P$1") (pintype "bidirectional"))
      (node (ref "CON61") (pin "5") (pinfunction "5_5") (pintype "bidirectional"))
      (node (ref "CON62") (pin "5") (pinfunction "5_5") (pintype "bidirectional"))
      (node (ref "U35") (pin "4") (pinfunction "EN_4") (pintype "bidirectional"))
      (node (ref "U35") (pin "6") (pinfunction "VI_6") (pintype "bidirectional"))
    )
    (net (code "321") (name "Net-(U36-SCL)") (class "Default")
      (node (ref "CON63") (pin "4") (pinfunction "4_4") (pintype "bidirectional"))
      (node (ref "CON64") (pin "4") (pinfunction "4_4") (pintype "bidirectional"))
      (node (ref "U36") (pin "P$5") (pinfunction "SCL_P$5") (pintype "bidirectional"))
      (node (ref "U39") (pin "P$12") (pinfunction "SCL_P$12") (pintype "bidirectional"))
    )
    (net (code "322") (name "Net-(U36-SDA)") (class "Default")
      (node (ref "CON63") (pin "2") (pinfunction "2_2") (pintype "bidirectional"))
      (node (ref "CON64") (pin "2") (pinfunction "2_2") (pintype "bidirectional"))
      (node (ref "U36") (pin "P$6") (pinfunction "SDA_P$6") (pintype "bidirectional"))
      (node (ref "U39") (pin "P$13") (pinfunction "SDA_P$13") (pintype "bidirectional"))
    )
    (net (code "323") (name "Net-(U39-P7)") (class "Default")
      (node (ref "CON63") (pin "3") (pinfunction "3_3") (pintype "bidirectional"))
      (node (ref "U39") (pin "P$10") (pinfunction "P7_P$10") (pintype "bidirectional"))
    )
    (net (code "324") (name "Net-(U39-VCCI)") (class "Default")
      (node (ref "C196") (pin "P$1") (pinfunction "P$1_P$1") (pintype "bidirectional"))
      (node (ref "U36") (pin "P$10") (pinfunction "VCC_P$10") (pintype "bidirectional"))
      (node (ref "U36") (pin "P$8") (pinfunction "VCC_P$8") (pintype "bidirectional"))
      (node (ref "U39") (pin "P$14") (pinfunction "VCCP_P$14") (pintype "bidirectional"))
      (node (ref "U39") (pin "P$15") (pinfunction "VCCI_P$15") (pintype "bidirectional"))
      (node (ref "U40") (pin "1") (pinfunction "VO_1") (pintype "bidirectional"))
    )
    (net (code "325") (name "Net-(U40-EN)") (class "Default")
      (node (ref "C199") (pin "P$1") (pinfunction "P$1_P$1") (pintype "bidirectional"))
      (node (ref "CON63") (pin "5") (pinfunction "5_5") (pintype "bidirectional"))
      (node (ref "CON64") (pin "5") (pinfunction "5_5") (pintype "bidirectional"))
      (node (ref "U40") (pin "4") (pinfunction "EN_4") (pintype "bidirectional"))
      (node (ref "U40") (pin "6") (pinfunction "VI_6") (pintype "bidirectional"))
    )
    (net (code "326") (name "QEI0_A") (class "Default")
      (node (ref "CON57") (pin "14") (pinfunction "14_14") (pintype "bidirectional"))
      (node (ref "U27") (pin "P$9") (pinfunction "A8_P$9") (pintype "bidirectional"))
    )
    (net (code "327") (name "QEI0_A°") (class "Default")
      (node (ref "C111") (pin "2") (pinfunction "P$2_2") (pintype "bidirectional"))
      (node (ref "CON27") (pin "2") (pinfunction "2_2") (pintype "bidirectional"))
      (node (ref "R51") (pin "1") (pinfunction "P$1_1") (pintype "bidirectional"))
      (node (ref "U27") (pin "P$12") (pinfunction "B8_P$12") (pintype "bidirectional"))
    )
    (net (code "328") (name "QEI0_B") (class "Default")
      (node (ref "CON57") (pin "16") (pinfunction "16_16") (pintype "bidirectional"))
      (node (ref "U27") (pin "P$8") (pinfunction "A7_P$8") (pintype "bidirectional"))
    )
    (net (code "329") (name "QEI0_B°") (class "Default")
      (node (ref "C110") (pin "2") (pinfunction "P$2_2") (pintype "bidirectional"))
      (node (ref "CON27") (pin "3") (pinfunction "3_3") (pintype "bidirectional"))
      (node (ref "R50") (pin "1") (pinfunction "P$1_1") (pintype "bidirectional"))
      (node (ref "U27") (pin "P$13") (pinfunction "B7_P$13") (pintype "bidirectional"))
    )
    (net (code "330") (name "QEI1_A") (class "Default")
      (node (ref "CON58") (pin "36") (pinfunction "36_36") (pintype "bidirectional"))
      (node (ref "U30") (pin "P$3") (pinfunction "A2_P$3") (pintype "bidirectional"))
    )
    (net (code "331") (name "QEI1_A°") (class "Default")
      (node (ref "C105") (pin "2") (pinfunction "P$2_2") (pintype "bidirectional"))
      (node (ref "CON19") (pin "2") (pinfunction "2_2") (pintype "bidirectional"))
      (node (ref "R40") (pin "1") (pinfunction "P$1_1") (pintype "bidirectional"))
      (node (ref "U30") (pin "P$18") (pinfunction "B2_P$18") (pintype "bidirectional"))
    )
    (net (code "332") (name "QEI1_B") (class "Default")
      (node (ref "CON58") (pin "38") (pinfunction "38_38") (pintype "bidirectional"))
      (node (ref "U30") (pin "P$1") (pinfunction "A1_P$1") (pintype "bidirectional"))
    )
    (net (code "333") (name "QEI1_B°") (class "Default")
      (node (ref "C104") (pin "2") (pinfunction "P$2_2") (pintype "bidirectional"))
      (node (ref "CON19") (pin "3") (pinfunction "3_3") (pintype "bidirectional"))
      (node (ref "R39") (pin "1") (pinfunction "P$1_1") (pintype "bidirectional"))
      (node (ref "U30") (pin "P$20") (pinfunction "B1_P$20") (pintype "bidirectional"))
    )
    (net (code "334") (name "QEI2_A") (class "Default")
      (node (ref "CON57") (pin "18") (pinfunction "18_18") (pintype "bidirectional"))
      (node (ref "U27") (pin "P$7") (pinfunction "A6_P$7") (pintype "bidirectional"))
    )
    (net (code "335") (name "QEI2_A°") (class "Default")
      (node (ref "C128") (pin "2") (pinfunction "P$2_2") (pintype "bidirectional"))
      (node (ref "R73") (pin "1") (pinfunction "P$1_1") (pintype "bidirectional"))
      (node (ref "U27") (pin "P$14") (pinfunction "B6_P$14") (pintype "bidirectional"))
    )
    (net (code "336") (name "QEI2_B") (class "Default")
      (node (ref "CON57") (pin "19") (pinfunction "19_19") (pintype "bidirectional"))
      (node (ref "U27") (pin "P$6") (pinfunction "A5_P$6") (pintype "bidirectional"))
    )
    (net (code "337") (name "QEI2_B°") (class "Default")
      (node (ref "C127") (pin "2") (pinfunction "P$2_2") (pintype "bidirectional"))
      (node (ref "R72") (pin "1") (pinfunction "P$1_1") (pintype "bidirectional"))
      (node (ref "U27") (pin "P$15") (pinfunction "B5_P$15") (pintype "bidirectional"))
    )
    (net (code "338") (name "QEI2_Z") (class "Default")
      (node (ref "CON57") (pin "20") (pinfunction "20_20") (pintype "bidirectional"))
      (node (ref "U27") (pin "P$5") (pinfunction "A4_P$5") (pintype "bidirectional"))
    )
    (net (code "339") (name "QEI2_Z°") (class "Default")
      (node (ref "C126") (pin "2") (pinfunction "P$2_2") (pintype "bidirectional"))
      (node (ref "R71") (pin "1") (pinfunction "P$1_1") (pintype "bidirectional"))
      (node (ref "U27") (pin "P$16") (pinfunction "B4_P$16") (pintype "bidirectional"))
    )
    (net (code "340") (name "QEI3_A") (class "Default")
      (node (ref "CON58") (pin "28") (pinfunction "28_28") (pintype "bidirectional"))
      (node (ref "U30") (pin "P$6") (pinfunction "A5_P$6") (pintype "bidirectional"))
    )
    (net (code "341") (name "QEI3_A°") (class "Default")
      (node (ref "C121") (pin "2") (pinfunction "P$2_2") (pintype "bidirectional"))
      (node (ref "R62") (pin "1") (pinfunction "P$1_1") (pintype "bidirectional"))
      (node (ref "U30") (pin "P$15") (pinfunction "B5_P$15") (pintype "bidirectional"))
    )
    (net (code "342") (name "QEI3_B") (class "Default")
      (node (ref "CON58") (pin "32") (pinfunction "32_32") (pintype "bidirectional"))
      (node (ref "U30") (pin "P$5") (pinfunction "A4_P$5") (pintype "bidirectional"))
    )
    (net (code "343") (name "QEI3_B°") (class "Default")
      (node (ref "C120") (pin "2") (pinfunction "P$2_2") (pintype "bidirectional"))
      (node (ref "R61") (pin "1") (pinfunction "P$1_1") (pintype "bidirectional"))
      (node (ref "U30") (pin "P$16") (pinfunction "B4_P$16") (pintype "bidirectional"))
    )
    (net (code "344") (name "QEI3_Z") (class "Default")
      (node (ref "CON58") (pin "34") (pinfunction "34_34") (pintype "bidirectional"))
      (node (ref "U30") (pin "P$4") (pinfunction "A3_P$4") (pintype "bidirectional"))
    )
    (net (code "345") (name "QEI3_Z°") (class "Default")
      (node (ref "C119") (pin "2") (pinfunction "P$2_2") (pintype "bidirectional"))
      (node (ref "R58") (pin "1") (pinfunction "P$1_1") (pintype "bidirectional"))
      (node (ref "U30") (pin "P$17") (pinfunction "B3_P$17") (pintype "bidirectional"))
    )
    (net (code "346") (name "RX0") (class "Default")
      (node (ref "CON57") (pin "39") (pinfunction "39_39") (pintype "bidirectional"))
      (node (ref "U25") (pin "P$3") (pinfunction "A2_P$3") (pintype "bidirectional"))
    )
    (net (code "347") (name "RX0°") (class "Default")
      (node (ref "CON18") (pin "2") (pinfunction "2_2") (pintype "bidirectional"))
      (node (ref "U25") (pin "P$18") (pinfunction "B2_P$18") (pintype "bidirectional"))
    )
    (net (code "348") (name "RX1") (class "Default")
      (node (ref "CON58") (pin "4") (pinfunction "4_4") (pintype "bidirectional"))
      (node (ref "U32") (pin "P$9") (pinfunction "A8_P$9") (pintype "bidirectional"))
    )
    (net (code "349") (name "RX1°") (class "Default")
      (node (ref "CON26") (pin "2") (pinfunction "2_2") (pintype "bidirectional"))
      (node (ref "U32") (pin "P$12") (pinfunction "B8_P$12") (pintype "bidirectional"))
    )
    (net (code "350") (name "RX2") (class "Default")
      (node (ref "CON57") (pin "37") (pinfunction "37_37") (pintype "bidirectional"))
      (node (ref "U25") (pin "P$5") (pinfunction "A4_P$5") (pintype "bidirectional"))
    )
    (net (code "351") (name "RX2°") (class "Default")
      (node (ref "CON31") (pin "2") (pinfunction "2_2") (pintype "bidirectional"))
      (node (ref "U25") (pin "P$16") (pinfunction "B4_P$16") (pintype "bidirectional"))
    )
    (net (code "352") (name "RX3") (class "Default")
      (node (ref "CON58") (pin "8") (pinfunction "8_8") (pintype "bidirectional"))
      (node (ref "U32") (pin "P$7") (pinfunction "A6_P$7") (pintype "bidirectional"))
    )
    (net (code "353") (name "RX3°") (class "Default")
      (node (ref "CON36") (pin "2") (pinfunction "2_2") (pintype "bidirectional"))
      (node (ref "U32") (pin "P$14") (pinfunction "B6_P$14") (pintype "bidirectional"))
    )
    (net (code "354") (name "S0") (class "Default")
      (node (ref "CON58") (pin "15") (pinfunction "15_15") (pintype "bidirectional"))
      (node (ref "U26") (pin "P$9") (pinfunction "A8_P$9") (pintype "bidirectional"))
    )
    (net (code "355") (name "S0_CS") (class "Default")
      (node (ref "C101") (pin "2") (pinfunction "P$2_2") (pintype "bidirectional"))
      (node (ref "IC1") (pin "33") (pinfunction "AIN15_33") (pintype "passive"))
      (node (ref "R44") (pin "1") (pinfunction "P$1_1") (pintype "bidirectional"))
    )
    (net (code "356") (name "S0°") (class "Default")
      (node (ref "CON21") (pin "3") (pinfunction "3_3") (pintype "bidirectional"))
      (node (ref "U26") (pin "P$12") (pinfunction "B8_P$12") (pintype "bidirectional"))
    )
    (net (code "357") (name "S1") (class "Default")
      (node (ref "CON58") (pin "13") (pinfunction "13_13") (pintype "bidirectional"))
      (node (ref "U26") (pin "P$8") (pinfunction "A7_P$8") (pintype "bidirectional"))
    )
    (net (code "358") (name "S1_CS") (class "Default")
      (node (ref "C107") (pin "2") (pinfunction "P$2_2") (pintype "bidirectional"))
      (node (ref "IC1") (pin "34") (pinfunction "AIN14_34") (pintype "passive"))
      (node (ref "R49") (pin "1") (pinfunction "P$1_1") (pintype "bidirectional"))
    )
    (net (code "359") (name "S1°") (class "Default")
      (node (ref "CON24") (pin "3") (pinfunction "3_3") (pintype "bidirectional"))
      (node (ref "U26") (pin "P$13") (pinfunction "B7_P$13") (pintype "bidirectional"))
    )
    (net (code "360") (name "S2") (class "Default")
      (node (ref "CON58") (pin "9") (pinfunction "9_9") (pintype "bidirectional"))
      (node (ref "U26") (pin "P$7") (pinfunction "A6_P$7") (pintype "bidirectional"))
    )
    (net (code "361") (name "S2_CS") (class "Default")
      (node (ref "C113") (pin "2") (pinfunction "P$2_2") (pintype "bidirectional"))
      (node (ref "IC1") (pin "35") (pinfunction "AIN13_35") (pintype "passive"))
      (node (ref "R56") (pin "1") (pinfunction "P$1_1") (pintype "bidirectional"))
    )
    (net (code "362") (name "S2°") (class "Default")
      (node (ref "CON29") (pin "3") (pinfunction "3_3") (pintype "bidirectional"))
      (node (ref "U26") (pin "P$14") (pinfunction "B6_P$14") (pintype "bidirectional"))
    )
    (net (code "363") (name "S3") (class "Default")
      (node (ref "CON58") (pin "7") (pinfunction "7_7") (pintype "bidirectional"))
      (node (ref "U26") (pin "P$6") (pinfunction "A5_P$6") (pintype "bidirectional"))
    )
    (net (code "364") (name "S3_CS") (class "Default")
      (node (ref "C116") (pin "2") (pinfunction "P$2_2") (pintype "bidirectional"))
      (node (ref "IC1") (pin "36") (pinfunction "AIN12_36") (pintype "passive"))
      (node (ref "R64") (pin "1") (pinfunction "P$1_1") (pintype "bidirectional"))
    )
    (net (code "365") (name "S3°") (class "Default")
      (node (ref "CON34") (pin "3") (pinfunction "3_3") (pintype "bidirectional"))
      (node (ref "U26") (pin "P$15") (pinfunction "B5_P$15") (pintype "bidirectional"))
    )
    (net (code "366") (name "S4") (class "Default")
      (node (ref "CON57") (pin "31") (pinfunction "31_31") (pintype "bidirectional"))
      (node (ref "U26") (pin "P$5") (pinfunction "A4_P$5") (pintype "bidirectional"))
    )
    (net (code "367") (name "S4_CS") (class "Default")
      (node (ref "C123") (pin "2") (pinfunction "P$2_2") (pintype "bidirectional"))
      (node (ref "IC1") (pin "37") (pinfunction "AIN11_37") (pintype "passive"))
      (node (ref "R69") (pin "1") (pinfunction "P$1_1") (pintype "bidirectional"))
    )
    (net (code "368") (name "S4°") (class "Default")
      (node (ref "CON38") (pin "3") (pinfunction "3_3") (pintype "bidirectional"))
      (node (ref "U26") (pin "P$16") (pinfunction "B4_P$16") (pintype "bidirectional"))
    )
    (net (code "369") (name "S5") (class "Default")
      (node (ref "U26") (pin "P$4") (pinfunction "A3_P$4") (pintype "bidirectional"))
      (node (ref "U29") (pin "D0") (pinfunction "D0_D0") (pintype "bidirectional"))
    )
    (net (code "370") (name "S5_CS") (class "Default")
      (node (ref "C130") (pin "2") (pinfunction "P$2_2") (pintype "bidirectional"))
      (node (ref "IC1") (pin "38") (pinfunction "AIN10_38") (pintype "passive"))
      (node (ref "R77") (pin "1") (pinfunction "P$1_1") (pintype "bidirectional"))
    )
    (net (code "371") (name "S5°") (class "Default")
      (node (ref "CON43") (pin "3") (pinfunction "3_3") (pintype "bidirectional"))
      (node (ref "U26") (pin "P$17") (pinfunction "B3_P$17") (pintype "bidirectional"))
    )
    (net (code "372") (name "S6") (class "Default")
      (node (ref "U26") (pin "P$3") (pinfunction "A2_P$3") (pintype "bidirectional"))
      (node (ref "U29") (pin "D1") (pinfunction "D1_D1") (pintype "bidirectional"))
    )
    (net (code "373") (name "S6_CS") (class "Default")
      (node (ref "C133") (pin "2") (pinfunction "P$2_2") (pintype "bidirectional"))
      (node (ref "IC1") (pin "39") (pinfunction "AIN9_39") (pintype "passive"))
      (node (ref "R82") (pin "1") (pinfunction "P$1_1") (pintype "bidirectional"))
    )
    (net (code "374") (name "S6°") (class "Default")
      (node (ref "CON47") (pin "3") (pinfunction "3_3") (pintype "bidirectional"))
      (node (ref "U26") (pin "P$18") (pinfunction "B2_P$18") (pintype "bidirectional"))
    )
    (net (code "375") (name "S7") (class "Default")
      (node (ref "U26") (pin "P$1") (pinfunction "A1_P$1") (pintype "bidirectional"))
      (node (ref "U29") (pin "D2") (pinfunction "D2_D2") (pintype "bidirectional"))
    )
    (net (code "376") (name "S7_CS") (class "Default")
      (node (ref "C136") (pin "2") (pinfunction "P$2_2") (pintype "bidirectional"))
      (node (ref "IC1") (pin "40") (pinfunction "AIN8_40") (pintype "passive"))
      (node (ref "R87") (pin "1") (pinfunction "P$1_1") (pintype "bidirectional"))
    )
    (net (code "377") (name "S7°") (class "Default")
      (node (ref "CON51") (pin "3") (pinfunction "3_3") (pintype "bidirectional"))
      (node (ref "U26") (pin "P$20") (pinfunction "B1_P$20") (pintype "bidirectional"))
    )
    (net (code "378") (name "SCL0") (class "Default")
      (node (ref "CON57") (pin "23") (pinfunction "23_23") (pintype "bidirectional"))
      (node (ref "R101") (pin "1") (pinfunction "P$1_1") (pintype "bidirectional"))
      (node (ref "U27") (pin "P$1") (pinfunction "A1_P$1") (pintype "bidirectional"))
    )
    (net (code "379") (name "SCL0°") (class "Default")
      (node (ref "CON49") (pin "4") (pinfunction "4_4") (pintype "bidirectional"))
      (node (ref "R99") (pin "1") (pinfunction "P$1_1") (pintype "bidirectional"))
      (node (ref "U27") (pin "P$20") (pinfunction "B1_P$20") (pintype "bidirectional"))
    )
    (net (code "380") (name "SCL1") (class "Default")
      (node (ref "CON58") (pin "26") (pinfunction "26_26") (pintype "bidirectional"))
      (node (ref "R106") (pin "1") (pinfunction "P$1_1") (pintype "bidirectional"))
      (node (ref "U30") (pin "P$7") (pinfunction "A6_P$7") (pintype "bidirectional"))
    )
    (net (code "381") (name "SCL1°") (class "Default")
      (node (ref "CON53") (pin "4") (pinfunction "4_4") (pintype "bidirectional"))
      (node (ref "R103") (pin "1") (pinfunction "P$1_1") (pintype "bidirectional"))
      (node (ref "U30") (pin "P$14") (pinfunction "B6_P$14") (pintype "bidirectional"))
    )
    (net (code "382") (name "SCLK0") (class "Default")
      (node (ref "CON57") (pin "33") (pinfunction "33_33") (pintype "bidirectional"))
      (node (ref "U25") (pin "P$9") (pinfunction "A8_P$9") (pintype "bidirectional"))
    )
    (net (code "383") (name "SCLK0°") (class "Default")
      (node (ref "CON40") (pin "2") (pinfunction "2_2") (pintype "bidirectional"))
      (node (ref "U25") (pin "P$12") (pinfunction "B8_P$12") (pintype "bidirectional"))
    )
    (net (code "384") (name "SCLK1") (class "Default")
      (node (ref "CON58") (pin "14") (pinfunction "14_14") (pintype "bidirectional"))
      (node (ref "U32") (pin "P$5") (pinfunction "A4_P$5") (pintype "bidirectional"))
      (node (ref "U37") (pin "23") (pinfunction "SCL/SCLK_23") (pintype "bidirectional"))
    )
    (net (code "385") (name "SCLK1°") (class "Default")
      (node (ref "CON45") (pin "2") (pinfunction "2_2") (pintype "bidirectional"))
      (node (ref "U32") (pin "P$16") (pinfunction "B4_P$16") (pintype "bidirectional"))
    )
    (net (code "386") (name "SDA0") (class "Default")
      (node (ref "CON57") (pin "21") (pinfunction "21_21") (pintype "bidirectional"))
      (node (ref "R102") (pin "1") (pinfunction "P$1_1") (pintype "bidirectional"))
      (node (ref "U27") (pin "P$4") (pinfunction "A3_P$4") (pintype "bidirectional"))
    )
    (net (code "387") (name "SDA0°") (class "Default")
      (node (ref "CON49") (pin "2") (pinfunction "2_2") (pintype "bidirectional"))
      (node (ref "R100") (pin "1") (pinfunction "P$1_1") (pintype "bidirectional"))
      (node (ref "U27") (pin "P$17") (pinfunction "B3_P$17") (pintype "bidirectional"))
    )
    (net (code "388") (name "SDA1") (class "Default")
      (node (ref "CON58") (pin "22") (pinfunction "22_22") (pintype "bidirectional"))
      (node (ref "R105") (pin "1") (pinfunction "P$1_1") (pintype "bidirectional"))
      (node (ref "U30") (pin "P$9") (pinfunction "A8_P$9") (pintype "bidirectional"))
    )
    (net (code "389") (name "SDA1°") (class "Default")
      (node (ref "CON53") (pin "2") (pinfunction "2_2") (pintype "bidirectional"))
      (node (ref "R104") (pin "1") (pinfunction "P$1_1") (pintype "bidirectional"))
      (node (ref "U30") (pin "P$12") (pinfunction "B8_P$12") (pintype "bidirectional"))
    )
    (net (code "390") (name "SS0") (class "Default")
      (node (ref "CON57") (pin "34") (pinfunction "34_34") (pintype "bidirectional"))
      (node (ref "U25") (pin "P$8") (pinfunction "A7_P$8") (pintype "bidirectional"))
    )
    (net (code "391") (name "SS0°") (class "Default")
      (node (ref "CON40") (pin "3") (pinfunction "3_3") (pintype "bidirectional"))
      (node (ref "U25") (pin "P$13") (pinfunction "B7_P$13") (pintype "bidirectional"))
    )
    (net (code "392") (name "SS1") (class "Default")
      (node (ref "CON58") (pin "16") (pinfunction "16_16") (pintype "bidirectional"))
      (node (ref "U32") (pin "P$4") (pinfunction "A3_P$4") (pintype "bidirectional"))
    )
    (net (code "393") (name "SS1°") (class "Default")
      (node (ref "CON45") (pin "3") (pinfunction "3_3") (pintype "bidirectional"))
      (node (ref "U32") (pin "P$17") (pinfunction "B3_P$17") (pintype "bidirectional"))
    )
    (net (code "394") (name "TELEM") (class "Default")
      (node (ref "U29") (pin "D9") (pinfunction "D9_D9") (pintype "bidirectional"))
      (node (ref "U31") (pin "P$1") (pinfunction "A1_P$1") (pintype "bidirectional"))
    )
    (net (code "395") (name "TELEM°") (class "Default")
      (node (ref "CON31") (pin "5") (pinfunction "5_5") (pintype "bidirectional"))
      (node (ref "U31") (pin "P$20") (pinfunction "B1_P$20") (pintype "bidirectional"))
    )
    (net (code "396") (name "TX0") (class "Default")
      (node (ref "CON57") (pin "40") (pinfunction "40_40") (pintype "bidirectional"))
      (node (ref "U25") (pin "P$1") (pinfunction "A1_P$1") (pintype "bidirectional"))
    )
    (net (code "397") (name "TX0°") (class "Default")
      (node (ref "CON18") (pin "3") (pinfunction "3_3") (pintype "bidirectional"))
      (node (ref "U25") (pin "P$20") (pinfunction "B1_P$20") (pintype "bidirectional"))
    )
    (net (code "398") (name "TX1") (class "Default")
      (node (ref "CON58") (pin "6") (pinfunction "6_6") (pintype "bidirectional"))
      (node (ref "U32") (pin "P$8") (pinfunction "A7_P$8") (pintype "bidirectional"))
    )
    (net (code "399") (name "TX1°") (class "Default")
      (node (ref "CON26") (pin "3") (pinfunction "3_3") (pintype "bidirectional"))
      (node (ref "U32") (pin "P$13") (pinfunction "B7_P$13") (pintype "bidirectional"))
    )
    (net (code "400") (name "TX2") (class "Default")
      (node (ref "CON57") (pin "38") (pinfunction "38_38") (pintype "bidirectional"))
      (node (ref "U25") (pin "P$4") (pinfunction "A3_P$4") (pintype "bidirectional"))
    )
    (net (code "401") (name "TX2°") (class "Default")
      (node (ref "CON31") (pin "3") (pinfunction "3_3") (pintype "bidirectional"))
      (node (ref "U25") (pin "P$17") (pinfunction "B3_P$17") (pintype "bidirectional"))
    )
    (net (code "402") (name "TX3") (class "Default")
      (node (ref "CON58") (pin "10") (pinfunction "10_10") (pintype "bidirectional"))
      (node (ref "U32") (pin "P$6") (pinfunction "A5_P$6") (pintype "bidirectional"))
    )
    (net (code "403") (name "TX3°") (class "Default")
      (node (ref "CON36") (pin "3") (pinfunction "3_3") (pintype "bidirectional"))
      (node (ref "U32") (pin "P$15") (pinfunction "B5_P$15") (pintype "bidirectional"))
    )
    (net (code "404") (name "WIFI0_DM") (class "Default")
      (node (ref "U20") (pin "8") (pinfunction "USBDM5_8") (pintype "bidirectional"))
      (node (ref "U21") (pin "P$5") (pinfunction "DM_P$5") (pintype "bidirectional"))
    )
    (net (code "405") (name "WIFI0_DP") (class "Default")
      (node (ref "U20") (pin "9") (pinfunction "USBDP5_9") (pintype "bidirectional"))
      (node (ref "U21") (pin "P$4") (pinfunction "DP_P$4") (pintype "bidirectional"))
    )
    (net (code "406") (name "WIFI1_DM") (class "Default")
      (node (ref "J48") (pin "P$2") (pinfunction "2_P$2") (pintype "bidirectional"))
      (node (ref "U20") (pin "1") (pinfunction "USBDM2_1") (pintype "bidirectional"))
      (node (ref "U22") (pin "P$5") (pinfunction "DM_P$5") (pintype "bidirectional"))
    )
    (net (code "407") (name "WIFI1_DP") (class "Default")
      (node (ref "J49") (pin "P$2") (pinfunction "2_P$2") (pintype "bidirectional"))
      (node (ref "U20") (pin "2") (pinfunction "USBDP2_2") (pintype "bidirectional"))
      (node (ref "U22") (pin "P$4") (pinfunction "DP_P$4") (pintype "bidirectional"))
    )
    (net (code "408") (name "unconnected-(CON18-Pad5)") (class "Default")
      (node (ref "CON18") (pin "5") (pinfunction "5_5") (pintype "bidirectional"))
    )
    (net (code "409") (name "unconnected-(CON26-Pad5)") (class "Default")
      (node (ref "CON26") (pin "5") (pinfunction "5_5") (pintype "bidirectional"))
    )
    (net (code "410") (name "unconnected-(CON57-Pad11)") (class "Default")
      (node (ref "CON57") (pin "11") (pinfunction "11_11") (pintype "bidirectional"))
    )
    (net (code "411") (name "unconnected-(CON58-Pad11)") (class "Default")
      (node (ref "CON58") (pin "11") (pinfunction "11_11") (pintype "bidirectional"))
    )
    (net (code "412") (name "unconnected-(CON59-1-PadP$1)") (class "Default")
      (node (ref "CON59") (pin "P$1") (pinfunction "1_P$1") (pintype "bidirectional"))
    )
    (net (code "413") (name "unconnected-(CON59-2-PadP$2)") (class "Default")
      (node (ref "CON59") (pin "P$2") (pinfunction "2_P$2") (pintype "bidirectional"))
    )
    (net (code "414") (name "unconnected-(CON59-3-PadP$3)") (class "Default")
      (node (ref "CON59") (pin "P$3") (pinfunction "3_P$3") (pintype "bidirectional"))
    )
    (net (code "415") (name "unconnected-(CON59-4-PadP$4)") (class "Default")
      (node (ref "CON59") (pin "P$4") (pinfunction "4_P$4") (pintype "bidirectional"))
    )
    (net (code "416") (name "unconnected-(CON59-5-PadP$5)") (class "Default")
      (node (ref "CON59") (pin "P$5") (pinfunction "5_P$5") (pintype "bidirectional"))
    )
    (net (code "417") (name "unconnected-(CON59-6-PadP$6)") (class "Default")
      (node (ref "CON59") (pin "P$6") (pinfunction "6_P$6") (pintype "bidirectional"))
    )
    (net (code "418") (name "unconnected-(CON59-7-PadP$7)") (class "Default")
      (node (ref "CON59") (pin "P$7") (pinfunction "7_P$7") (pintype "bidirectional"))
    )
    (net (code "419") (name "unconnected-(CON59-8-PadP$8)") (class "Default")
      (node (ref "CON59") (pin "P$8") (pinfunction "8_P$8") (pintype "bidirectional"))
    )
    (net (code "420") (name "unconnected-(CON59-9-PadP$9)") (class "Default")
      (node (ref "CON59") (pin "P$9") (pinfunction "9_P$9") (pintype "bidirectional"))
    )
    (net (code "421") (name "unconnected-(CON59-10-PadP$10)") (class "Default")
      (node (ref "CON59") (pin "P$10") (pinfunction "10_P$10") (pintype "bidirectional"))
    )
    (net (code "422") (name "unconnected-(CON59-11-PadP$11)") (class "Default")
      (node (ref "CON59") (pin "P$11") (pinfunction "11_P$11") (pintype "bidirectional"))
    )
    (net (code "423") (name "unconnected-(CON59-12-PadP$12)") (class "Default")
      (node (ref "CON59") (pin "P$12") (pinfunction "12_P$12") (pintype "bidirectional"))
    )
    (net (code "424") (name "unconnected-(CON59-13-PadP$13)") (class "Default")
      (node (ref "CON59") (pin "P$13") (pinfunction "13_P$13") (pintype "bidirectional"))
    )
    (net (code "425") (name "unconnected-(CON59-14-PadP$14)") (class "Default")
      (node (ref "CON59") (pin "P$14") (pinfunction "14_P$14") (pintype "bidirectional"))
    )
    (net (code "426") (name "unconnected-(IC1-CLKIO-Pad13)") (class "Default")
      (node (ref "IC1") (pin "13") (pinfunction "CLKIO_13") (pintype "passive"))
    )
    (net (code "427") (name "unconnected-(IC1-GPIO0-Pad14)") (class "Default")
      (node (ref "IC1") (pin "14") (pinfunction "GPIO0_14") (pintype "passive"))
    )
    (net (code "428") (name "unconnected-(IC1-GPIO1-Pad15)") (class "Default")
      (node (ref "IC1") (pin "15") (pinfunction "GPIO1_15") (pintype "passive"))
    )
    (net (code "429") (name "unconnected-(IC1-GPIO2-Pad16)") (class "Default")
      (node (ref "IC1") (pin "16") (pinfunction "GPIO2_16") (pintype "passive"))
    )
    (net (code "430") (name "unconnected-(IC1-GPIO3-Pad17)") (class "Default")
      (node (ref "IC1") (pin "17") (pinfunction "GPIO3_17") (pintype "passive"))
    )
    (net (code "431") (name "unconnected-(IC1-GPIO4-Pad18)") (class "Default")
      (node (ref "IC1") (pin "18") (pinfunction "GPIO4_18") (pintype "passive"))
    )
    (net (code "432") (name "unconnected-(IC1-GPIO5-Pad19)") (class "Default")
      (node (ref "IC1") (pin "19") (pinfunction "GPIO5_19") (pintype "passive"))
    )
    (net (code "433") (name "unconnected-(IC1-GPIO6-Pad20)") (class "Default")
      (node (ref "IC1") (pin "20") (pinfunction "GPIO6_20") (pintype "passive"))
    )
    (net (code "434") (name "unconnected-(IC1-GPIO7-Pad21)") (class "Default")
      (node (ref "IC1") (pin "21") (pinfunction "GPIO7_21") (pintype "passive"))
    )
    (net (code "435") (name "unconnected-(IC1-MUXOUTN-Pad43)") (class "Default")
      (node (ref "IC1") (pin "43") (pinfunction "MUXOUTN_43") (pintype "passive"))
    )
    (net (code "436") (name "unconnected-(IC2-DOUT2-Pad19)") (class "Default")
      (node (ref "IC2") (pin "19") (pinfunction "DOUT2_19") (pintype "passive"))
    )
    (net (code "437") (name "unconnected-(IC2-DOUT3-Pad18)") (class "Default")
      (node (ref "IC2") (pin "18") (pinfunction "DOUT3_18") (pintype "passive"))
    )
    (net (code "438") (name "unconnected-(IC2-DOUT4-Pad17)") (class "Default")
      (node (ref "IC2") (pin "17") (pinfunction "DOUT4_17") (pintype "passive"))
    )
    (net (code "439") (name "unconnected-(IC2-DOUT5-Pad16)") (class "Default")
      (node (ref "IC2") (pin "16") (pinfunction "DOUT5_16") (pintype "passive"))
    )
    (net (code "440") (name "unconnected-(IC2-DOUT6-Pad15)") (class "Default")
      (node (ref "IC2") (pin "15") (pinfunction "DOUT6_15") (pintype "passive"))
    )
    (net (code "441") (name "unconnected-(IC2-DOUT7-Pad14)") (class "Default")
      (node (ref "IC2") (pin "14") (pinfunction "DOUT7_14") (pintype "passive"))
    )
    (net (code "442") (name "unconnected-(IC2-DOUT8-Pad13)") (class "Default")
      (node (ref "IC2") (pin "13") (pinfunction "DOUT8_13") (pintype "passive"))
    )
    (net (code "443") (name "unconnected-(IC3-DNC-Pad1)") (class "Default")
      (node (ref "IC3") (pin "1") (pinfunction "DNC_1") (pintype "passive"))
    )
    (net (code "444") (name "unconnected-(IC3-DNC-Pad8)") (class "Default")
      (node (ref "IC3") (pin "8") (pinfunction "DNC_8") (pintype "passive"))
    )
    (net (code "445") (name "unconnected-(IC3-TEMP-Pad3)") (class "Default")
      (node (ref "IC3") (pin "3") (pinfunction "TEMP_3") (pintype "passive"))
    )
    (net (code "446") (name "unconnected-(IC4-DNC-Pad1)") (class "Default")
      (node (ref "IC4") (pin "1") (pinfunction "DNC_1") (pintype "passive"))
    )
    (net (code "447") (name "unconnected-(IC4-DNC-Pad8)") (class "Default")
      (node (ref "IC4") (pin "8") (pinfunction "DNC_8") (pintype "passive"))
    )
    (net (code "448") (name "unconnected-(IC4-TEMP-Pad3)") (class "Default")
      (node (ref "IC4") (pin "3") (pinfunction "TEMP_3") (pintype "passive"))
    )
    (net (code "449") (name "unconnected-(U3-INHIBIT-PadP$1)") (class "Default")
      (node (ref "U3") (pin "P$1") (pinfunction "INHIBIT_P$1") (pintype "bidirectional"))
    )
    (net (code "450") (name "unconnected-(U4-PG-PadP$7)") (class "Default")
      (node (ref "U4") (pin "P$7") (pinfunction "PG_P$7") (pintype "bidirectional"))
    )
    (net (code "451") (name "unconnected-(U5-PG-PadP$7)") (class "Default")
      (node (ref "U5") (pin "P$7") (pinfunction "PG_P$7") (pintype "bidirectional"))
    )
    (net (code "452") (name "unconnected-(U6-PG-PadP$7)") (class "Default")
      (node (ref "U6") (pin "P$7") (pinfunction "PG_P$7") (pintype "bidirectional"))
    )
    (net (code "453") (name "unconnected-(U20-CLK24_OUT-Pad45)") (class "Default")
      (node (ref "U20") (pin "45") (pinfunction "CLK24_OUT_45") (pintype "bidirectional"))
    )
    (net (code "454") (name "unconnected-(U20-EECLK-Pad23)") (class "Default")
      (node (ref "U20") (pin "23") (pinfunction "EECLK_23") (pintype "bidirectional"))
    )
    (net (code "455") (name "unconnected-(U20-EEDI-Pad26)") (class "Default")
      (node (ref "U20") (pin "26") (pinfunction "EEDI_26") (pintype "bidirectional"))
    )
    (net (code "456") (name "unconnected-(U20-EEDO-Pad25)") (class "Default")
      (node (ref "U20") (pin "25") (pinfunction "EEDO_25") (pintype "bidirectional"))
    )
    (net (code "457") (name "unconnected-(U20-GPIO3-Pad35)") (class "Default")
      (node (ref "U20") (pin "35") (pinfunction "GPIO3_35") (pintype "bidirectional"))
    )
    (net (code "458") (name "unconnected-(U20-GPIO4-Pad36)") (class "Default")
      (node (ref "U20") (pin "36") (pinfunction "GPIO4_36") (pintype "bidirectional"))
    )
    (net (code "459") (name "unconnected-(U20-GPIO5-Pad37)") (class "Default")
      (node (ref "U20") (pin "37") (pinfunction "GPIO5_37") (pintype "bidirectional"))
    )
    (net (code "460") (name "unconnected-(U20-GPIO6-Pad42)") (class "Default")
      (node (ref "U20") (pin "42") (pinfunction "GPIO6_42") (pintype "bidirectional"))
    )
    (net (code "461") (name "unconnected-(U20-GPIO7-Pad43)") (class "Default")
      (node (ref "U20") (pin "43") (pinfunction "GPIO7_43") (pintype "bidirectional"))
    )
    (net (code "462") (name "unconnected-(U20-NFDX_LED{slash}_GPIO0-Pad20)") (class "Default")
      (node (ref "U20") (pin "20") (pinfunction "NFDX_LED/_GPIO0_20") (pintype "bidirectional"))
    )
    (net (code "463") (name "unconnected-(U20-NLNKA_LED{slash}_GPIO1-Pad21)") (class "Default")
      (node (ref "U20") (pin "21") (pinfunction "NLNKA_LED/_GPIO1_21") (pintype "bidirectional"))
    )
    (net (code "464") (name "unconnected-(U20-NSPD_LED{slash}_GPIO2-Pad22)") (class "Default")
      (node (ref "U20") (pin "22") (pinfunction "NSPD_LED/_GPIO2_22") (pintype "bidirectional"))
    )
    (net (code "465") (name "unconnected-(U20-PRTCTL2-Pad14)") (class "Default")
      (node (ref "U20") (pin "14") (pinfunction "PRTCTL2_14") (pintype "bidirectional"))
    )
    (net (code "466") (name "unconnected-(U20-PRTCTL3-Pad16)") (class "Default")
      (node (ref "U20") (pin "16") (pinfunction "PRTCTL3_16") (pintype "bidirectional"))
    )
    (net (code "467") (name "unconnected-(U20-PRTCTL4-Pad17)") (class "Default")
      (node (ref "U20") (pin "17") (pinfunction "PRTCTL4_17") (pintype "bidirectional"))
    )
    (net (code "468") (name "unconnected-(U20-PRTCTL5-Pad18)") (class "Default")
      (node (ref "U20") (pin "18") (pinfunction "PRTCTL5_18") (pintype "bidirectional"))
    )
    (net (code "469") (name "unconnected-(U20-RXN-Pad53)") (class "Default")
      (node (ref "U20") (pin "53") (pinfunction "RXN_53") (pintype "bidirectional"))
    )
    (net (code "470") (name "unconnected-(U20-RXP-Pad52)") (class "Default")
      (node (ref "U20") (pin "52") (pinfunction "RXP_52") (pintype "bidirectional"))
    )
    (net (code "471") (name "unconnected-(U20-TCK-Pad32)") (class "Default")
      (node (ref "U20") (pin "32") (pinfunction "TCK_32") (pintype "bidirectional"))
    )
    (net (code "472") (name "unconnected-(U20-TDI-Pad30)") (class "Default")
      (node (ref "U20") (pin "30") (pinfunction "TDI_30") (pintype "bidirectional"))
    )
    (net (code "473") (name "unconnected-(U20-TDO-Pad31)") (class "Default")
      (node (ref "U20") (pin "31") (pinfunction "TDO_31") (pintype "bidirectional"))
    )
    (net (code "474") (name "unconnected-(U20-TEST1-Pad13)") (class "Default")
      (node (ref "U20") (pin "13") (pinfunction "TEST1_13") (pintype "bidirectional"))
    )
    (net (code "475") (name "unconnected-(U20-TEST4-Pad47)") (class "Default")
      (node (ref "U20") (pin "47") (pinfunction "TEST4_47") (pintype "bidirectional"))
    )
    (net (code "476") (name "unconnected-(U20-TMS-Pad29)") (class "Default")
      (node (ref "U20") (pin "29") (pinfunction "TMS_29") (pintype "bidirectional"))
    )
    (net (code "477") (name "unconnected-(U20-TXN-Pad56)") (class "Default")
      (node (ref "U20") (pin "56") (pinfunction "TXN_56") (pintype "bidirectional"))
    )
    (net (code "478") (name "unconnected-(U20-TXP-Pad55)") (class "Default")
      (node (ref "U20") (pin "55") (pinfunction "TXP_55") (pintype "bidirectional"))
    )
    (net (code "479") (name "unconnected-(U29-Pad3V)") (class "Default")
      (node (ref "U29") (pin "3V") (pinfunction "3V_3V") (pintype "bidirectional"))
    )
    (net (code "480") (name "unconnected-(U29-Pad5V)") (class "Default")
      (node (ref "U29") (pin "5V") (pinfunction "5V_5V") (pintype "bidirectional"))
    )
    (net (code "481") (name "unconnected-(U29-PadAREF)") (class "Default")
      (node (ref "U29") (pin "AREF") (pinfunction "AREF_AREF") (pintype "bidirectional"))
    )
    (net (code "482") (name "unconnected-(U29-PadIOREF)") (class "Default")
      (node (ref "U29") (pin "IOREF") (pinfunction "IOREF_IOREF") (pintype "output"))
    )
    (net (code "483") (name "unconnected-(U29-PadRESERVED)") (class "Default")
      (node (ref "U29") (pin "RESERVED") (pinfunction "RESERVED_RESERVED") (pintype "no_connect"))
    )
    (net (code "484") (name "unconnected-(U29-PadVIN)") (class "Default")
      (node (ref "U29") (pin "VIN") (pinfunction "VIN_VIN") (pintype "bidirectional"))
    )
    (net (code "485") (name "unconnected-(U31-A7-PadP$8)") (class "Default")
      (node (ref "U31") (pin "P$8") (pinfunction "A7_P$8") (pintype "bidirectional"))
    )
    (net (code "486") (name "unconnected-(U31-B7-PadP$13)") (class "Default")
      (node (ref "U31") (pin "P$13") (pinfunction "B7_P$13") (pintype "bidirectional"))
    )
    (net (code "487") (name "unconnected-(U33-DRDY-PadP$7)") (class "Default")
      (node (ref "U33") (pin "P$7") (pinfunction "DRDY_P$7") (pintype "bidirectional"))
    )
    (net (code "488") (name "unconnected-(U34-DRDY-PadP$11)") (class "Default")
      (node (ref "U34") (pin "P$11") (pinfunction "DRDY_P$11") (pintype "bidirectional"))
    )
    (net (code "489") (name "unconnected-(U34-P0-PadP$2)") (class "Default")
      (node (ref "U34") (pin "P$2") (pinfunction "P0_P$2") (pintype "bidirectional"))
    )
    (net (code "490") (name "unconnected-(U34-P1-PadP$3)") (class "Default")
      (node (ref "U34") (pin "P$3") (pinfunction "P1_P$3") (pintype "bidirectional"))
    )
    (net (code "491") (name "unconnected-(U34-P3-PadP$5)") (class "Default")
      (node (ref "U34") (pin "P$5") (pinfunction "P3_P$5") (pintype "bidirectional"))
    )
    (net (code "492") (name "unconnected-(U34-P4-PadP$7)") (class "Default")
      (node (ref "U34") (pin "P$7") (pinfunction "P4_P$7") (pintype "bidirectional"))
    )
    (net (code "493") (name "unconnected-(U34-P5-PadP$8)") (class "Default")
      (node (ref "U34") (pin "P$8") (pinfunction "P5_P$8") (pintype "bidirectional"))
    )
    (net (code "494") (name "unconnected-(U34-P6-PadP$9)") (class "Default")
      (node (ref "U34") (pin "P$9") (pinfunction "P6_P$9") (pintype "bidirectional"))
    )
    (net (code "495") (name "unconnected-(U36-DRDY-PadP$1)") (class "Default")
      (node (ref "U36") (pin "P$1") (pinfunction "DRDY_P$1") (pintype "bidirectional"))
    )
    (net (code "496") (name "unconnected-(U37-AUX_CL-Pad7)") (class "Default")
      (node (ref "U37") (pin "7") (pinfunction "AUX_CL_7") (pintype "bidirectional"))
    )
    (net (code "497") (name "unconnected-(U37-AUX_DA-Pad21)") (class "Default")
      (node (ref "U37") (pin "21") (pinfunction "AUX_DA_21") (pintype "bidirectional"))
    )
    (net (code "498") (name "unconnected-(U39-DRDY-PadP$11)") (class "Default")
      (node (ref "U39") (pin "P$11") (pinfunction "DRDY_P$11") (pintype "bidirectional"))
    )
    (net (code "499") (name "unconnected-(U39-P0-PadP$2)") (class "Default")
      (node (ref "U39") (pin "P$2") (pinfunction "P0_P$2") (pintype "bidirectional"))
    )
    (net (code "500") (name "unconnected-(U39-P1-PadP$3)") (class "Default")
      (node (ref "U39") (pin "P$3") (pinfunction "P1_P$3") (pintype "bidirectional"))
    )
    (net (code "501") (name "unconnected-(U39-P3-PadP$5)") (class "Default")
      (node (ref "U39") (pin "P$5") (pinfunction "P3_P$5") (pintype "bidirectional"))
    )
    (net (code "502") (name "unconnected-(U39-P4-PadP$7)") (class "Default")
      (node (ref "U39") (pin "P$7") (pinfunction "P4_P$7") (pintype "bidirectional"))
    )
    (net (code "503") (name "unconnected-(U39-P5-PadP$8)") (class "Default")
      (node (ref "U39") (pin "P$8") (pinfunction "P5_P$8") (pintype "bidirectional"))
    )
    (net (code "504") (name "unconnected-(U39-P6-PadP$9)") (class "Default")
      (node (ref "U39") (pin "P$9") (pinfunction "P6_P$9") (pintype "bidirectional"))
    )
  )
)
